# v6.net
KiCad netlist of a schematic drawn in EAGLE
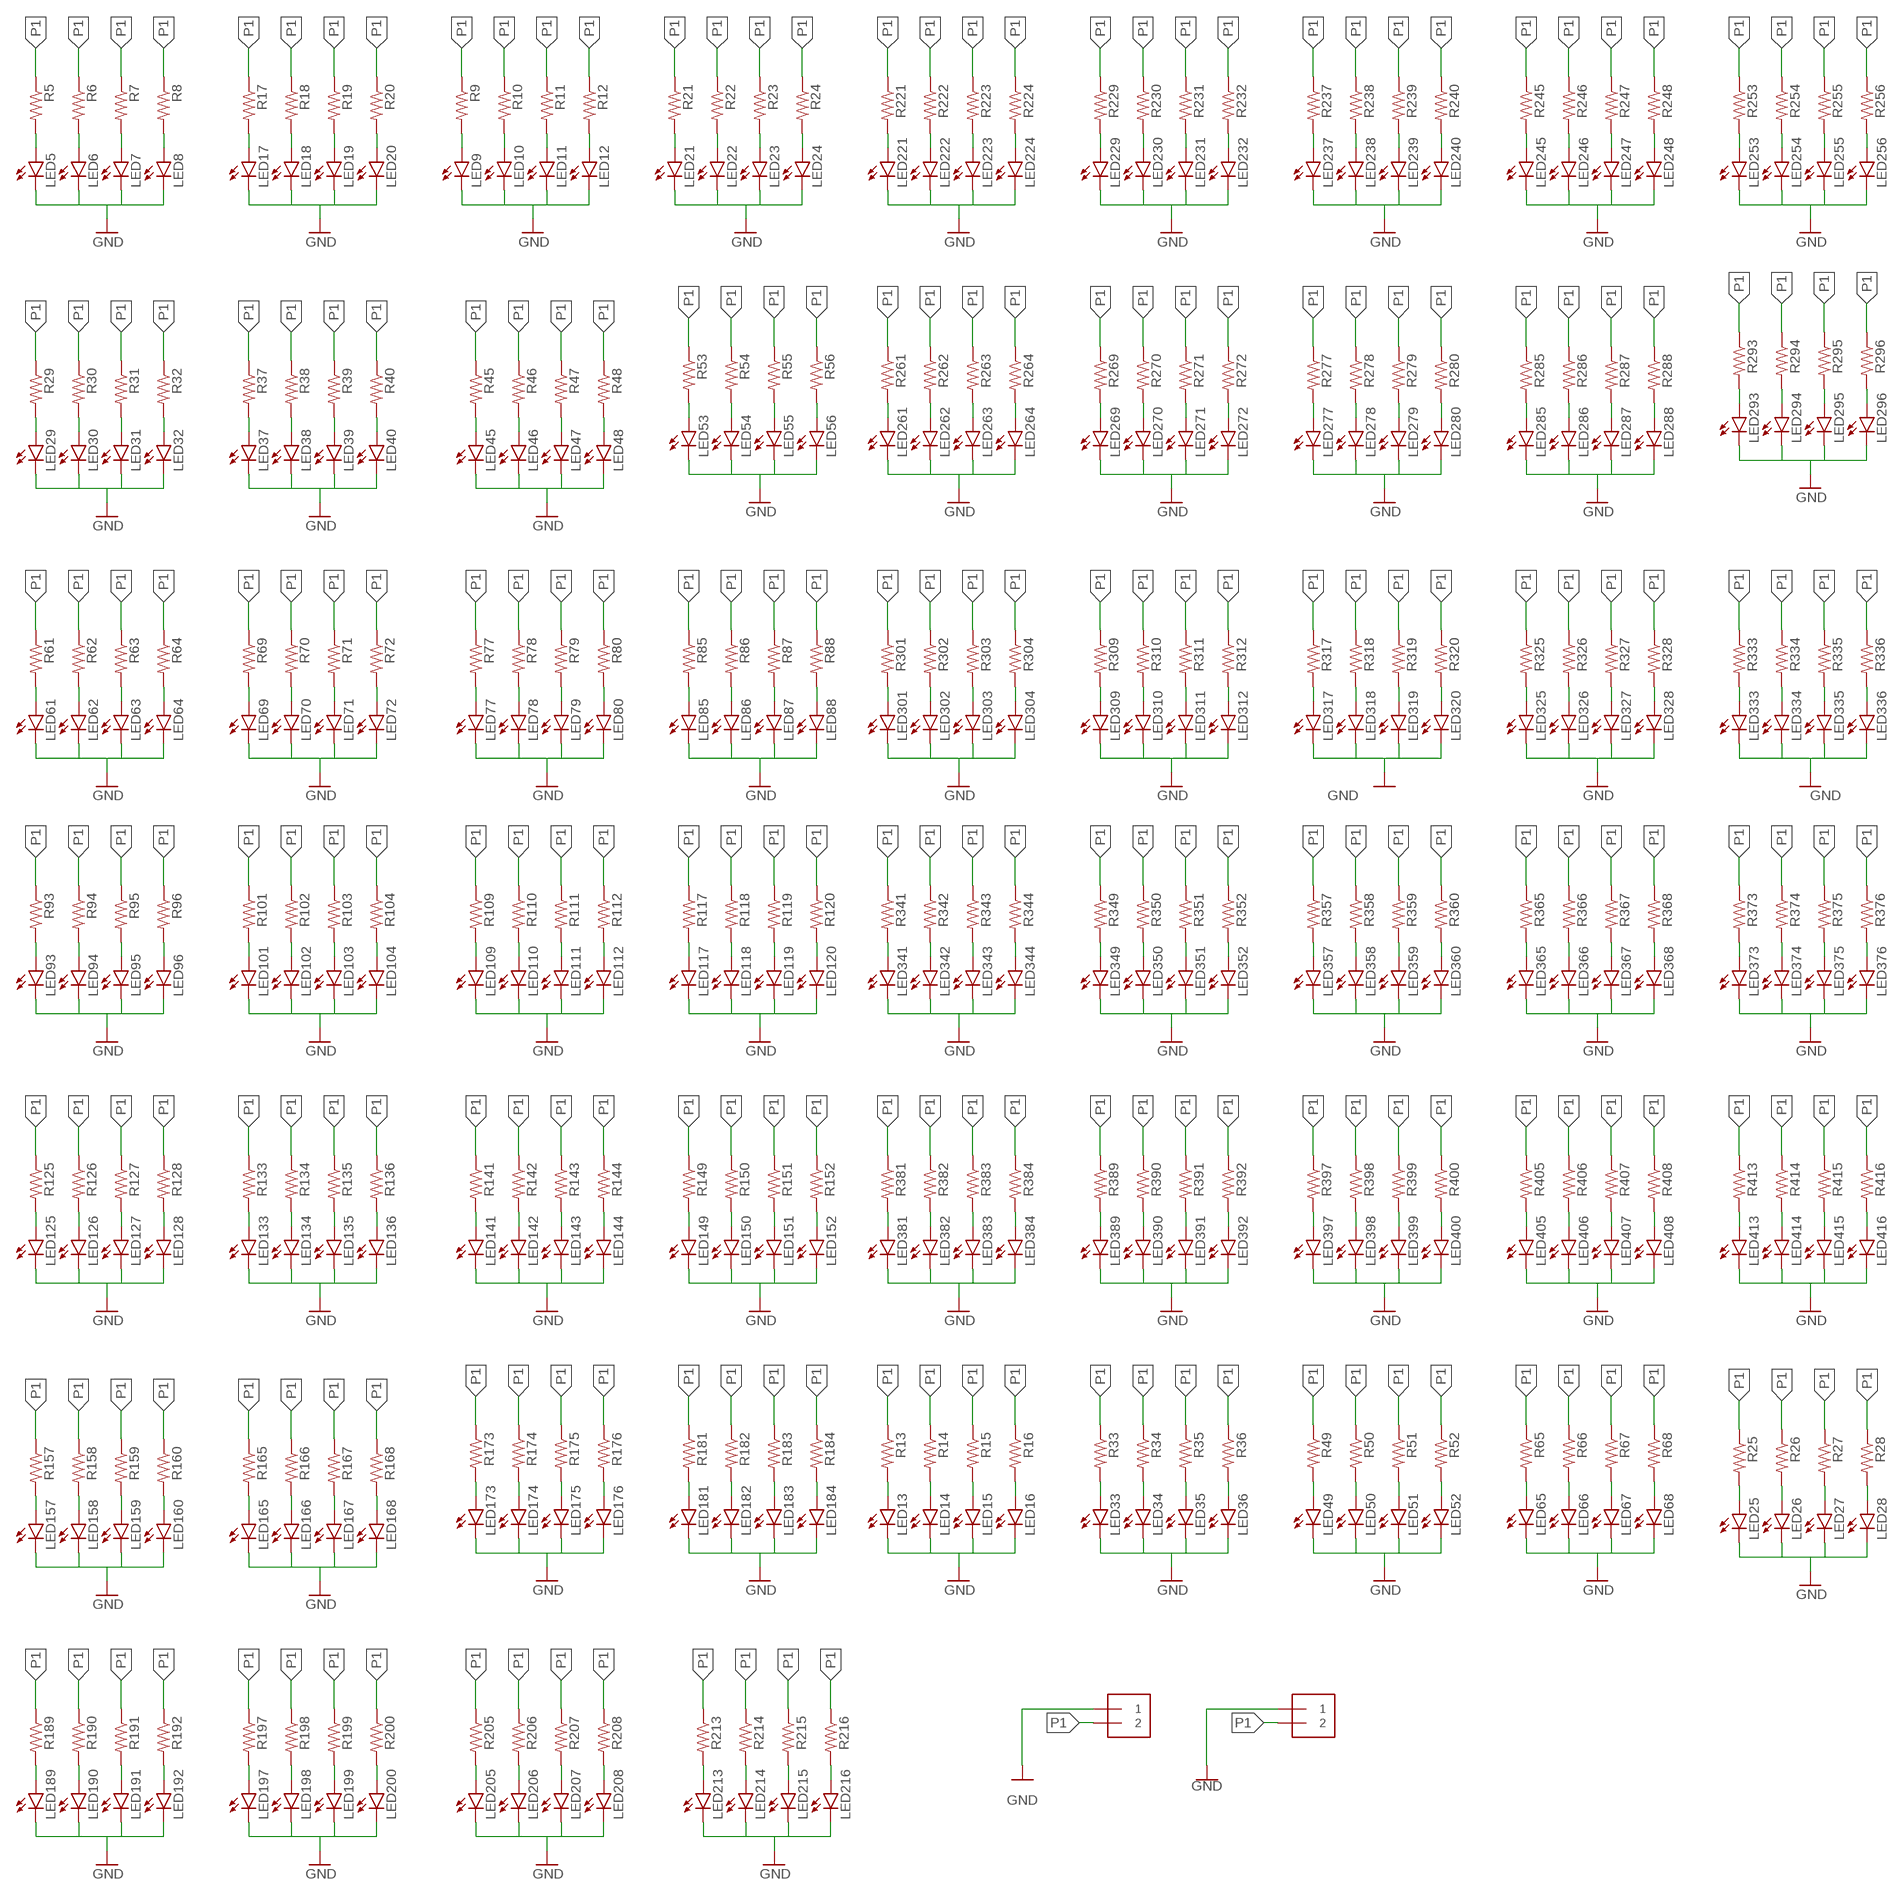
[diagram p0: schematic, sheet 1]

(export (version "E")
  (design (tool "Eeschema 10.0.6"))
  (components
    (comp (ref "LED5")
      (value "LEDCHIP-LED0603")
      (footprint "eagle-import:CHIP-LED0603")
      (libsource (lib "eagle-import") (part "LEDCHIP-LED0603"))
    )
    (comp (ref "LED6")
      (value "LEDCHIP-LED0603")
      (footprint "eagle-import:CHIP-LED0603")
      (libsource (lib "eagle-import") (part "LEDCHIP-LED0603"))
    )
    (comp (ref "LED7")
      (value "LEDCHIP-LED0603")
      (footprint "eagle-import:CHIP-LED0603")
      (libsource (lib "eagle-import") (part "LEDCHIP-LED0603"))
    )
    (comp (ref "LED8")
      (value "LEDCHIP-LED0603")
      (footprint "eagle-import:CHIP-LED0603")
      (libsource (lib "eagle-import") (part "LEDCHIP-LED0603"))
    )
    (comp (ref "LED9")
      (value "LEDCHIP-LED0603")
      (footprint "eagle-import:CHIP-LED0603")
      (libsource (lib "eagle-import") (part "LEDCHIP-LED0603"))
    )
    (comp (ref "LED10")
      (value "LEDCHIP-LED0603")
      (footprint "eagle-import:CHIP-LED0603")
      (libsource (lib "eagle-import") (part "LEDCHIP-LED0603"))
    )
    (comp (ref "LED11")
      (value "LEDCHIP-LED0603")
      (footprint "eagle-import:CHIP-LED0603")
      (libsource (lib "eagle-import") (part "LEDCHIP-LED0603"))
    )
    (comp (ref "LED12")
      (value "LEDCHIP-LED0603")
      (footprint "eagle-import:CHIP-LED0603")
      (libsource (lib "eagle-import") (part "LEDCHIP-LED0603"))
    )
    (comp (ref "LED13")
      (value "LEDCHIP-LED0603")
      (footprint "eagle-import:CHIP-LED0603")
      (libsource (lib "eagle-import") (part "LEDCHIP-LED0603"))
    )
    (comp (ref "LED14")
      (value "LEDCHIP-LED0603")
      (footprint "eagle-import:CHIP-LED0603")
      (libsource (lib "eagle-import") (part "LEDCHIP-LED0603"))
    )
    (comp (ref "LED15")
      (value "LEDCHIP-LED0603")
      (footprint "eagle-import:CHIP-LED0603")
      (libsource (lib "eagle-import") (part "LEDCHIP-LED0603"))
    )
    (comp (ref "LED16")
      (value "LEDCHIP-LED0603")
      (footprint "eagle-import:CHIP-LED0603")
      (libsource (lib "eagle-import") (part "LEDCHIP-LED0603"))
    )
    (comp (ref "LED17")
      (value "LEDCHIP-LED0603")
      (footprint "eagle-import:CHIP-LED0603")
      (libsource (lib "eagle-import") (part "LEDCHIP-LED0603"))
    )
    (comp (ref "LED18")
      (value "LEDCHIP-LED0603")
      (footprint "eagle-import:CHIP-LED0603")
      (libsource (lib "eagle-import") (part "LEDCHIP-LED0603"))
    )
    (comp (ref "LED19")
      (value "LEDCHIP-LED0603")
      (footprint "eagle-import:CHIP-LED0603")
      (libsource (lib "eagle-import") (part "LEDCHIP-LED0603"))
    )
    (comp (ref "LED20")
      (value "LEDCHIP-LED0603")
      (footprint "eagle-import:CHIP-LED0603")
      (libsource (lib "eagle-import") (part "LEDCHIP-LED0603"))
    )
    (comp (ref "LED21")
      (value "LEDCHIP-LED0603")
      (footprint "eagle-import:CHIP-LED0603")
      (libsource (lib "eagle-import") (part "LEDCHIP-LED0603"))
    )
    (comp (ref "LED22")
      (value "LEDCHIP-LED0603")
      (footprint "eagle-import:CHIP-LED0603")
      (libsource (lib "eagle-import") (part "LEDCHIP-LED0603"))
    )
    (comp (ref "LED23")
      (value "LEDCHIP-LED0603")
      (footprint "eagle-import:CHIP-LED0603")
      (libsource (lib "eagle-import") (part "LEDCHIP-LED0603"))
    )
    (comp (ref "LED24")
      (value "LEDCHIP-LED0603")
      (footprint "eagle-import:CHIP-LED0603")
      (libsource (lib "eagle-import") (part "LEDCHIP-LED0603"))
    )
    (comp (ref "LED25")
      (value "LEDCHIP-LED0603")
      (footprint "eagle-import:CHIP-LED0603")
      (libsource (lib "eagle-import") (part "LEDCHIP-LED0603"))
    )
    (comp (ref "LED26")
      (value "LEDCHIP-LED0603")
      (footprint "eagle-import:CHIP-LED0603")
      (libsource (lib "eagle-import") (part "LEDCHIP-LED0603"))
    )
    (comp (ref "LED27")
      (value "LEDCHIP-LED0603")
      (footprint "eagle-import:CHIP-LED0603")
      (libsource (lib "eagle-import") (part "LEDCHIP-LED0603"))
    )
    (comp (ref "LED28")
      (value "LEDCHIP-LED0603")
      (footprint "eagle-import:CHIP-LED0603")
      (libsource (lib "eagle-import") (part "LEDCHIP-LED0603"))
    )
    (comp (ref "LED29")
      (value "LEDCHIP-LED0603")
      (footprint "eagle-import:CHIP-LED0603")
      (libsource (lib "eagle-import") (part "LEDCHIP-LED0603"))
    )
    (comp (ref "LED30")
      (value "LEDCHIP-LED0603")
      (footprint "eagle-import:CHIP-LED0603")
      (libsource (lib "eagle-import") (part "LEDCHIP-LED0603"))
    )
    (comp (ref "LED31")
      (value "LEDCHIP-LED0603")
      (footprint "eagle-import:CHIP-LED0603")
      (libsource (lib "eagle-import") (part "LEDCHIP-LED0603"))
    )
    (comp (ref "LED32")
      (value "LEDCHIP-LED0603")
      (footprint "eagle-import:CHIP-LED0603")
      (libsource (lib "eagle-import") (part "LEDCHIP-LED0603"))
    )
    (comp (ref "LED33")
      (value "LEDCHIP-LED0603")
      (footprint "eagle-import:CHIP-LED0603")
      (libsource (lib "eagle-import") (part "LEDCHIP-LED0603"))
    )
    (comp (ref "LED34")
      (value "LEDCHIP-LED0603")
      (footprint "eagle-import:CHIP-LED0603")
      (libsource (lib "eagle-import") (part "LEDCHIP-LED0603"))
    )
    (comp (ref "LED35")
      (value "LEDCHIP-LED0603")
      (footprint "eagle-import:CHIP-LED0603")
      (libsource (lib "eagle-import") (part "LEDCHIP-LED0603"))
    )
    (comp (ref "LED36")
      (value "LEDCHIP-LED0603")
      (footprint "eagle-import:CHIP-LED0603")
      (libsource (lib "eagle-import") (part "LEDCHIP-LED0603"))
    )
    (comp (ref "LED37")
      (value "LEDCHIP-LED0603")
      (footprint "eagle-import:CHIP-LED0603")
      (libsource (lib "eagle-import") (part "LEDCHIP-LED0603"))
    )
    (comp (ref "LED38")
      (value "LEDCHIP-LED0603")
      (footprint "eagle-import:CHIP-LED0603")
      (libsource (lib "eagle-import") (part "LEDCHIP-LED0603"))
    )
    (comp (ref "LED39")
      (value "LEDCHIP-LED0603")
      (footprint "eagle-import:CHIP-LED0603")
      (libsource (lib "eagle-import") (part "LEDCHIP-LED0603"))
    )
    (comp (ref "LED40")
      (value "LEDCHIP-LED0603")
      (footprint "eagle-import:CHIP-LED0603")
      (libsource (lib "eagle-import") (part "LEDCHIP-LED0603"))
    )
    (comp (ref "LED45")
      (value "LEDCHIP-LED0603")
      (footprint "eagle-import:CHIP-LED0603")
      (libsource (lib "eagle-import") (part "LEDCHIP-LED0603"))
    )
    (comp (ref "LED46")
      (value "LEDCHIP-LED0603")
      (footprint "eagle-import:CHIP-LED0603")
      (libsource (lib "eagle-import") (part "LEDCHIP-LED0603"))
    )
    (comp (ref "LED47")
      (value "LEDCHIP-LED0603")
      (footprint "eagle-import:CHIP-LED0603")
      (libsource (lib "eagle-import") (part "LEDCHIP-LED0603"))
    )
    (comp (ref "LED48")
      (value "LEDCHIP-LED0603")
      (footprint "eagle-import:CHIP-LED0603")
      (libsource (lib "eagle-import") (part "LEDCHIP-LED0603"))
    )
    (comp (ref "LED49")
      (value "LEDCHIP-LED0603")
      (footprint "eagle-import:CHIP-LED0603")
      (libsource (lib "eagle-import") (part "LEDCHIP-LED0603"))
    )
    (comp (ref "LED50")
      (value "LEDCHIP-LED0603")
      (footprint "eagle-import:CHIP-LED0603")
      (libsource (lib "eagle-import") (part "LEDCHIP-LED0603"))
    )
    (comp (ref "LED51")
      (value "LEDCHIP-LED0603")
      (footprint "eagle-import:CHIP-LED0603")
      (libsource (lib "eagle-import") (part "LEDCHIP-LED0603"))
    )
    (comp (ref "LED52")
      (value "LEDCHIP-LED0603")
      (footprint "eagle-import:CHIP-LED0603")
      (libsource (lib "eagle-import") (part "LEDCHIP-LED0603"))
    )
    (comp (ref "LED53")
      (value "LEDCHIP-LED0603")
      (footprint "eagle-import:CHIP-LED0603")
      (libsource (lib "eagle-import") (part "LEDCHIP-LED0603"))
    )
    (comp (ref "LED54")
      (value "LEDCHIP-LED0603")
      (footprint "eagle-import:CHIP-LED0603")
      (libsource (lib "eagle-import") (part "LEDCHIP-LED0603"))
    )
    (comp (ref "LED55")
      (value "LEDCHIP-LED0603")
      (footprint "eagle-import:CHIP-LED0603")
      (libsource (lib "eagle-import") (part "LEDCHIP-LED0603"))
    )
    (comp (ref "LED56")
      (value "LEDCHIP-LED0603")
      (footprint "eagle-import:CHIP-LED0603")
      (libsource (lib "eagle-import") (part "LEDCHIP-LED0603"))
    )
    (comp (ref "LED61")
      (value "LEDCHIP-LED0603")
      (footprint "eagle-import:CHIP-LED0603")
      (libsource (lib "eagle-import") (part "LEDCHIP-LED0603"))
    )
    (comp (ref "LED62")
      (value "LEDCHIP-LED0603")
      (footprint "eagle-import:CHIP-LED0603")
      (libsource (lib "eagle-import") (part "LEDCHIP-LED0603"))
    )
    (comp (ref "LED63")
      (value "LEDCHIP-LED0603")
      (footprint "eagle-import:CHIP-LED0603")
      (libsource (lib "eagle-import") (part "LEDCHIP-LED0603"))
    )
    (comp (ref "LED64")
      (value "LEDCHIP-LED0603")
      (footprint "eagle-import:CHIP-LED0603")
      (libsource (lib "eagle-import") (part "LEDCHIP-LED0603"))
    )
    (comp (ref "LED65")
      (value "LEDCHIP-LED0603")
      (footprint "eagle-import:CHIP-LED0603")
      (libsource (lib "eagle-import") (part "LEDCHIP-LED0603"))
    )
    (comp (ref "LED66")
      (value "LEDCHIP-LED0603")
      (footprint "eagle-import:CHIP-LED0603")
      (libsource (lib "eagle-import") (part "LEDCHIP-LED0603"))
    )
    (comp (ref "LED67")
      (value "LEDCHIP-LED0603")
      (footprint "eagle-import:CHIP-LED0603")
      (libsource (lib "eagle-import") (part "LEDCHIP-LED0603"))
    )
    (comp (ref "LED68")
      (value "LEDCHIP-LED0603")
      (footprint "eagle-import:CHIP-LED0603")
      (libsource (lib "eagle-import") (part "LEDCHIP-LED0603"))
    )
    (comp (ref "LED69")
      (value "LEDCHIP-LED0603")
      (footprint "eagle-import:CHIP-LED0603")
      (libsource (lib "eagle-import") (part "LEDCHIP-LED0603"))
    )
    (comp (ref "LED70")
      (value "LEDCHIP-LED0603")
      (footprint "eagle-import:CHIP-LED0603")
      (libsource (lib "eagle-import") (part "LEDCHIP-LED0603"))
    )
    (comp (ref "LED71")
      (value "LEDCHIP-LED0603")
      (footprint "eagle-import:CHIP-LED0603")
      (libsource (lib "eagle-import") (part "LEDCHIP-LED0603"))
    )
    (comp (ref "LED72")
      (value "LEDCHIP-LED0603")
      (footprint "eagle-import:CHIP-LED0603")
      (libsource (lib "eagle-import") (part "LEDCHIP-LED0603"))
    )
    (comp (ref "LED77")
      (value "LEDCHIP-LED0603")
      (footprint "eagle-import:CHIP-LED0603")
      (libsource (lib "eagle-import") (part "LEDCHIP-LED0603"))
    )
    (comp (ref "LED78")
      (value "LEDCHIP-LED0603")
      (footprint "eagle-import:CHIP-LED0603")
      (libsource (lib "eagle-import") (part "LEDCHIP-LED0603"))
    )
    (comp (ref "LED79")
      (value "LEDCHIP-LED0603")
      (footprint "eagle-import:CHIP-LED0603")
      (libsource (lib "eagle-import") (part "LEDCHIP-LED0603"))
    )
    (comp (ref "LED80")
      (value "LEDCHIP-LED0603")
      (footprint "eagle-import:CHIP-LED0603")
      (libsource (lib "eagle-import") (part "LEDCHIP-LED0603"))
    )
    (comp (ref "LED85")
      (value "LEDCHIP-LED0603")
      (footprint "eagle-import:CHIP-LED0603")
      (libsource (lib "eagle-import") (part "LEDCHIP-LED0603"))
    )
    (comp (ref "LED86")
      (value "LEDCHIP-LED0603")
      (footprint "eagle-import:CHIP-LED0603")
      (libsource (lib "eagle-import") (part "LEDCHIP-LED0603"))
    )
    (comp (ref "LED87")
      (value "LEDCHIP-LED0603")
      (footprint "eagle-import:CHIP-LED0603")
      (libsource (lib "eagle-import") (part "LEDCHIP-LED0603"))
    )
    (comp (ref "LED88")
      (value "LEDCHIP-LED0603")
      (footprint "eagle-import:CHIP-LED0603")
      (libsource (lib "eagle-import") (part "LEDCHIP-LED0603"))
    )
    (comp (ref "LED93")
      (value "LEDCHIP-LED0603")
      (footprint "eagle-import:CHIP-LED0603")
      (libsource (lib "eagle-import") (part "LEDCHIP-LED0603"))
    )
    (comp (ref "LED94")
      (value "LEDCHIP-LED0603")
      (footprint "eagle-import:CHIP-LED0603")
      (libsource (lib "eagle-import") (part "LEDCHIP-LED0603"))
    )
    (comp (ref "LED95")
      (value "LEDCHIP-LED0603")
      (footprint "eagle-import:CHIP-LED0603")
      (libsource (lib "eagle-import") (part "LEDCHIP-LED0603"))
    )
    (comp (ref "LED96")
      (value "LEDCHIP-LED0603")
      (footprint "eagle-import:CHIP-LED0603")
      (libsource (lib "eagle-import") (part "LEDCHIP-LED0603"))
    )
    (comp (ref "LED101")
      (value "LEDCHIP-LED0603")
      (footprint "eagle-import:CHIP-LED0603")
      (libsource (lib "eagle-import") (part "LEDCHIP-LED0603"))
    )
    (comp (ref "LED102")
      (value "LEDCHIP-LED0603")
      (footprint "eagle-import:CHIP-LED0603")
      (libsource (lib "eagle-import") (part "LEDCHIP-LED0603"))
    )
    (comp (ref "LED103")
      (value "LEDCHIP-LED0603")
      (footprint "eagle-import:CHIP-LED0603")
      (libsource (lib "eagle-import") (part "LEDCHIP-LED0603"))
    )
    (comp (ref "LED104")
      (value "LEDCHIP-LED0603")
      (footprint "eagle-import:CHIP-LED0603")
      (libsource (lib "eagle-import") (part "LEDCHIP-LED0603"))
    )
    (comp (ref "LED109")
      (value "LEDCHIP-LED0603")
      (footprint "eagle-import:CHIP-LED0603")
      (libsource (lib "eagle-import") (part "LEDCHIP-LED0603"))
    )
    (comp (ref "LED110")
      (value "LEDCHIP-LED0603")
      (footprint "eagle-import:CHIP-LED0603")
      (libsource (lib "eagle-import") (part "LEDCHIP-LED0603"))
    )
    (comp (ref "LED111")
      (value "LEDCHIP-LED0603")
      (footprint "eagle-import:CHIP-LED0603")
      (libsource (lib "eagle-import") (part "LEDCHIP-LED0603"))
    )
    (comp (ref "LED112")
      (value "LEDCHIP-LED0603")
      (footprint "eagle-import:CHIP-LED0603")
      (libsource (lib "eagle-import") (part "LEDCHIP-LED0603"))
    )
    (comp (ref "LED117")
      (value "LEDCHIP-LED0603")
      (footprint "eagle-import:CHIP-LED0603")
      (libsource (lib "eagle-import") (part "LEDCHIP-LED0603"))
    )
    (comp (ref "LED118")
      (value "LEDCHIP-LED0603")
      (footprint "eagle-import:CHIP-LED0603")
      (libsource (lib "eagle-import") (part "LEDCHIP-LED0603"))
    )
    (comp (ref "LED119")
      (value "LEDCHIP-LED0603")
      (footprint "eagle-import:CHIP-LED0603")
      (libsource (lib "eagle-import") (part "LEDCHIP-LED0603"))
    )
    (comp (ref "LED120")
      (value "LEDCHIP-LED0603")
      (footprint "eagle-import:CHIP-LED0603")
      (libsource (lib "eagle-import") (part "LEDCHIP-LED0603"))
    )
    (comp (ref "LED125")
      (value "LEDCHIP-LED0603")
      (footprint "eagle-import:CHIP-LED0603")
      (libsource (lib "eagle-import") (part "LEDCHIP-LED0603"))
    )
    (comp (ref "LED126")
      (value "LEDCHIP-LED0603")
      (footprint "eagle-import:CHIP-LED0603")
      (libsource (lib "eagle-import") (part "LEDCHIP-LED0603"))
    )
    (comp (ref "LED127")
      (value "LEDCHIP-LED0603")
      (footprint "eagle-import:CHIP-LED0603")
      (libsource (lib "eagle-import") (part "LEDCHIP-LED0603"))
    )
    (comp (ref "LED128")
      (value "LEDCHIP-LED0603")
      (footprint "eagle-import:CHIP-LED0603")
      (libsource (lib "eagle-import") (part "LEDCHIP-LED0603"))
    )
    (comp (ref "LED133")
      (value "LEDCHIP-LED0603")
      (footprint "eagle-import:CHIP-LED0603")
      (libsource (lib "eagle-import") (part "LEDCHIP-LED0603"))
    )
    (comp (ref "LED134")
      (value "LEDCHIP-LED0603")
      (footprint "eagle-import:CHIP-LED0603")
      (libsource (lib "eagle-import") (part "LEDCHIP-LED0603"))
    )
    (comp (ref "LED135")
      (value "LEDCHIP-LED0603")
      (footprint "eagle-import:CHIP-LED0603")
      (libsource (lib "eagle-import") (part "LEDCHIP-LED0603"))
    )
    (comp (ref "LED136")
      (value "LEDCHIP-LED0603")
      (footprint "eagle-import:CHIP-LED0603")
      (libsource (lib "eagle-import") (part "LEDCHIP-LED0603"))
    )
    (comp (ref "LED141")
      (value "LEDCHIP-LED0603")
      (footprint "eagle-import:CHIP-LED0603")
      (libsource (lib "eagle-import") (part "LEDCHIP-LED0603"))
    )
    (comp (ref "LED142")
      (value "LEDCHIP-LED0603")
      (footprint "eagle-import:CHIP-LED0603")
      (libsource (lib "eagle-import") (part "LEDCHIP-LED0603"))
    )
    (comp (ref "LED143")
      (value "LEDCHIP-LED0603")
      (footprint "eagle-import:CHIP-LED0603")
      (libsource (lib "eagle-import") (part "LEDCHIP-LED0603"))
    )
    (comp (ref "LED144")
      (value "LEDCHIP-LED0603")
      (footprint "eagle-import:CHIP-LED0603")
      (libsource (lib "eagle-import") (part "LEDCHIP-LED0603"))
    )
    (comp (ref "LED149")
      (value "LEDCHIP-LED0603")
      (footprint "eagle-import:CHIP-LED0603")
      (libsource (lib "eagle-import") (part "LEDCHIP-LED0603"))
    )
    (comp (ref "LED150")
      (value "LEDCHIP-LED0603")
      (footprint "eagle-import:CHIP-LED0603")
      (libsource (lib "eagle-import") (part "LEDCHIP-LED0603"))
    )
    (comp (ref "LED151")
      (value "LEDCHIP-LED0603")
      (footprint "eagle-import:CHIP-LED0603")
      (libsource (lib "eagle-import") (part "LEDCHIP-LED0603"))
    )
    (comp (ref "LED152")
      (value "LEDCHIP-LED0603")
      (footprint "eagle-import:CHIP-LED0603")
      (libsource (lib "eagle-import") (part "LEDCHIP-LED0603"))
    )
    (comp (ref "LED157")
      (value "LEDCHIP-LED0603")
      (footprint "eagle-import:CHIP-LED0603")
      (libsource (lib "eagle-import") (part "LEDCHIP-LED0603"))
    )
    (comp (ref "LED158")
      (value "LEDCHIP-LED0603")
      (footprint "eagle-import:CHIP-LED0603")
      (libsource (lib "eagle-import") (part "LEDCHIP-LED0603"))
    )
    (comp (ref "LED159")
      (value "LEDCHIP-LED0603")
      (footprint "eagle-import:CHIP-LED0603")
      (libsource (lib "eagle-import") (part "LEDCHIP-LED0603"))
    )
    (comp (ref "LED160")
      (value "LEDCHIP-LED0603")
      (footprint "eagle-import:CHIP-LED0603")
      (libsource (lib "eagle-import") (part "LEDCHIP-LED0603"))
    )
    (comp (ref "LED165")
      (value "LEDCHIP-LED0603")
      (footprint "eagle-import:CHIP-LED0603")
      (libsource (lib "eagle-import") (part "LEDCHIP-LED0603"))
    )
    (comp (ref "LED166")
      (value "LEDCHIP-LED0603")
      (footprint "eagle-import:CHIP-LED0603")
      (libsource (lib "eagle-import") (part "LEDCHIP-LED0603"))
    )
    (comp (ref "LED167")
      (value "LEDCHIP-LED0603")
      (footprint "eagle-import:CHIP-LED0603")
      (libsource (lib "eagle-import") (part "LEDCHIP-LED0603"))
    )
    (comp (ref "LED168")
      (value "LEDCHIP-LED0603")
      (footprint "eagle-import:CHIP-LED0603")
      (libsource (lib "eagle-import") (part "LEDCHIP-LED0603"))
    )
    (comp (ref "LED173")
      (value "LEDCHIP-LED0603")
      (footprint "eagle-import:CHIP-LED0603")
      (libsource (lib "eagle-import") (part "LEDCHIP-LED0603"))
    )
    (comp (ref "LED174")
      (value "LEDCHIP-LED0603")
      (footprint "eagle-import:CHIP-LED0603")
      (libsource (lib "eagle-import") (part "LEDCHIP-LED0603"))
    )
    (comp (ref "LED175")
      (value "LEDCHIP-LED0603")
      (footprint "eagle-import:CHIP-LED0603")
      (libsource (lib "eagle-import") (part "LEDCHIP-LED0603"))
    )
    (comp (ref "LED176")
      (value "LEDCHIP-LED0603")
      (footprint "eagle-import:CHIP-LED0603")
      (libsource (lib "eagle-import") (part "LEDCHIP-LED0603"))
    )
    (comp (ref "LED181")
      (value "LEDCHIP-LED0603")
      (footprint "eagle-import:CHIP-LED0603")
      (libsource (lib "eagle-import") (part "LEDCHIP-LED0603"))
    )
    (comp (ref "LED182")
      (value "LEDCHIP-LED0603")
      (footprint "eagle-import:CHIP-LED0603")
      (libsource (lib "eagle-import") (part "LEDCHIP-LED0603"))
    )
    (comp (ref "LED183")
      (value "LEDCHIP-LED0603")
      (footprint "eagle-import:CHIP-LED0603")
      (libsource (lib "eagle-import") (part "LEDCHIP-LED0603"))
    )
    (comp (ref "LED184")
      (value "LEDCHIP-LED0603")
      (footprint "eagle-import:CHIP-LED0603")
      (libsource (lib "eagle-import") (part "LEDCHIP-LED0603"))
    )
    (comp (ref "LED189")
      (value "LEDCHIP-LED0603")
      (footprint "eagle-import:CHIP-LED0603")
      (libsource (lib "eagle-import") (part "LEDCHIP-LED0603"))
    )
    (comp (ref "LED190")
      (value "LEDCHIP-LED0603")
      (footprint "eagle-import:CHIP-LED0603")
      (libsource (lib "eagle-import") (part "LEDCHIP-LED0603"))
    )
    (comp (ref "LED191")
      (value "LEDCHIP-LED0603")
      (footprint "eagle-import:CHIP-LED0603")
      (libsource (lib "eagle-import") (part "LEDCHIP-LED0603"))
    )
    (comp (ref "LED192")
      (value "LEDCHIP-LED0603")
      (footprint "eagle-import:CHIP-LED0603")
      (libsource (lib "eagle-import") (part "LEDCHIP-LED0603"))
    )
    (comp (ref "LED197")
      (value "LEDCHIP-LED0603")
      (footprint "eagle-import:CHIP-LED0603")
      (libsource (lib "eagle-import") (part "LEDCHIP-LED0603"))
    )
    (comp (ref "LED198")
      (value "LEDCHIP-LED0603")
      (footprint "eagle-import:CHIP-LED0603")
      (libsource (lib "eagle-import") (part "LEDCHIP-LED0603"))
    )
    (comp (ref "LED199")
      (value "LEDCHIP-LED0603")
      (footprint "eagle-import:CHIP-LED0603")
      (libsource (lib "eagle-import") (part "LEDCHIP-LED0603"))
    )
    (comp (ref "LED200")
      (value "LEDCHIP-LED0603")
      (footprint "eagle-import:CHIP-LED0603")
      (libsource (lib "eagle-import") (part "LEDCHIP-LED0603"))
    )
    (comp (ref "LED205")
      (value "LEDCHIP-LED0603")
      (footprint "eagle-import:CHIP-LED0603")
      (libsource (lib "eagle-import") (part "LEDCHIP-LED0603"))
    )
    (comp (ref "LED206")
      (value "LEDCHIP-LED0603")
      (footprint "eagle-import:CHIP-LED0603")
      (libsource (lib "eagle-import") (part "LEDCHIP-LED0603"))
    )
    (comp (ref "LED207")
      (value "LEDCHIP-LED0603")
      (footprint "eagle-import:CHIP-LED0603")
      (libsource (lib "eagle-import") (part "LEDCHIP-LED0603"))
    )
    (comp (ref "LED208")
      (value "LEDCHIP-LED0603")
      (footprint "eagle-import:CHIP-LED0603")
      (libsource (lib "eagle-import") (part "LEDCHIP-LED0603"))
    )
    (comp (ref "LED213")
      (value "LEDCHIP-LED0603")
      (footprint "eagle-import:CHIP-LED0603")
      (libsource (lib "eagle-import") (part "LEDCHIP-LED0603"))
    )
    (comp (ref "LED214")
      (value "LEDCHIP-LED0603")
      (footprint "eagle-import:CHIP-LED0603")
      (libsource (lib "eagle-import") (part "LEDCHIP-LED0603"))
    )
    (comp (ref "LED215")
      (value "LEDCHIP-LED0603")
      (footprint "eagle-import:CHIP-LED0603")
      (libsource (lib "eagle-import") (part "LEDCHIP-LED0603"))
    )
    (comp (ref "LED216")
      (value "LEDCHIP-LED0603")
      (footprint "eagle-import:CHIP-LED0603")
      (libsource (lib "eagle-import") (part "LEDCHIP-LED0603"))
    )
    (comp (ref "LED221")
      (value "LEDCHIP-LED0603")
      (footprint "eagle-import:CHIP-LED0603")
      (libsource (lib "eagle-import") (part "LEDCHIP-LED0603"))
    )
    (comp (ref "LED222")
      (value "LEDCHIP-LED0603")
      (footprint "eagle-import:CHIP-LED0603")
      (libsource (lib "eagle-import") (part "LEDCHIP-LED0603"))
    )
    (comp (ref "LED223")
      (value "LEDCHIP-LED0603")
      (footprint "eagle-import:CHIP-LED0603")
      (libsource (lib "eagle-import") (part "LEDCHIP-LED0603"))
    )
    (comp (ref "LED224")
      (value "LEDCHIP-LED0603")
      (footprint "eagle-import:CHIP-LED0603")
      (libsource (lib "eagle-import") (part "LEDCHIP-LED0603"))
    )
    (comp (ref "LED229")
      (value "LEDCHIP-LED0603")
      (footprint "eagle-import:CHIP-LED0603")
      (libsource (lib "eagle-import") (part "LEDCHIP-LED0603"))
    )
    (comp (ref "LED230")
      (value "LEDCHIP-LED0603")
      (footprint "eagle-import:CHIP-LED0603")
      (libsource (lib "eagle-import") (part "LEDCHIP-LED0603"))
    )
    (comp (ref "LED231")
      (value "LEDCHIP-LED0603")
      (footprint "eagle-import:CHIP-LED0603")
      (libsource (lib "eagle-import") (part "LEDCHIP-LED0603"))
    )
    (comp (ref "LED232")
      (value "LEDCHIP-LED0603")
      (footprint "eagle-import:CHIP-LED0603")
      (libsource (lib "eagle-import") (part "LEDCHIP-LED0603"))
    )
    (comp (ref "LED237")
      (value "LEDCHIP-LED0603")
      (footprint "eagle-import:CHIP-LED0603")
      (libsource (lib "eagle-import") (part "LEDCHIP-LED0603"))
    )
    (comp (ref "LED238")
      (value "LEDCHIP-LED0603")
      (footprint "eagle-import:CHIP-LED0603")
      (libsource (lib "eagle-import") (part "LEDCHIP-LED0603"))
    )
    (comp (ref "LED239")
      (value "LEDCHIP-LED0603")
      (footprint "eagle-import:CHIP-LED0603")
      (libsource (lib "eagle-import") (part "LEDCHIP-LED0603"))
    )
    (comp (ref "LED240")
      (value "LEDCHIP-LED0603")
      (footprint "eagle-import:CHIP-LED0603")
      (libsource (lib "eagle-import") (part "LEDCHIP-LED0603"))
    )
    (comp (ref "LED245")
      (value "LEDCHIP-LED0603")
      (footprint "eagle-import:CHIP-LED0603")
      (libsource (lib "eagle-import") (part "LEDCHIP-LED0603"))
    )
    (comp (ref "LED246")
      (value "LEDCHIP-LED0603")
      (footprint "eagle-import:CHIP-LED0603")
      (libsource (lib "eagle-import") (part "LEDCHIP-LED0603"))
    )
    (comp (ref "LED247")
      (value "LEDCHIP-LED0603")
      (footprint "eagle-import:CHIP-LED0603")
      (libsource (lib "eagle-import") (part "LEDCHIP-LED0603"))
    )
    (comp (ref "LED248")
      (value "LEDCHIP-LED0603")
      (footprint "eagle-import:CHIP-LED0603")
      (libsource (lib "eagle-import") (part "LEDCHIP-LED0603"))
    )
    (comp (ref "LED253")
      (value "LEDCHIP-LED0603")
      (footprint "eagle-import:CHIP-LED0603")
      (libsource (lib "eagle-import") (part "LEDCHIP-LED0603"))
    )
    (comp (ref "LED254")
      (value "LEDCHIP-LED0603")
      (footprint "eagle-import:CHIP-LED0603")
      (libsource (lib "eagle-import") (part "LEDCHIP-LED0603"))
    )
    (comp (ref "LED255")
      (value "LEDCHIP-LED0603")
      (footprint "eagle-import:CHIP-LED0603")
      (libsource (lib "eagle-import") (part "LEDCHIP-LED0603"))
    )
    (comp (ref "LED256")
      (value "LEDCHIP-LED0603")
      (footprint "eagle-import:CHIP-LED0603")
      (libsource (lib "eagle-import") (part "LEDCHIP-LED0603"))
    )
    (comp (ref "LED261")
      (value "LEDCHIP-LED0603")
      (footprint "eagle-import:CHIP-LED0603")
      (libsource (lib "eagle-import") (part "LEDCHIP-LED0603"))
    )
    (comp (ref "LED262")
      (value "LEDCHIP-LED0603")
      (footprint "eagle-import:CHIP-LED0603")
      (libsource (lib "eagle-import") (part "LEDCHIP-LED0603"))
    )
    (comp (ref "LED263")
      (value "LEDCHIP-LED0603")
      (footprint "eagle-import:CHIP-LED0603")
      (libsource (lib "eagle-import") (part "LEDCHIP-LED0603"))
    )
    (comp (ref "LED264")
      (value "LEDCHIP-LED0603")
      (footprint "eagle-import:CHIP-LED0603")
      (libsource (lib "eagle-import") (part "LEDCHIP-LED0603"))
    )
    (comp (ref "LED269")
      (value "LEDCHIP-LED0603")
      (footprint "eagle-import:CHIP-LED0603")
      (libsource (lib "eagle-import") (part "LEDCHIP-LED0603"))
    )
    (comp (ref "LED270")
      (value "LEDCHIP-LED0603")
      (footprint "eagle-import:CHIP-LED0603")
      (libsource (lib "eagle-import") (part "LEDCHIP-LED0603"))
    )
    (comp (ref "LED271")
      (value "LEDCHIP-LED0603")
      (footprint "eagle-import:CHIP-LED0603")
      (libsource (lib "eagle-import") (part "LEDCHIP-LED0603"))
    )
    (comp (ref "LED272")
      (value "LEDCHIP-LED0603")
      (footprint "eagle-import:CHIP-LED0603")
      (libsource (lib "eagle-import") (part "LEDCHIP-LED0603"))
    )
    (comp (ref "LED277")
      (value "LEDCHIP-LED0603")
      (footprint "eagle-import:CHIP-LED0603")
      (libsource (lib "eagle-import") (part "LEDCHIP-LED0603"))
    )
    (comp (ref "LED278")
      (value "LEDCHIP-LED0603")
      (footprint "eagle-import:CHIP-LED0603")
      (libsource (lib "eagle-import") (part "LEDCHIP-LED0603"))
    )
    (comp (ref "LED279")
      (value "LEDCHIP-LED0603")
      (footprint "eagle-import:CHIP-LED0603")
      (libsource (lib "eagle-import") (part "LEDCHIP-LED0603"))
    )
    (comp (ref "LED280")
      (value "LEDCHIP-LED0603")
      (footprint "eagle-import:CHIP-LED0603")
      (libsource (lib "eagle-import") (part "LEDCHIP-LED0603"))
    )
    (comp (ref "LED285")
      (value "LEDCHIP-LED0603")
      (footprint "eagle-import:CHIP-LED0603")
      (libsource (lib "eagle-import") (part "LEDCHIP-LED0603"))
    )
    (comp (ref "LED286")
      (value "LEDCHIP-LED0603")
      (footprint "eagle-import:CHIP-LED0603")
      (libsource (lib "eagle-import") (part "LEDCHIP-LED0603"))
    )
    (comp (ref "LED287")
      (value "LEDCHIP-LED0603")
      (footprint "eagle-import:CHIP-LED0603")
      (libsource (lib "eagle-import") (part "LEDCHIP-LED0603"))
    )
    (comp (ref "LED288")
      (value "LEDCHIP-LED0603")
      (footprint "eagle-import:CHIP-LED0603")
      (libsource (lib "eagle-import") (part "LEDCHIP-LED0603"))
    )
    (comp (ref "LED293")
      (value "LEDCHIP-LED0603")
      (footprint "eagle-import:CHIP-LED0603")
      (libsource (lib "eagle-import") (part "LEDCHIP-LED0603"))
    )
    (comp (ref "LED294")
      (value "LEDCHIP-LED0603")
      (footprint "eagle-import:CHIP-LED0603")
      (libsource (lib "eagle-import") (part "LEDCHIP-LED0603"))
    )
    (comp (ref "LED295")
      (value "LEDCHIP-LED0603")
      (footprint "eagle-import:CHIP-LED0603")
      (libsource (lib "eagle-import") (part "LEDCHIP-LED0603"))
    )
    (comp (ref "LED296")
      (value "LEDCHIP-LED0603")
      (footprint "eagle-import:CHIP-LED0603")
      (libsource (lib "eagle-import") (part "LEDCHIP-LED0603"))
    )
    (comp (ref "LED301")
      (value "LEDCHIP-LED0603")
      (footprint "eagle-import:CHIP-LED0603")
      (libsource (lib "eagle-import") (part "LEDCHIP-LED0603"))
    )
    (comp (ref "LED302")
      (value "LEDCHIP-LED0603")
      (footprint "eagle-import:CHIP-LED0603")
      (libsource (lib "eagle-import") (part "LEDCHIP-LED0603"))
    )
    (comp (ref "LED303")
      (value "LEDCHIP-LED0603")
      (footprint "eagle-import:CHIP-LED0603")
      (libsource (lib "eagle-import") (part "LEDCHIP-LED0603"))
    )
    (comp (ref "LED304")
      (value "LEDCHIP-LED0603")
      (footprint "eagle-import:CHIP-LED0603")
      (libsource (lib "eagle-import") (part "LEDCHIP-LED0603"))
    )
    (comp (ref "LED309")
      (value "LEDCHIP-LED0603")
      (footprint "eagle-import:CHIP-LED0603")
      (libsource (lib "eagle-import") (part "LEDCHIP-LED0603"))
    )
    (comp (ref "LED310")
      (value "LEDCHIP-LED0603")
      (footprint "eagle-import:CHIP-LED0603")
      (libsource (lib "eagle-import") (part "LEDCHIP-LED0603"))
    )
    (comp (ref "LED311")
      (value "LEDCHIP-LED0603")
      (footprint "eagle-import:CHIP-LED0603")
      (libsource (lib "eagle-import") (part "LEDCHIP-LED0603"))
    )
    (comp (ref "LED312")
      (value "LEDCHIP-LED0603")
      (footprint "eagle-import:CHIP-LED0603")
      (libsource (lib "eagle-import") (part "LEDCHIP-LED0603"))
    )
    (comp (ref "LED317")
      (value "LEDCHIP-LED0603")
      (footprint "eagle-import:CHIP-LED0603")
      (libsource (lib "eagle-import") (part "LEDCHIP-LED0603"))
    )
    (comp (ref "LED318")
      (value "LEDCHIP-LED0603")
      (footprint "eagle-import:CHIP-LED0603")
      (libsource (lib "eagle-import") (part "LEDCHIP-LED0603"))
    )
    (comp (ref "LED319")
      (value "LEDCHIP-LED0603")
      (footprint "eagle-import:CHIP-LED0603")
      (libsource (lib "eagle-import") (part "LEDCHIP-LED0603"))
    )
    (comp (ref "LED320")
      (value "LEDCHIP-LED0603")
      (footprint "eagle-import:CHIP-LED0603")
      (libsource (lib "eagle-import") (part "LEDCHIP-LED0603"))
    )
    (comp (ref "LED325")
      (value "LEDCHIP-LED0603")
      (footprint "eagle-import:CHIP-LED0603")
      (libsource (lib "eagle-import") (part "LEDCHIP-LED0603"))
    )
    (comp (ref "LED326")
      (value "LEDCHIP-LED0603")
      (footprint "eagle-import:CHIP-LED0603")
      (libsource (lib "eagle-import") (part "LEDCHIP-LED0603"))
    )
    (comp (ref "LED327")
      (value "LEDCHIP-LED0603")
      (footprint "eagle-import:CHIP-LED0603")
      (libsource (lib "eagle-import") (part "LEDCHIP-LED0603"))
    )
    (comp (ref "LED328")
      (value "LEDCHIP-LED0603")
      (footprint "eagle-import:CHIP-LED0603")
      (libsource (lib "eagle-import") (part "LEDCHIP-LED0603"))
    )
    (comp (ref "LED333")
      (value "LEDCHIP-LED0603")
      (footprint "eagle-import:CHIP-LED0603")
      (libsource (lib "eagle-import") (part "LEDCHIP-LED0603"))
    )
    (comp (ref "LED334")
      (value "LEDCHIP-LED0603")
      (footprint "eagle-import:CHIP-LED0603")
      (libsource (lib "eagle-import") (part "LEDCHIP-LED0603"))
    )
    (comp (ref "LED335")
      (value "LEDCHIP-LED0603")
      (footprint "eagle-import:CHIP-LED0603")
      (libsource (lib "eagle-import") (part "LEDCHIP-LED0603"))
    )
    (comp (ref "LED336")
      (value "LEDCHIP-LED0603")
      (footprint "eagle-import:CHIP-LED0603")
      (libsource (lib "eagle-import") (part "LEDCHIP-LED0603"))
    )
    (comp (ref "LED341")
      (value "LEDCHIP-LED0603")
      (footprint "eagle-import:CHIP-LED0603")
      (libsource (lib "eagle-import") (part "LEDCHIP-LED0603"))
    )
    (comp (ref "LED342")
      (value "LEDCHIP-LED0603")
      (footprint "eagle-import:CHIP-LED0603")
      (libsource (lib "eagle-import") (part "LEDCHIP-LED0603"))
    )
    (comp (ref "LED343")
      (value "LEDCHIP-LED0603")
      (footprint "eagle-import:CHIP-LED0603")
      (libsource (lib "eagle-import") (part "LEDCHIP-LED0603"))
    )
    (comp (ref "LED344")
      (value "LEDCHIP-LED0603")
      (footprint "eagle-import:CHIP-LED0603")
      (libsource (lib "eagle-import") (part "LEDCHIP-LED0603"))
    )
    (comp (ref "LED349")
      (value "LEDCHIP-LED0603")
      (footprint "eagle-import:CHIP-LED0603")
      (libsource (lib "eagle-import") (part "LEDCHIP-LED0603"))
    )
    (comp (ref "LED350")
      (value "LEDCHIP-LED0603")
      (footprint "eagle-import:CHIP-LED0603")
      (libsource (lib "eagle-import") (part "LEDCHIP-LED0603"))
    )
    (comp (ref "LED351")
      (value "LEDCHIP-LED0603")
      (footprint "eagle-import:CHIP-LED0603")
      (libsource (lib "eagle-import") (part "LEDCHIP-LED0603"))
    )
    (comp (ref "LED352")
      (value "LEDCHIP-LED0603")
      (footprint "eagle-import:CHIP-LED0603")
      (libsource (lib "eagle-import") (part "LEDCHIP-LED0603"))
    )
    (comp (ref "LED357")
      (value "LEDCHIP-LED0603")
      (footprint "eagle-import:CHIP-LED0603")
      (libsource (lib "eagle-import") (part "LEDCHIP-LED0603"))
    )
    (comp (ref "LED358")
      (value "LEDCHIP-LED0603")
      (footprint "eagle-import:CHIP-LED0603")
      (libsource (lib "eagle-import") (part "LEDCHIP-LED0603"))
    )
    (comp (ref "LED359")
      (value "LEDCHIP-LED0603")
      (footprint "eagle-import:CHIP-LED0603")
      (libsource (lib "eagle-import") (part "LEDCHIP-LED0603"))
    )
    (comp (ref "LED360")
      (value "LEDCHIP-LED0603")
      (footprint "eagle-import:CHIP-LED0603")
      (libsource (lib "eagle-import") (part "LEDCHIP-LED0603"))
    )
    (comp (ref "LED365")
      (value "LEDCHIP-LED0603")
      (footprint "eagle-import:CHIP-LED0603")
      (libsource (lib "eagle-import") (part "LEDCHIP-LED0603"))
    )
    (comp (ref "LED366")
      (value "LEDCHIP-LED0603")
      (footprint "eagle-import:CHIP-LED0603")
      (libsource (lib "eagle-import") (part "LEDCHIP-LED0603"))
    )
    (comp (ref "LED367")
      (value "LEDCHIP-LED0603")
      (footprint "eagle-import:CHIP-LED0603")
      (libsource (lib "eagle-import") (part "LEDCHIP-LED0603"))
    )
    (comp (ref "LED368")
      (value "LEDCHIP-LED0603")
      (footprint "eagle-import:CHIP-LED0603")
      (libsource (lib "eagle-import") (part "LEDCHIP-LED0603"))
    )
    (comp (ref "LED373")
      (value "LEDCHIP-LED0603")
      (footprint "eagle-import:CHIP-LED0603")
      (libsource (lib "eagle-import") (part "LEDCHIP-LED0603"))
    )
    (comp (ref "LED374")
      (value "LEDCHIP-LED0603")
      (footprint "eagle-import:CHIP-LED0603")
      (libsource (lib "eagle-import") (part "LEDCHIP-LED0603"))
    )
    (comp (ref "LED375")
      (value "LEDCHIP-LED0603")
      (footprint "eagle-import:CHIP-LED0603")
      (libsource (lib "eagle-import") (part "LEDCHIP-LED0603"))
    )
    (comp (ref "LED376")
      (value "LEDCHIP-LED0603")
      (footprint "eagle-import:CHIP-LED0603")
      (libsource (lib "eagle-import") (part "LEDCHIP-LED0603"))
    )
    (comp (ref "LED381")
      (value "LEDCHIP-LED0603")
      (footprint "eagle-import:CHIP-LED0603")
      (libsource (lib "eagle-import") (part "LEDCHIP-LED0603"))
    )
    (comp (ref "LED382")
      (value "LEDCHIP-LED0603")
      (footprint "eagle-import:CHIP-LED0603")
      (libsource (lib "eagle-import") (part "LEDCHIP-LED0603"))
    )
    (comp (ref "LED383")
      (value "LEDCHIP-LED0603")
      (footprint "eagle-import:CHIP-LED0603")
      (libsource (lib "eagle-import") (part "LEDCHIP-LED0603"))
    )
    (comp (ref "LED384")
      (value "LEDCHIP-LED0603")
      (footprint "eagle-import:CHIP-LED0603")
      (libsource (lib "eagle-import") (part "LEDCHIP-LED0603"))
    )
    (comp (ref "LED389")
      (value "LEDCHIP-LED0603")
      (footprint "eagle-import:CHIP-LED0603")
      (libsource (lib "eagle-import") (part "LEDCHIP-LED0603"))
    )
    (comp (ref "LED390")
      (value "LEDCHIP-LED0603")
      (footprint "eagle-import:CHIP-LED0603")
      (libsource (lib "eagle-import") (part "LEDCHIP-LED0603"))
    )
    (comp (ref "LED391")
      (value "LEDCHIP-LED0603")
      (footprint "eagle-import:CHIP-LED0603")
      (libsource (lib "eagle-import") (part "LEDCHIP-LED0603"))
    )
    (comp (ref "LED392")
      (value "LEDCHIP-LED0603")
      (footprint "eagle-import:CHIP-LED0603")
      (libsource (lib "eagle-import") (part "LEDCHIP-LED0603"))
    )
    (comp (ref "LED397")
      (value "LEDCHIP-LED0603")
      (footprint "eagle-import:CHIP-LED0603")
      (libsource (lib "eagle-import") (part "LEDCHIP-LED0603"))
    )
    (comp (ref "LED398")
      (value "LEDCHIP-LED0603")
      (footprint "eagle-import:CHIP-LED0603")
      (libsource (lib "eagle-import") (part "LEDCHIP-LED0603"))
    )
    (comp (ref "LED399")
      (value "LEDCHIP-LED0603")
      (footprint "eagle-import:CHIP-LED0603")
      (libsource (lib "eagle-import") (part "LEDCHIP-LED0603"))
    )
    (comp (ref "LED400")
      (value "LEDCHIP-LED0603")
      (footprint "eagle-import:CHIP-LED0603")
      (libsource (lib "eagle-import") (part "LEDCHIP-LED0603"))
    )
    (comp (ref "LED405")
      (value "LEDCHIP-LED0603")
      (footprint "eagle-import:CHIP-LED0603")
      (libsource (lib "eagle-import") (part "LEDCHIP-LED0603"))
    )
    (comp (ref "LED406")
      (value "LEDCHIP-LED0603")
      (footprint "eagle-import:CHIP-LED0603")
      (libsource (lib "eagle-import") (part "LEDCHIP-LED0603"))
    )
    (comp (ref "LED407")
      (value "LEDCHIP-LED0603")
      (footprint "eagle-import:CHIP-LED0603")
      (libsource (lib "eagle-import") (part "LEDCHIP-LED0603"))
    )
    (comp (ref "LED408")
      (value "LEDCHIP-LED0603")
      (footprint "eagle-import:CHIP-LED0603")
      (libsource (lib "eagle-import") (part "LEDCHIP-LED0603"))
    )
    (comp (ref "LED413")
      (value "LEDCHIP-LED0603")
      (footprint "eagle-import:CHIP-LED0603")
      (libsource (lib "eagle-import") (part "LEDCHIP-LED0603"))
    )
    (comp (ref "LED414")
      (value "LEDCHIP-LED0603")
      (footprint "eagle-import:CHIP-LED0603")
      (libsource (lib "eagle-import") (part "LEDCHIP-LED0603"))
    )
    (comp (ref "LED415")
      (value "LEDCHIP-LED0603")
      (footprint "eagle-import:CHIP-LED0603")
      (libsource (lib "eagle-import") (part "LEDCHIP-LED0603"))
    )
    (comp (ref "LED416")
      (value "LEDCHIP-LED0603")
      (footprint "eagle-import:CHIP-LED0603")
      (libsource (lib "eagle-import") (part "LEDCHIP-LED0603"))
    )
    (comp (ref "R5")
      (value "R-US_R0603")
      (footprint "eagle-import:R0603")
      (libsource (lib "eagle-import") (part "R-US_R0603"))
    )
    (comp (ref "R6")
      (value "R-US_R0603")
      (footprint "eagle-import:R0603")
      (libsource (lib "eagle-import") (part "R-US_R0603"))
    )
    (comp (ref "R7")
      (value "R-US_R0603")
      (footprint "eagle-import:R0603")
      (libsource (lib "eagle-import") (part "R-US_R0603"))
    )
    (comp (ref "R8")
      (value "R-US_R0603")
      (footprint "eagle-import:R0603")
      (libsource (lib "eagle-import") (part "R-US_R0603"))
    )
    (comp (ref "R9")
      (value "R-US_R0603")
      (footprint "eagle-import:R0603")
      (libsource (lib "eagle-import") (part "R-US_R0603"))
    )
    (comp (ref "R10")
      (value "R-US_R0603")
      (footprint "eagle-import:R0603")
      (libsource (lib "eagle-import") (part "R-US_R0603"))
    )
    (comp (ref "R11")
      (value "R-US_R0603")
      (footprint "eagle-import:R0603")
      (libsource (lib "eagle-import") (part "R-US_R0603"))
    )
    (comp (ref "R12")
      (value "R-US_R0603")
      (footprint "eagle-import:R0603")
      (libsource (lib "eagle-import") (part "R-US_R0603"))
    )
    (comp (ref "R13")
      (value "R-US_R0603")
      (footprint "eagle-import:R0603")
      (libsource (lib "eagle-import") (part "R-US_R0603"))
    )
    (comp (ref "R14")
      (value "R-US_R0603")
      (footprint "eagle-import:R0603")
      (libsource (lib "eagle-import") (part "R-US_R0603"))
    )
    (comp (ref "R15")
      (value "R-US_R0603")
      (footprint "eagle-import:R0603")
      (libsource (lib "eagle-import") (part "R-US_R0603"))
    )
    (comp (ref "R16")
      (value "R-US_R0603")
      (footprint "eagle-import:R0603")
      (libsource (lib "eagle-import") (part "R-US_R0603"))
    )
    (comp (ref "R17")
      (value "R-US_R0603")
      (footprint "eagle-import:R0603")
      (libsource (lib "eagle-import") (part "R-US_R0603"))
    )
    (comp (ref "R18")
      (value "R-US_R0603")
      (footprint "eagle-import:R0603")
      (libsource (lib "eagle-import") (part "R-US_R0603"))
    )
    (comp (ref "R19")
      (value "R-US_R0603")
      (footprint "eagle-import:R0603")
      (libsource (lib "eagle-import") (part "R-US_R0603"))
    )
    (comp (ref "R20")
      (value "R-US_R0603")
      (footprint "eagle-import:R0603")
      (libsource (lib "eagle-import") (part "R-US_R0603"))
    )
    (comp (ref "R21")
      (value "R-US_R0603")
      (footprint "eagle-import:R0603")
      (libsource (lib "eagle-import") (part "R-US_R0603"))
    )
    (comp (ref "R22")
      (value "R-US_R0603")
      (footprint "eagle-import:R0603")
      (libsource (lib "eagle-import") (part "R-US_R0603"))
    )
    (comp (ref "R23")
      (value "R-US_R0603")
      (footprint "eagle-import:R0603")
      (libsource (lib "eagle-import") (part "R-US_R0603"))
    )
    (comp (ref "R24")
      (value "R-US_R0603")
      (footprint "eagle-import:R0603")
      (libsource (lib "eagle-import") (part "R-US_R0603"))
    )
    (comp (ref "R25")
      (value "R-US_R0603")
      (footprint "eagle-import:R0603")
      (libsource (lib "eagle-import") (part "R-US_R0603"))
    )
    (comp (ref "R26")
      (value "R-US_R0603")
      (footprint "eagle-import:R0603")
      (libsource (lib "eagle-import") (part "R-US_R0603"))
    )
    (comp (ref "R27")
      (value "R-US_R0603")
      (footprint "eagle-import:R0603")
      (libsource (lib "eagle-import") (part "R-US_R0603"))
    )
    (comp (ref "R28")
      (value "R-US_R0603")
      (footprint "eagle-import:R0603")
      (libsource (lib "eagle-import") (part "R-US_R0603"))
    )
    (comp (ref "R29")
      (value "R-US_R0603")
      (footprint "eagle-import:R0603")
      (libsource (lib "eagle-import") (part "R-US_R0603"))
    )
    (comp (ref "R30")
      (value "R-US_R0603")
      (footprint "eagle-import:R0603")
      (libsource (lib "eagle-import") (part "R-US_R0603"))
    )
    (comp (ref "R31")
      (value "R-US_R0603")
      (footprint "eagle-import:R0603")
      (libsource (lib "eagle-import") (part "R-US_R0603"))
    )
    (comp (ref "R32")
      (value "R-US_R0603")
      (footprint "eagle-import:R0603")
      (libsource (lib "eagle-import") (part "R-US_R0603"))
    )
    (comp (ref "R33")
      (value "R-US_R0603")
      (footprint "eagle-import:R0603")
      (libsource (lib "eagle-import") (part "R-US_R0603"))
    )
    (comp (ref "R34")
      (value "R-US_R0603")
      (footprint "eagle-import:R0603")
      (libsource (lib "eagle-import") (part "R-US_R0603"))
    )
    (comp (ref "R35")
      (value "R-US_R0603")
      (footprint "eagle-import:R0603")
      (libsource (lib "eagle-import") (part "R-US_R0603"))
    )
    (comp (ref "R36")
      (value "R-US_R0603")
      (footprint "eagle-import:R0603")
      (libsource (lib "eagle-import") (part "R-US_R0603"))
    )
    (comp (ref "R37")
      (value "R-US_R0603")
      (footprint "eagle-import:R0603")
      (libsource (lib "eagle-import") (part "R-US_R0603"))
    )
    (comp (ref "R38")
      (value "R-US_R0603")
      (footprint "eagle-import:R0603")
      (libsource (lib "eagle-import") (part "R-US_R0603"))
    )
    (comp (ref "R39")
      (value "R-US_R0603")
      (footprint "eagle-import:R0603")
      (libsource (lib "eagle-import") (part "R-US_R0603"))
    )
    (comp (ref "R40")
      (value "R-US_R0603")
      (footprint "eagle-import:R0603")
      (libsource (lib "eagle-import") (part "R-US_R0603"))
    )
    (comp (ref "R45")
      (value "R-US_R0603")
      (footprint "eagle-import:R0603")
      (libsource (lib "eagle-import") (part "R-US_R0603"))
    )
    (comp (ref "R46")
      (value "R-US_R0603")
      (footprint "eagle-import:R0603")
      (libsource (lib "eagle-import") (part "R-US_R0603"))
    )
    (comp (ref "R47")
      (value "R-US_R0603")
      (footprint "eagle-import:R0603")
      (libsource (lib "eagle-import") (part "R-US_R0603"))
    )
    (comp (ref "R48")
      (value "R-US_R0603")
      (footprint "eagle-import:R0603")
      (libsource (lib "eagle-import") (part "R-US_R0603"))
    )
    (comp (ref "R49")
      (value "R-US_R0603")
      (footprint "eagle-import:R0603")
      (libsource (lib "eagle-import") (part "R-US_R0603"))
    )
    (comp (ref "R50")
      (value "R-US_R0603")
      (footprint "eagle-import:R0603")
      (libsource (lib "eagle-import") (part "R-US_R0603"))
    )
    (comp (ref "R51")
      (value "R-US_R0603")
      (footprint "eagle-import:R0603")
      (libsource (lib "eagle-import") (part "R-US_R0603"))
    )
    (comp (ref "R52")
      (value "R-US_R0603")
      (footprint "eagle-import:R0603")
      (libsource (lib "eagle-import") (part "R-US_R0603"))
    )
    (comp (ref "R53")
      (value "R-US_R0603")
      (footprint "eagle-import:R0603")
      (libsource (lib "eagle-import") (part "R-US_R0603"))
    )
    (comp (ref "R54")
      (value "R-US_R0603")
      (footprint "eagle-import:R0603")
      (libsource (lib "eagle-import") (part "R-US_R0603"))
    )
    (comp (ref "R55")
      (value "R-US_R0603")
      (footprint "eagle-import:R0603")
      (libsource (lib "eagle-import") (part "R-US_R0603"))
    )
    (comp (ref "R56")
      (value "R-US_R0603")
      (footprint "eagle-import:R0603")
      (libsource (lib "eagle-import") (part "R-US_R0603"))
    )
    (comp (ref "R61")
      (value "R-US_R0603")
      (footprint "eagle-import:R0603")
      (libsource (lib "eagle-import") (part "R-US_R0603"))
    )
    (comp (ref "R62")
      (value "R-US_R0603")
      (footprint "eagle-import:R0603")
      (libsource (lib "eagle-import") (part "R-US_R0603"))
    )
    (comp (ref "R63")
      (value "R-US_R0603")
      (footprint "eagle-import:R0603")
      (libsource (lib "eagle-import") (part "R-US_R0603"))
    )
    (comp (ref "R64")
      (value "R-US_R0603")
      (footprint "eagle-import:R0603")
      (libsource (lib "eagle-import") (part "R-US_R0603"))
    )
    (comp (ref "R65")
      (value "R-US_R0603")
      (footprint "eagle-import:R0603")
      (libsource (lib "eagle-import") (part "R-US_R0603"))
    )
    (comp (ref "R66")
      (value "R-US_R0603")
      (footprint "eagle-import:R0603")
      (libsource (lib "eagle-import") (part "R-US_R0603"))
    )
    (comp (ref "R67")
      (value "R-US_R0603")
      (footprint "eagle-import:R0603")
      (libsource (lib "eagle-import") (part "R-US_R0603"))
    )
    (comp (ref "R68")
      (value "R-US_R0603")
      (footprint "eagle-import:R0603")
      (libsource (lib "eagle-import") (part "R-US_R0603"))
    )
    (comp (ref "R69")
      (value "R-US_R0603")
      (footprint "eagle-import:R0603")
      (libsource (lib "eagle-import") (part "R-US_R0603"))
    )
    (comp (ref "R70")
      (value "R-US_R0603")
      (footprint "eagle-import:R0603")
      (libsource (lib "eagle-import") (part "R-US_R0603"))
    )
    (comp (ref "R71")
      (value "R-US_R0603")
      (footprint "eagle-import:R0603")
      (libsource (lib "eagle-import") (part "R-US_R0603"))
    )
    (comp (ref "R72")
      (value "R-US_R0603")
      (footprint "eagle-import:R0603")
      (libsource (lib "eagle-import") (part "R-US_R0603"))
    )
    (comp (ref "R77")
      (value "R-US_R0603")
      (footprint "eagle-import:R0603")
      (libsource (lib "eagle-import") (part "R-US_R0603"))
    )
    (comp (ref "R78")
      (value "R-US_R0603")
      (footprint "eagle-import:R0603")
      (libsource (lib "eagle-import") (part "R-US_R0603"))
    )
    (comp (ref "R79")
      (value "R-US_R0603")
      (footprint "eagle-import:R0603")
      (libsource (lib "eagle-import") (part "R-US_R0603"))
    )
    (comp (ref "R80")
      (value "R-US_R0603")
      (footprint "eagle-import:R0603")
      (libsource (lib "eagle-import") (part "R-US_R0603"))
    )
    (comp (ref "R85")
      (value "R-US_R0603")
      (footprint "eagle-import:R0603")
      (libsource (lib "eagle-import") (part "R-US_R0603"))
    )
    (comp (ref "R86")
      (value "R-US_R0603")
      (footprint "eagle-import:R0603")
      (libsource (lib "eagle-import") (part "R-US_R0603"))
    )
    (comp (ref "R87")
      (value "R-US_R0603")
      (footprint "eagle-import:R0603")
      (libsource (lib "eagle-import") (part "R-US_R0603"))
    )
    (comp (ref "R88")
      (value "R-US_R0603")
      (footprint "eagle-import:R0603")
      (libsource (lib "eagle-import") (part "R-US_R0603"))
    )
    (comp (ref "R93")
      (value "R-US_R0603")
      (footprint "eagle-import:R0603")
      (libsource (lib "eagle-import") (part "R-US_R0603"))
    )
    (comp (ref "R94")
      (value "R-US_R0603")
      (footprint "eagle-import:R0603")
      (libsource (lib "eagle-import") (part "R-US_R0603"))
    )
    (comp (ref "R95")
      (value "R-US_R0603")
      (footprint "eagle-import:R0603")
      (libsource (lib "eagle-import") (part "R-US_R0603"))
    )
    (comp (ref "R96")
      (value "R-US_R0603")
      (footprint "eagle-import:R0603")
      (libsource (lib "eagle-import") (part "R-US_R0603"))
    )
    (comp (ref "R101")
      (value "R-US_R0603")
      (footprint "eagle-import:R0603")
      (libsource (lib "eagle-import") (part "R-US_R0603"))
    )
    (comp (ref "R102")
      (value "R-US_R0603")
      (footprint "eagle-import:R0603")
      (libsource (lib "eagle-import") (part "R-US_R0603"))
    )
    (comp (ref "R103")
      (value "R-US_R0603")
      (footprint "eagle-import:R0603")
      (libsource (lib "eagle-import") (part "R-US_R0603"))
    )
    (comp (ref "R104")
      (value "R-US_R0603")
      (footprint "eagle-import:R0603")
      (libsource (lib "eagle-import") (part "R-US_R0603"))
    )
    (comp (ref "R109")
      (value "R-US_R0603")
      (footprint "eagle-import:R0603")
      (libsource (lib "eagle-import") (part "R-US_R0603"))
    )
    (comp (ref "R110")
      (value "R-US_R0603")
      (footprint "eagle-import:R0603")
      (libsource (lib "eagle-import") (part "R-US_R0603"))
    )
    (comp (ref "R111")
      (value "R-US_R0603")
      (footprint "eagle-import:R0603")
      (libsource (lib "eagle-import") (part "R-US_R0603"))
    )
    (comp (ref "R112")
      (value "R-US_R0603")
      (footprint "eagle-import:R0603")
      (libsource (lib "eagle-import") (part "R-US_R0603"))
    )
    (comp (ref "R117")
      (value "R-US_R0603")
      (footprint "eagle-import:R0603")
      (libsource (lib "eagle-import") (part "R-US_R0603"))
    )
    (comp (ref "R118")
      (value "R-US_R0603")
      (footprint "eagle-import:R0603")
      (libsource (lib "eagle-import") (part "R-US_R0603"))
    )
    (comp (ref "R119")
      (value "R-US_R0603")
      (footprint "eagle-import:R0603")
      (libsource (lib "eagle-import") (part "R-US_R0603"))
    )
    (comp (ref "R120")
      (value "R-US_R0603")
      (footprint "eagle-import:R0603")
      (libsource (lib "eagle-import") (part "R-US_R0603"))
    )
    (comp (ref "R125")
      (value "R-US_R0603")
      (footprint "eagle-import:R0603")
      (libsource (lib "eagle-import") (part "R-US_R0603"))
    )
    (comp (ref "R126")
      (value "R-US_R0603")
      (footprint "eagle-import:R0603")
      (libsource (lib "eagle-import") (part "R-US_R0603"))
    )
    (comp (ref "R127")
      (value "R-US_R0603")
      (footprint "eagle-import:R0603")
      (libsource (lib "eagle-import") (part "R-US_R0603"))
    )
    (comp (ref "R128")
      (value "R-US_R0603")
      (footprint "eagle-import:R0603")
      (libsource (lib "eagle-import") (part "R-US_R0603"))
    )
    (comp (ref "R133")
      (value "R-US_R0603")
      (footprint "eagle-import:R0603")
      (libsource (lib "eagle-import") (part "R-US_R0603"))
    )
    (comp (ref "R134")
      (value "R-US_R0603")
      (footprint "eagle-import:R0603")
      (libsource (lib "eagle-import") (part "R-US_R0603"))
    )
    (comp (ref "R135")
      (value "R-US_R0603")
      (footprint "eagle-import:R0603")
      (libsource (lib "eagle-import") (part "R-US_R0603"))
    )
    (comp (ref "R136")
      (value "R-US_R0603")
      (footprint "eagle-import:R0603")
      (libsource (lib "eagle-import") (part "R-US_R0603"))
    )
    (comp (ref "R141")
      (value "R-US_R0603")
      (footprint "eagle-import:R0603")
      (libsource (lib "eagle-import") (part "R-US_R0603"))
    )
    (comp (ref "R142")
      (value "R-US_R0603")
      (footprint "eagle-import:R0603")
      (libsource (lib "eagle-import") (part "R-US_R0603"))
    )
    (comp (ref "R143")
      (value "R-US_R0603")
      (footprint "eagle-import:R0603")
      (libsource (lib "eagle-import") (part "R-US_R0603"))
    )
    (comp (ref "R144")
      (value "R-US_R0603")
      (footprint "eagle-import:R0603")
      (libsource (lib "eagle-import") (part "R-US_R0603"))
    )
    (comp (ref "R149")
      (value "R-US_R0603")
      (footprint "eagle-import:R0603")
      (libsource (lib "eagle-import") (part "R-US_R0603"))
    )
    (comp (ref "R150")
      (value "R-US_R0603")
      (footprint "eagle-import:R0603")
      (libsource (lib "eagle-import") (part "R-US_R0603"))
    )
    (comp (ref "R151")
      (value "R-US_R0603")
      (footprint "eagle-import:R0603")
      (libsource (lib "eagle-import") (part "R-US_R0603"))
    )
    (comp (ref "R152")
      (value "R-US_R0603")
      (footprint "eagle-import:R0603")
      (libsource (lib "eagle-import") (part "R-US_R0603"))
    )
    (comp (ref "R157")
      (value "R-US_R0603")
      (footprint "eagle-import:R0603")
      (libsource (lib "eagle-import") (part "R-US_R0603"))
    )
    (comp (ref "R158")
      (value "R-US_R0603")
      (footprint "eagle-import:R0603")
      (libsource (lib "eagle-import") (part "R-US_R0603"))
    )
    (comp (ref "R159")
      (value "R-US_R0603")
      (footprint "eagle-import:R0603")
      (libsource (lib "eagle-import") (part "R-US_R0603"))
    )
    (comp (ref "R160")
      (value "R-US_R0603")
      (footprint "eagle-import:R0603")
      (libsource (lib "eagle-import") (part "R-US_R0603"))
    )
    (comp (ref "R165")
      (value "R-US_R0603")
      (footprint "eagle-import:R0603")
      (libsource (lib "eagle-import") (part "R-US_R0603"))
    )
    (comp (ref "R166")
      (value "R-US_R0603")
      (footprint "eagle-import:R0603")
      (libsource (lib "eagle-import") (part "R-US_R0603"))
    )
    (comp (ref "R167")
      (value "R-US_R0603")
      (footprint "eagle-import:R0603")
      (libsource (lib "eagle-import") (part "R-US_R0603"))
    )
    (comp (ref "R168")
      (value "R-US_R0603")
      (footprint "eagle-import:R0603")
      (libsource (lib "eagle-import") (part "R-US_R0603"))
    )
    (comp (ref "R173")
      (value "R-US_R0603")
      (footprint "eagle-import:R0603")
      (libsource (lib "eagle-import") (part "R-US_R0603"))
    )
    (comp (ref "R174")
      (value "R-US_R0603")
      (footprint "eagle-import:R0603")
      (libsource (lib "eagle-import") (part "R-US_R0603"))
    )
    (comp (ref "R175")
      (value "R-US_R0603")
      (footprint "eagle-import:R0603")
      (libsource (lib "eagle-import") (part "R-US_R0603"))
    )
    (comp (ref "R176")
      (value "R-US_R0603")
      (footprint "eagle-import:R0603")
      (libsource (lib "eagle-import") (part "R-US_R0603"))
    )
    (comp (ref "R181")
      (value "R-US_R0603")
      (footprint "eagle-import:R0603")
      (libsource (lib "eagle-import") (part "R-US_R0603"))
    )
    (comp (ref "R182")
      (value "R-US_R0603")
      (footprint "eagle-import:R0603")
      (libsource (lib "eagle-import") (part "R-US_R0603"))
    )
    (comp (ref "R183")
      (value "R-US_R0603")
      (footprint "eagle-import:R0603")
      (libsource (lib "eagle-import") (part "R-US_R0603"))
    )
    (comp (ref "R184")
      (value "R-US_R0603")
      (footprint "eagle-import:R0603")
      (libsource (lib "eagle-import") (part "R-US_R0603"))
    )
    (comp (ref "R189")
      (value "R-US_R0603")
      (footprint "eagle-import:R0603")
      (libsource (lib "eagle-import") (part "R-US_R0603"))
    )
    (comp (ref "R190")
      (value "R-US_R0603")
      (footprint "eagle-import:R0603")
      (libsource (lib "eagle-import") (part "R-US_R0603"))
    )
    (comp (ref "R191")
      (value "R-US_R0603")
      (footprint "eagle-import:R0603")
      (libsource (lib "eagle-import") (part "R-US_R0603"))
    )
    (comp (ref "R192")
      (value "R-US_R0603")
      (footprint "eagle-import:R0603")
      (libsource (lib "eagle-import") (part "R-US_R0603"))
    )
    (comp (ref "R197")
      (value "R-US_R0603")
      (footprint "eagle-import:R0603")
      (libsource (lib "eagle-import") (part "R-US_R0603"))
    )
    (comp (ref "R198")
      (value "R-US_R0603")
      (footprint "eagle-import:R0603")
      (libsource (lib "eagle-import") (part "R-US_R0603"))
    )
    (comp (ref "R199")
      (value "R-US_R0603")
      (footprint "eagle-import:R0603")
      (libsource (lib "eagle-import") (part "R-US_R0603"))
    )
    (comp (ref "R200")
      (value "R-US_R0603")
      (footprint "eagle-import:R0603")
      (libsource (lib "eagle-import") (part "R-US_R0603"))
    )
    (comp (ref "R205")
      (value "R-US_R0603")
      (footprint "eagle-import:R0603")
      (libsource (lib "eagle-import") (part "R-US_R0603"))
    )
    (comp (ref "R206")
      (value "R-US_R0603")
      (footprint "eagle-import:R0603")
      (libsource (lib "eagle-import") (part "R-US_R0603"))
    )
    (comp (ref "R207")
      (value "R-US_R0603")
      (footprint "eagle-import:R0603")
      (libsource (lib "eagle-import") (part "R-US_R0603"))
    )
    (comp (ref "R208")
      (value "R-US_R0603")
      (footprint "eagle-import:R0603")
      (libsource (lib "eagle-import") (part "R-US_R0603"))
    )
    (comp (ref "R213")
      (value "R-US_R0603")
      (footprint "eagle-import:R0603")
      (libsource (lib "eagle-import") (part "R-US_R0603"))
    )
    (comp (ref "R214")
      (value "R-US_R0603")
      (footprint "eagle-import:R0603")
      (libsource (lib "eagle-import") (part "R-US_R0603"))
    )
    (comp (ref "R215")
      (value "R-US_R0603")
      (footprint "eagle-import:R0603")
      (libsource (lib "eagle-import") (part "R-US_R0603"))
    )
    (comp (ref "R216")
      (value "R-US_R0603")
      (footprint "eagle-import:R0603")
      (libsource (lib "eagle-import") (part "R-US_R0603"))
    )
    (comp (ref "R221")
      (value "R-US_R0603")
      (footprint "eagle-import:R0603")
      (libsource (lib "eagle-import") (part "R-US_R0603"))
    )
    (comp (ref "R222")
      (value "R-US_R0603")
      (footprint "eagle-import:R0603")
      (libsource (lib "eagle-import") (part "R-US_R0603"))
    )
    (comp (ref "R223")
      (value "R-US_R0603")
      (footprint "eagle-import:R0603")
      (libsource (lib "eagle-import") (part "R-US_R0603"))
    )
    (comp (ref "R224")
      (value "R-US_R0603")
      (footprint "eagle-import:R0603")
      (libsource (lib "eagle-import") (part "R-US_R0603"))
    )
    (comp (ref "R229")
      (value "R-US_R0603")
      (footprint "eagle-import:R0603")
      (libsource (lib "eagle-import") (part "R-US_R0603"))
    )
    (comp (ref "R230")
      (value "R-US_R0603")
      (footprint "eagle-import:R0603")
      (libsource (lib "eagle-import") (part "R-US_R0603"))
    )
    (comp (ref "R231")
      (value "R-US_R0603")
      (footprint "eagle-import:R0603")
      (libsource (lib "eagle-import") (part "R-US_R0603"))
    )
    (comp (ref "R232")
      (value "R-US_R0603")
      (footprint "eagle-import:R0603")
      (libsource (lib "eagle-import") (part "R-US_R0603"))
    )
    (comp (ref "R237")
      (value "R-US_R0603")
      (footprint "eagle-import:R0603")
      (libsource (lib "eagle-import") (part "R-US_R0603"))
    )
    (comp (ref "R238")
      (value "R-US_R0603")
      (footprint "eagle-import:R0603")
      (libsource (lib "eagle-import") (part "R-US_R0603"))
    )
    (comp (ref "R239")
      (value "R-US_R0603")
      (footprint "eagle-import:R0603")
      (libsource (lib "eagle-import") (part "R-US_R0603"))
    )
    (comp (ref "R240")
      (value "R-US_R0603")
      (footprint "eagle-import:R0603")
      (libsource (lib "eagle-import") (part "R-US_R0603"))
    )
    (comp (ref "R245")
      (value "R-US_R0603")
      (footprint "eagle-import:R0603")
      (libsource (lib "eagle-import") (part "R-US_R0603"))
    )
    (comp (ref "R246")
      (value "R-US_R0603")
      (footprint "eagle-import:R0603")
      (libsource (lib "eagle-import") (part "R-US_R0603"))
    )
    (comp (ref "R247")
      (value "R-US_R0603")
      (footprint "eagle-import:R0603")
      (libsource (lib "eagle-import") (part "R-US_R0603"))
    )
    (comp (ref "R248")
      (value "R-US_R0603")
      (footprint "eagle-import:R0603")
      (libsource (lib "eagle-import") (part "R-US_R0603"))
    )
    (comp (ref "R253")
      (value "R-US_R0603")
      (footprint "eagle-import:R0603")
      (libsource (lib "eagle-import") (part "R-US_R0603"))
    )
    (comp (ref "R254")
      (value "R-US_R0603")
      (footprint "eagle-import:R0603")
      (libsource (lib "eagle-import") (part "R-US_R0603"))
    )
    (comp (ref "R255")
      (value "R-US_R0603")
      (footprint "eagle-import:R0603")
      (libsource (lib "eagle-import") (part "R-US_R0603"))
    )
    (comp (ref "R256")
      (value "R-US_R0603")
      (footprint "eagle-import:R0603")
      (libsource (lib "eagle-import") (part "R-US_R0603"))
    )
    (comp (ref "R261")
      (value "R-US_R0603")
      (footprint "eagle-import:R0603")
      (libsource (lib "eagle-import") (part "R-US_R0603"))
    )
    (comp (ref "R262")
      (value "R-US_R0603")
      (footprint "eagle-import:R0603")
      (libsource (lib "eagle-import") (part "R-US_R0603"))
    )
    (comp (ref "R263")
      (value "R-US_R0603")
      (footprint "eagle-import:R0603")
      (libsource (lib "eagle-import") (part "R-US_R0603"))
    )
    (comp (ref "R264")
      (value "R-US_R0603")
      (footprint "eagle-import:R0603")
      (libsource (lib "eagle-import") (part "R-US_R0603"))
    )
    (comp (ref "R269")
      (value "R-US_R0603")
      (footprint "eagle-import:R0603")
      (libsource (lib "eagle-import") (part "R-US_R0603"))
    )
    (comp (ref "R270")
      (value "R-US_R0603")
      (footprint "eagle-import:R0603")
      (libsource (lib "eagle-import") (part "R-US_R0603"))
    )
    (comp (ref "R271")
      (value "R-US_R0603")
      (footprint "eagle-import:R0603")
      (libsource (lib "eagle-import") (part "R-US_R0603"))
    )
    (comp (ref "R272")
      (value "R-US_R0603")
      (footprint "eagle-import:R0603")
      (libsource (lib "eagle-import") (part "R-US_R0603"))
    )
    (comp (ref "R277")
      (value "R-US_R0603")
      (footprint "eagle-import:R0603")
      (libsource (lib "eagle-import") (part "R-US_R0603"))
    )
    (comp (ref "R278")
      (value "R-US_R0603")
      (footprint "eagle-import:R0603")
      (libsource (lib "eagle-import") (part "R-US_R0603"))
    )
    (comp (ref "R279")
      (value "R-US_R0603")
      (footprint "eagle-import:R0603")
      (libsource (lib "eagle-import") (part "R-US_R0603"))
    )
    (comp (ref "R280")
      (value "R-US_R0603")
      (footprint "eagle-import:R0603")
      (libsource (lib "eagle-import") (part "R-US_R0603"))
    )
    (comp (ref "R285")
      (value "R-US_R0603")
      (footprint "eagle-import:R0603")
      (libsource (lib "eagle-import") (part "R-US_R0603"))
    )
    (comp (ref "R286")
      (value "R-US_R0603")
      (footprint "eagle-import:R0603")
      (libsource (lib "eagle-import") (part "R-US_R0603"))
    )
    (comp (ref "R287")
      (value "R-US_R0603")
      (footprint "eagle-import:R0603")
      (libsource (lib "eagle-import") (part "R-US_R0603"))
    )
    (comp (ref "R288")
      (value "R-US_R0603")
      (footprint "eagle-import:R0603")
      (libsource (lib "eagle-import") (part "R-US_R0603"))
    )
    (comp (ref "R293")
      (value "R-US_R0603")
      (footprint "eagle-import:R0603")
      (libsource (lib "eagle-import") (part "R-US_R0603"))
    )
    (comp (ref "R294")
      (value "R-US_R0603")
      (footprint "eagle-import:R0603")
      (libsource (lib "eagle-import") (part "R-US_R0603"))
    )
    (comp (ref "R295")
      (value "R-US_R0603")
      (footprint "eagle-import:R0603")
      (libsource (lib "eagle-import") (part "R-US_R0603"))
    )
    (comp (ref "R296")
      (value "R-US_R0603")
      (footprint "eagle-import:R0603")
      (libsource (lib "eagle-import") (part "R-US_R0603"))
    )
    (comp (ref "R301")
      (value "R-US_R0603")
      (footprint "eagle-import:R0603")
      (libsource (lib "eagle-import") (part "R-US_R0603"))
    )
    (comp (ref "R302")
      (value "R-US_R0603")
      (footprint "eagle-import:R0603")
      (libsource (lib "eagle-import") (part "R-US_R0603"))
    )
    (comp (ref "R303")
      (value "R-US_R0603")
      (footprint "eagle-import:R0603")
      (libsource (lib "eagle-import") (part "R-US_R0603"))
    )
    (comp (ref "R304")
      (value "R-US_R0603")
      (footprint "eagle-import:R0603")
      (libsource (lib "eagle-import") (part "R-US_R0603"))
    )
    (comp (ref "R309")
      (value "R-US_R0603")
      (footprint "eagle-import:R0603")
      (libsource (lib "eagle-import") (part "R-US_R0603"))
    )
    (comp (ref "R310")
      (value "R-US_R0603")
      (footprint "eagle-import:R0603")
      (libsource (lib "eagle-import") (part "R-US_R0603"))
    )
    (comp (ref "R311")
      (value "R-US_R0603")
      (footprint "eagle-import:R0603")
      (libsource (lib "eagle-import") (part "R-US_R0603"))
    )
    (comp (ref "R312")
      (value "R-US_R0603")
      (footprint "eagle-import:R0603")
      (libsource (lib "eagle-import") (part "R-US_R0603"))
    )
    (comp (ref "R317")
      (value "R-US_R0603")
      (footprint "eagle-import:R0603")
      (libsource (lib "eagle-import") (part "R-US_R0603"))
    )
    (comp (ref "R318")
      (value "R-US_R0603")
      (footprint "eagle-import:R0603")
      (libsource (lib "eagle-import") (part "R-US_R0603"))
    )
    (comp (ref "R319")
      (value "R-US_R0603")
      (footprint "eagle-import:R0603")
      (libsource (lib "eagle-import") (part "R-US_R0603"))
    )
    (comp (ref "R320")
      (value "R-US_R0603")
      (footprint "eagle-import:R0603")
      (libsource (lib "eagle-import") (part "R-US_R0603"))
    )
    (comp (ref "R325")
      (value "R-US_R0603")
      (footprint "eagle-import:R0603")
      (libsource (lib "eagle-import") (part "R-US_R0603"))
    )
    (comp (ref "R326")
      (value "R-US_R0603")
      (footprint "eagle-import:R0603")
      (libsource (lib "eagle-import") (part "R-US_R0603"))
    )
    (comp (ref "R327")
      (value "R-US_R0603")
      (footprint "eagle-import:R0603")
      (libsource (lib "eagle-import") (part "R-US_R0603"))
    )
    (comp (ref "R328")
      (value "R-US_R0603")
      (footprint "eagle-import:R0603")
      (libsource (lib "eagle-import") (part "R-US_R0603"))
    )
    (comp (ref "R333")
      (value "R-US_R0603")
      (footprint "eagle-import:R0603")
      (libsource (lib "eagle-import") (part "R-US_R0603"))
    )
    (comp (ref "R334")
      (value "R-US_R0603")
      (footprint "eagle-import:R0603")
      (libsource (lib "eagle-import") (part "R-US_R0603"))
    )
    (comp (ref "R335")
      (value "R-US_R0603")
      (footprint "eagle-import:R0603")
      (libsource (lib "eagle-import") (part "R-US_R0603"))
    )
    (comp (ref "R336")
      (value "R-US_R0603")
      (footprint "eagle-import:R0603")
      (libsource (lib "eagle-import") (part "R-US_R0603"))
    )
    (comp (ref "R341")
      (value "R-US_R0603")
      (footprint "eagle-import:R0603")
      (libsource (lib "eagle-import") (part "R-US_R0603"))
    )
    (comp (ref "R342")
      (value "R-US_R0603")
      (footprint "eagle-import:R0603")
      (libsource (lib "eagle-import") (part "R-US_R0603"))
    )
    (comp (ref "R343")
      (value "R-US_R0603")
      (footprint "eagle-import:R0603")
      (libsource (lib "eagle-import") (part "R-US_R0603"))
    )
    (comp (ref "R344")
      (value "R-US_R0603")
      (footprint "eagle-import:R0603")
      (libsource (lib "eagle-import") (part "R-US_R0603"))
    )
    (comp (ref "R349")
      (value "R-US_R0603")
      (footprint "eagle-import:R0603")
      (libsource (lib "eagle-import") (part "R-US_R0603"))
    )
    (comp (ref "R350")
      (value "R-US_R0603")
      (footprint "eagle-import:R0603")
      (libsource (lib "eagle-import") (part "R-US_R0603"))
    )
    (comp (ref "R351")
      (value "R-US_R0603")
      (footprint "eagle-import:R0603")
      (libsource (lib "eagle-import") (part "R-US_R0603"))
    )
    (comp (ref "R352")
      (value "R-US_R0603")
      (footprint "eagle-import:R0603")
      (libsource (lib "eagle-import") (part "R-US_R0603"))
    )
    (comp (ref "R357")
      (value "R-US_R0603")
      (footprint "eagle-import:R0603")
      (libsource (lib "eagle-import") (part "R-US_R0603"))
    )
    (comp (ref "R358")
      (value "R-US_R0603")
      (footprint "eagle-import:R0603")
      (libsource (lib "eagle-import") (part "R-US_R0603"))
    )
    (comp (ref "R359")
      (value "R-US_R0603")
      (footprint "eagle-import:R0603")
      (libsource (lib "eagle-import") (part "R-US_R0603"))
    )
    (comp (ref "R360")
      (value "R-US_R0603")
      (footprint "eagle-import:R0603")
      (libsource (lib "eagle-import") (part "R-US_R0603"))
    )
    (comp (ref "R365")
      (value "R-US_R0603")
      (footprint "eagle-import:R0603")
      (libsource (lib "eagle-import") (part "R-US_R0603"))
    )
    (comp (ref "R366")
      (value "R-US_R0603")
      (footprint "eagle-import:R0603")
      (libsource (lib "eagle-import") (part "R-US_R0603"))
    )
    (comp (ref "R367")
      (value "R-US_R0603")
      (footprint "eagle-import:R0603")
      (libsource (lib "eagle-import") (part "R-US_R0603"))
    )
    (comp (ref "R368")
      (value "R-US_R0603")
      (footprint "eagle-import:R0603")
      (libsource (lib "eagle-import") (part "R-US_R0603"))
    )
    (comp (ref "R373")
      (value "R-US_R0603")
      (footprint "eagle-import:R0603")
      (libsource (lib "eagle-import") (part "R-US_R0603"))
    )
    (comp (ref "R374")
      (value "R-US_R0603")
      (footprint "eagle-import:R0603")
      (libsource (lib "eagle-import") (part "R-US_R0603"))
    )
    (comp (ref "R375")
      (value "R-US_R0603")
      (footprint "eagle-import:R0603")
      (libsource (lib "eagle-import") (part "R-US_R0603"))
    )
    (comp (ref "R376")
      (value "R-US_R0603")
      (footprint "eagle-import:R0603")
      (libsource (lib "eagle-import") (part "R-US_R0603"))
    )
    (comp (ref "R381")
      (value "R-US_R0603")
      (footprint "eagle-import:R0603")
      (libsource (lib "eagle-import") (part "R-US_R0603"))
    )
    (comp (ref "R382")
      (value "R-US_R0603")
      (footprint "eagle-import:R0603")
      (libsource (lib "eagle-import") (part "R-US_R0603"))
    )
    (comp (ref "R383")
      (value "R-US_R0603")
      (footprint "eagle-import:R0603")
      (libsource (lib "eagle-import") (part "R-US_R0603"))
    )
    (comp (ref "R384")
      (value "R-US_R0603")
      (footprint "eagle-import:R0603")
      (libsource (lib "eagle-import") (part "R-US_R0603"))
    )
    (comp (ref "R389")
      (value "R-US_R0603")
      (footprint "eagle-import:R0603")
      (libsource (lib "eagle-import") (part "R-US_R0603"))
    )
    (comp (ref "R390")
      (value "R-US_R0603")
      (footprint "eagle-import:R0603")
      (libsource (lib "eagle-import") (part "R-US_R0603"))
    )
    (comp (ref "R391")
      (value "R-US_R0603")
      (footprint "eagle-import:R0603")
      (libsource (lib "eagle-import") (part "R-US_R0603"))
    )
    (comp (ref "R392")
      (value "R-US_R0603")
      (footprint "eagle-import:R0603")
      (libsource (lib "eagle-import") (part "R-US_R0603"))
    )
    (comp (ref "R397")
      (value "R-US_R0603")
      (footprint "eagle-import:R0603")
      (libsource (lib "eagle-import") (part "R-US_R0603"))
    )
    (comp (ref "R398")
      (value "R-US_R0603")
      (footprint "eagle-import:R0603")
      (libsource (lib "eagle-import") (part "R-US_R0603"))
    )
    (comp (ref "R399")
      (value "R-US_R0603")
      (footprint "eagle-import:R0603")
      (libsource (lib "eagle-import") (part "R-US_R0603"))
    )
    (comp (ref "R400")
      (value "R-US_R0603")
      (footprint "eagle-import:R0603")
      (libsource (lib "eagle-import") (part "R-US_R0603"))
    )
    (comp (ref "R405")
      (value "R-US_R0603")
      (footprint "eagle-import:R0603")
      (libsource (lib "eagle-import") (part "R-US_R0603"))
    )
    (comp (ref "R406")
      (value "R-US_R0603")
      (footprint "eagle-import:R0603")
      (libsource (lib "eagle-import") (part "R-US_R0603"))
    )
    (comp (ref "R407")
      (value "R-US_R0603")
      (footprint "eagle-import:R0603")
      (libsource (lib "eagle-import") (part "R-US_R0603"))
    )
    (comp (ref "R408")
      (value "R-US_R0603")
      (footprint "eagle-import:R0603")
      (libsource (lib "eagle-import") (part "R-US_R0603"))
    )
    (comp (ref "R413")
      (value "R-US_R0603")
      (footprint "eagle-import:R0603")
      (libsource (lib "eagle-import") (part "R-US_R0603"))
    )
    (comp (ref "R414")
      (value "R-US_R0603")
      (footprint "eagle-import:R0603")
      (libsource (lib "eagle-import") (part "R-US_R0603"))
    )
    (comp (ref "R415")
      (value "R-US_R0603")
      (footprint "eagle-import:R0603")
      (libsource (lib "eagle-import") (part "R-US_R0603"))
    )
    (comp (ref "R416")
      (value "R-US_R0603")
      (footprint "eagle-import:R0603")
      (libsource (lib "eagle-import") (part "R-US_R0603"))
    )
    (comp (ref "U$1")
      (value "MOLEX_0039301022")
      (footprint "eagle-import:MINI-FIT_JR_CONN")
      (libsource (lib "eagle-import") (part "MOLEX_0039301022"))
    )
    (comp (ref "U$2")
      (value "MOLEX_0039301022")
      (footprint "eagle-import:MINI-FIT_JR_CONN")
      (libsource (lib "eagle-import") (part "MOLEX_0039301022"))
    )
  )
  (nets
    (net (code "1") (name "GND") (class "Default")
      (node (ref "LED10") (pin "C") (pinfunction "C_C") (pintype "passive"))
      (node (ref "LED101") (pin "C") (pinfunction "C_C") (pintype "passive"))
      (node (ref "LED102") (pin "C") (pinfunction "C_C") (pintype "passive"))
      (node (ref "LED103") (pin "C") (pinfunction "C_C") (pintype "passive"))
      (node (ref "LED104") (pin "C") (pinfunction "C_C") (pintype "passive"))
      (node (ref "LED109") (pin "C") (pinfunction "C_C") (pintype "passive"))
      (node (ref "LED11") (pin "C") (pinfunction "C_C") (pintype "passive"))
      (node (ref "LED110") (pin "C") (pinfunction "C_C") (pintype "passive"))
      (node (ref "LED111") (pin "C") (pinfunction "C_C") (pintype "passive"))
      (node (ref "LED112") (pin "C") (pinfunction "C_C") (pintype "passive"))
      (node (ref "LED117") (pin "C") (pinfunction "C_C") (pintype "passive"))
      (node (ref "LED118") (pin "C") (pinfunction "C_C") (pintype "passive"))
      (node (ref "LED119") (pin "C") (pinfunction "C_C") (pintype "passive"))
      (node (ref "LED12") (pin "C") (pinfunction "C_C") (pintype "passive"))
      (node (ref "LED120") (pin "C") (pinfunction "C_C") (pintype "passive"))
      (node (ref "LED125") (pin "C") (pinfunction "C_C") (pintype "passive"))
      (node (ref "LED126") (pin "C") (pinfunction "C_C") (pintype "passive"))
      (node (ref "LED127") (pin "C") (pinfunction "C_C") (pintype "passive"))
      (node (ref "LED128") (pin "C") (pinfunction "C_C") (pintype "passive"))
      (node (ref "LED13") (pin "C") (pinfunction "C_C") (pintype "passive"))
      (node (ref "LED133") (pin "C") (pinfunction "C_C") (pintype "passive"))
      (node (ref "LED134") (pin "C") (pinfunction "C_C") (pintype "passive"))
      (node (ref "LED135") (pin "C") (pinfunction "C_C") (pintype "passive"))
      (node (ref "LED136") (pin "C") (pinfunction "C_C") (pintype "passive"))
      (node (ref "LED14") (pin "C") (pinfunction "C_C") (pintype "passive"))
      (node (ref "LED141") (pin "C") (pinfunction "C_C") (pintype "passive"))
      (node (ref "LED142") (pin "C") (pinfunction "C_C") (pintype "passive"))
      (node (ref "LED143") (pin "C") (pinfunction "C_C") (pintype "passive"))
      (node (ref "LED144") (pin "C") (pinfunction "C_C") (pintype "passive"))
      (node (ref "LED149") (pin "C") (pinfunction "C_C") (pintype "passive"))
      (node (ref "LED15") (pin "C") (pinfunction "C_C") (pintype "passive"))
      (node (ref "LED150") (pin "C") (pinfunction "C_C") (pintype "passive"))
      (node (ref "LED151") (pin "C") (pinfunction "C_C") (pintype "passive"))
      (node (ref "LED152") (pin "C") (pinfunction "C_C") (pintype "passive"))
      (node (ref "LED157") (pin "C") (pinfunction "C_C") (pintype "passive"))
      (node (ref "LED158") (pin "C") (pinfunction "C_C") (pintype "passive"))
      (node (ref "LED159") (pin "C") (pinfunction "C_C") (pintype "passive"))
      (node (ref "LED16") (pin "C") (pinfunction "C_C") (pintype "passive"))
      (node (ref "LED160") (pin "C") (pinfunction "C_C") (pintype "passive"))
      (node (ref "LED165") (pin "C") (pinfunction "C_C") (pintype "passive"))
      (node (ref "LED166") (pin "C") (pinfunction "C_C") (pintype "passive"))
      (node (ref "LED167") (pin "C") (pinfunction "C_C") (pintype "passive"))
      (node (ref "LED168") (pin "C") (pinfunction "C_C") (pintype "passive"))
      (node (ref "LED17") (pin "C") (pinfunction "C_C") (pintype "passive"))
      (node (ref "LED173") (pin "C") (pinfunction "C_C") (pintype "passive"))
      (node (ref "LED174") (pin "C") (pinfunction "C_C") (pintype "passive"))
      (node (ref "LED175") (pin "C") (pinfunction "C_C") (pintype "passive"))
      (node (ref "LED176") (pin "C") (pinfunction "C_C") (pintype "passive"))
      (node (ref "LED18") (pin "C") (pinfunction "C_C") (pintype "passive"))
      (node (ref "LED181") (pin "C") (pinfunction "C_C") (pintype "passive"))
      (node (ref "LED182") (pin "C") (pinfunction "C_C") (pintype "passive"))
      (node (ref "LED183") (pin "C") (pinfunction "C_C") (pintype "passive"))
      (node (ref "LED184") (pin "C") (pinfunction "C_C") (pintype "passive"))
      (node (ref "LED189") (pin "C") (pinfunction "C_C") (pintype "passive"))
      (node (ref "LED19") (pin "C") (pinfunction "C_C") (pintype "passive"))
      (node (ref "LED190") (pin "C") (pinfunction "C_C") (pintype "passive"))
      (node (ref "LED191") (pin "C") (pinfunction "C_C") (pintype "passive"))
      (node (ref "LED192") (pin "C") (pinfunction "C_C") (pintype "passive"))
      (node (ref "LED197") (pin "C") (pinfunction "C_C") (pintype "passive"))
      (node (ref "LED198") (pin "C") (pinfunction "C_C") (pintype "passive"))
      (node (ref "LED199") (pin "C") (pinfunction "C_C") (pintype "passive"))
      (node (ref "LED20") (pin "C") (pinfunction "C_C") (pintype "passive"))
      (node (ref "LED200") (pin "C") (pinfunction "C_C") (pintype "passive"))
      (node (ref "LED205") (pin "C") (pinfunction "C_C") (pintype "passive"))
      (node (ref "LED206") (pin "C") (pinfunction "C_C") (pintype "passive"))
      (node (ref "LED207") (pin "C") (pinfunction "C_C") (pintype "passive"))
      (node (ref "LED208") (pin "C") (pinfunction "C_C") (pintype "passive"))
      (node (ref "LED21") (pin "C") (pinfunction "C_C") (pintype "passive"))
      (node (ref "LED213") (pin "C") (pinfunction "C_C") (pintype "passive"))
      (node (ref "LED214") (pin "C") (pinfunction "C_C") (pintype "passive"))
      (node (ref "LED215") (pin "C") (pinfunction "C_C") (pintype "passive"))
      (node (ref "LED216") (pin "C") (pinfunction "C_C") (pintype "passive"))
      (node (ref "LED22") (pin "C") (pinfunction "C_C") (pintype "passive"))
      (node (ref "LED221") (pin "C") (pinfunction "C_C") (pintype "passive"))
      (node (ref "LED222") (pin "C") (pinfunction "C_C") (pintype "passive"))
      (node (ref "LED223") (pin "C") (pinfunction "C_C") (pintype "passive"))
      (node (ref "LED224") (pin "C") (pinfunction "C_C") (pintype "passive"))
      (node (ref "LED229") (pin "C") (pinfunction "C_C") (pintype "passive"))
      (node (ref "LED23") (pin "C") (pinfunction "C_C") (pintype "passive"))
      (node (ref "LED230") (pin "C") (pinfunction "C_C") (pintype "passive"))
      (node (ref "LED231") (pin "C") (pinfunction "C_C") (pintype "passive"))
      (node (ref "LED232") (pin "C") (pinfunction "C_C") (pintype "passive"))
      (node (ref "LED237") (pin "C") (pinfunction "C_C") (pintype "passive"))
      (node (ref "LED238") (pin "C") (pinfunction "C_C") (pintype "passive"))
      (node (ref "LED239") (pin "C") (pinfunction "C_C") (pintype "passive"))
      (node (ref "LED24") (pin "C") (pinfunction "C_C") (pintype "passive"))
      (node (ref "LED240") (pin "C") (pinfunction "C_C") (pintype "passive"))
      (node (ref "LED245") (pin "C") (pinfunction "C_C") (pintype "passive"))
      (node (ref "LED246") (pin "C") (pinfunction "C_C") (pintype "passive"))
      (node (ref "LED247") (pin "C") (pinfunction "C_C") (pintype "passive"))
      (node (ref "LED248") (pin "C") (pinfunction "C_C") (pintype "passive"))
      (node (ref "LED25") (pin "C") (pinfunction "C_C") (pintype "passive"))
      (node (ref "LED253") (pin "C") (pinfunction "C_C") (pintype "passive"))
      (node (ref "LED254") (pin "C") (pinfunction "C_C") (pintype "passive"))
      (node (ref "LED255") (pin "C") (pinfunction "C_C") (pintype "passive"))
      (node (ref "LED256") (pin "C") (pinfunction "C_C") (pintype "passive"))
      (node (ref "LED26") (pin "C") (pinfunction "C_C") (pintype "passive"))
      (node (ref "LED261") (pin "C") (pinfunction "C_C") (pintype "passive"))
      (node (ref "LED262") (pin "C") (pinfunction "C_C") (pintype "passive"))
      (node (ref "LED263") (pin "C") (pinfunction "C_C") (pintype "passive"))
      (node (ref "LED264") (pin "C") (pinfunction "C_C") (pintype "passive"))
      (node (ref "LED269") (pin "C") (pinfunction "C_C") (pintype "passive"))
      (node (ref "LED27") (pin "C") (pinfunction "C_C") (pintype "passive"))
      (node (ref "LED270") (pin "C") (pinfunction "C_C") (pintype "passive"))
      (node (ref "LED271") (pin "C") (pinfunction "C_C") (pintype "passive"))
      (node (ref "LED272") (pin "C") (pinfunction "C_C") (pintype "passive"))
      (node (ref "LED277") (pin "C") (pinfunction "C_C") (pintype "passive"))
      (node (ref "LED278") (pin "C") (pinfunction "C_C") (pintype "passive"))
      (node (ref "LED279") (pin "C") (pinfunction "C_C") (pintype "passive"))
      (node (ref "LED28") (pin "C") (pinfunction "C_C") (pintype "passive"))
      (node (ref "LED280") (pin "C") (pinfunction "C_C") (pintype "passive"))
      (node (ref "LED285") (pin "C") (pinfunction "C_C") (pintype "passive"))
      (node (ref "LED286") (pin "C") (pinfunction "C_C") (pintype "passive"))
      (node (ref "LED287") (pin "C") (pinfunction "C_C") (pintype "passive"))
      (node (ref "LED288") (pin "C") (pinfunction "C_C") (pintype "passive"))
      (node (ref "LED29") (pin "C") (pinfunction "C_C") (pintype "passive"))
      (node (ref "LED293") (pin "C") (pinfunction "C_C") (pintype "passive"))
      (node (ref "LED294") (pin "C") (pinfunction "C_C") (pintype "passive"))
      (node (ref "LED295") (pin "C") (pinfunction "C_C") (pintype "passive"))
      (node (ref "LED296") (pin "C") (pinfunction "C_C") (pintype "passive"))
      (node (ref "LED30") (pin "C") (pinfunction "C_C") (pintype "passive"))
      (node (ref "LED301") (pin "C") (pinfunction "C_C") (pintype "passive"))
      (node (ref "LED302") (pin "C") (pinfunction "C_C") (pintype "passive"))
      (node (ref "LED303") (pin "C") (pinfunction "C_C") (pintype "passive"))
      (node (ref "LED304") (pin "C") (pinfunction "C_C") (pintype "passive"))
      (node (ref "LED309") (pin "C") (pinfunction "C_C") (pintype "passive"))
      (node (ref "LED31") (pin "C") (pinfunction "C_C") (pintype "passive"))
      (node (ref "LED310") (pin "C") (pinfunction "C_C") (pintype "passive"))
      (node (ref "LED311") (pin "C") (pinfunction "C_C") (pintype "passive"))
      (node (ref "LED312") (pin "C") (pinfunction "C_C") (pintype "passive"))
      (node (ref "LED317") (pin "C") (pinfunction "C_C") (pintype "passive"))
      (node (ref "LED318") (pin "C") (pinfunction "C_C") (pintype "passive"))
      (node (ref "LED319") (pin "C") (pinfunction "C_C") (pintype "passive"))
      (node (ref "LED32") (pin "C") (pinfunction "C_C") (pintype "passive"))
      (node (ref "LED320") (pin "C") (pinfunction "C_C") (pintype "passive"))
      (node (ref "LED325") (pin "C") (pinfunction "C_C") (pintype "passive"))
      (node (ref "LED326") (pin "C") (pinfunction "C_C") (pintype "passive"))
      (node (ref "LED327") (pin "C") (pinfunction "C_C") (pintype "passive"))
      (node (ref "LED328") (pin "C") (pinfunction "C_C") (pintype "passive"))
      (node (ref "LED33") (pin "C") (pinfunction "C_C") (pintype "passive"))
      (node (ref "LED333") (pin "C") (pinfunction "C_C") (pintype "passive"))
      (node (ref "LED334") (pin "C") (pinfunction "C_C") (pintype "passive"))
      (node (ref "LED335") (pin "C") (pinfunction "C_C") (pintype "passive"))
      (node (ref "LED336") (pin "C") (pinfunction "C_C") (pintype "passive"))
      (node (ref "LED34") (pin "C") (pinfunction "C_C") (pintype "passive"))
      (node (ref "LED341") (pin "C") (pinfunction "C_C") (pintype "passive"))
      (node (ref "LED342") (pin "C") (pinfunction "C_C") (pintype "passive"))
      (node (ref "LED343") (pin "C") (pinfunction "C_C") (pintype "passive"))
      (node (ref "LED344") (pin "C") (pinfunction "C_C") (pintype "passive"))
      (node (ref "LED349") (pin "C") (pinfunction "C_C") (pintype "passive"))
      (node (ref "LED35") (pin "C") (pinfunction "C_C") (pintype "passive"))
      (node (ref "LED350") (pin "C") (pinfunction "C_C") (pintype "passive"))
      (node (ref "LED351") (pin "C") (pinfunction "C_C") (pintype "passive"))
      (node (ref "LED352") (pin "C") (pinfunction "C_C") (pintype "passive"))
      (node (ref "LED357") (pin "C") (pinfunction "C_C") (pintype "passive"))
      (node (ref "LED358") (pin "C") (pinfunction "C_C") (pintype "passive"))
      (node (ref "LED359") (pin "C") (pinfunction "C_C") (pintype "passive"))
      (node (ref "LED36") (pin "C") (pinfunction "C_C") (pintype "passive"))
      (node (ref "LED360") (pin "C") (pinfunction "C_C") (pintype "passive"))
      (node (ref "LED365") (pin "C") (pinfunction "C_C") (pintype "passive"))
      (node (ref "LED366") (pin "C") (pinfunction "C_C") (pintype "passive"))
      (node (ref "LED367") (pin "C") (pinfunction "C_C") (pintype "passive"))
      (node (ref "LED368") (pin "C") (pinfunction "C_C") (pintype "passive"))
      (node (ref "LED37") (pin "C") (pinfunction "C_C") (pintype "passive"))
      (node (ref "LED373") (pin "C") (pinfunction "C_C") (pintype "passive"))
      (node (ref "LED374") (pin "C") (pinfunction "C_C") (pintype "passive"))
      (node (ref "LED375") (pin "C") (pinfunction "C_C") (pintype "passive"))
      (node (ref "LED376") (pin "C") (pinfunction "C_C") (pintype "passive"))
      (node (ref "LED38") (pin "C") (pinfunction "C_C") (pintype "passive"))
      (node (ref "LED381") (pin "C") (pinfunction "C_C") (pintype "passive"))
      (node (ref "LED382") (pin "C") (pinfunction "C_C") (pintype "passive"))
      (node (ref "LED383") (pin "C") (pinfunction "C_C") (pintype "passive"))
      (node (ref "LED384") (pin "C") (pinfunction "C_C") (pintype "passive"))
      (node (ref "LED389") (pin "C") (pinfunction "C_C") (pintype "passive"))
      (node (ref "LED39") (pin "C") (pinfunction "C_C") (pintype "passive"))
      (node (ref "LED390") (pin "C") (pinfunction "C_C") (pintype "passive"))
      (node (ref "LED391") (pin "C") (pinfunction "C_C") (pintype "passive"))
      (node (ref "LED392") (pin "C") (pinfunction "C_C") (pintype "passive"))
      (node (ref "LED397") (pin "C") (pinfunction "C_C") (pintype "passive"))
      (node (ref "LED398") (pin "C") (pinfunction "C_C") (pintype "passive"))
      (node (ref "LED399") (pin "C") (pinfunction "C_C") (pintype "passive"))
      (node (ref "LED40") (pin "C") (pinfunction "C_C") (pintype "passive"))
      (node (ref "LED400") (pin "C") (pinfunction "C_C") (pintype "passive"))
      (node (ref "LED405") (pin "C") (pinfunction "C_C") (pintype "passive"))
      (node (ref "LED406") (pin "C") (pinfunction "C_C") (pintype "passive"))
      (node (ref "LED407") (pin "C") (pinfunction "C_C") (pintype "passive"))
      (node (ref "LED408") (pin "C") (pinfunction "C_C") (pintype "passive"))
      (node (ref "LED413") (pin "C") (pinfunction "C_C") (pintype "passive"))
      (node (ref "LED414") (pin "C") (pinfunction "C_C") (pintype "passive"))
      (node (ref "LED415") (pin "C") (pinfunction "C_C") (pintype "passive"))
      (node (ref "LED416") (pin "C") (pinfunction "C_C") (pintype "passive"))
      (node (ref "LED45") (pin "C") (pinfunction "C_C") (pintype "passive"))
      (node (ref "LED46") (pin "C") (pinfunction "C_C") (pintype "passive"))
      (node (ref "LED47") (pin "C") (pinfunction "C_C") (pintype "passive"))
      (node (ref "LED48") (pin "C") (pinfunction "C_C") (pintype "passive"))
      (node (ref "LED49") (pin "C") (pinfunction "C_C") (pintype "passive"))
      (node (ref "LED5") (pin "C") (pinfunction "C_C") (pintype "passive"))
      (node (ref "LED50") (pin "C") (pinfunction "C_C") (pintype "passive"))
      (node (ref "LED51") (pin "C") (pinfunction "C_C") (pintype "passive"))
      (node (ref "LED52") (pin "C") (pinfunction "C_C") (pintype "passive"))
      (node (ref "LED53") (pin "C") (pinfunction "C_C") (pintype "passive"))
      (node (ref "LED54") (pin "C") (pinfunction "C_C") (pintype "passive"))
      (node (ref "LED55") (pin "C") (pinfunction "C_C") (pintype "passive"))
      (node (ref "LED56") (pin "C") (pinfunction "C_C") (pintype "passive"))
      (node (ref "LED6") (pin "C") (pinfunction "C_C") (pintype "passive"))
      (node (ref "LED61") (pin "C") (pinfunction "C_C") (pintype "passive"))
      (node (ref "LED62") (pin "C") (pinfunction "C_C") (pintype "passive"))
      (node (ref "LED63") (pin "C") (pinfunction "C_C") (pintype "passive"))
      (node (ref "LED64") (pin "C") (pinfunction "C_C") (pintype "passive"))
      (node (ref "LED65") (pin "C") (pinfunction "C_C") (pintype "passive"))
      (node (ref "LED66") (pin "C") (pinfunction "C_C") (pintype "passive"))
      (node (ref "LED67") (pin "C") (pinfunction "C_C") (pintype "passive"))
      (node (ref "LED68") (pin "C") (pinfunction "C_C") (pintype "passive"))
      (node (ref "LED69") (pin "C") (pinfunction "C_C") (pintype "passive"))
      (node (ref "LED7") (pin "C") (pinfunction "C_C") (pintype "passive"))
      (node (ref "LED70") (pin "C") (pinfunction "C_C") (pintype "passive"))
      (node (ref "LED71") (pin "C") (pinfunction "C_C") (pintype "passive"))
      (node (ref "LED72") (pin "C") (pinfunction "C_C") (pintype "passive"))
      (node (ref "LED77") (pin "C") (pinfunction "C_C") (pintype "passive"))
      (node (ref "LED78") (pin "C") (pinfunction "C_C") (pintype "passive"))
      (node (ref "LED79") (pin "C") (pinfunction "C_C") (pintype "passive"))
      (node (ref "LED8") (pin "C") (pinfunction "C_C") (pintype "passive"))
      (node (ref "LED80") (pin "C") (pinfunction "C_C") (pintype "passive"))
      (node (ref "LED85") (pin "C") (pinfunction "C_C") (pintype "passive"))
      (node (ref "LED86") (pin "C") (pinfunction "C_C") (pintype "passive"))
      (node (ref "LED87") (pin "C") (pinfunction "C_C") (pintype "passive"))
      (node (ref "LED88") (pin "C") (pinfunction "C_C") (pintype "passive"))
      (node (ref "LED9") (pin "C") (pinfunction "C_C") (pintype "passive"))
      (node (ref "LED93") (pin "C") (pinfunction "C_C") (pintype "passive"))
      (node (ref "LED94") (pin "C") (pinfunction "C_C") (pintype "passive"))
      (node (ref "LED95") (pin "C") (pinfunction "C_C") (pintype "passive"))
      (node (ref "LED96") (pin "C") (pinfunction "C_C") (pintype "passive"))
      (node (ref "U$1") (pin "P$2") (pinfunction "1_P$2") (pintype "passive"))
      (node (ref "U$2") (pin "P$2") (pinfunction "1_P$2") (pintype "passive"))
    )
    (net (code "2") (name "Net-(LED5-PadA)") (class "Default")
      (node (ref "LED5") (pin "A") (pinfunction "A_A") (pintype "passive"))
      (node (ref "R5") (pin "2") (pinfunction "2_2") (pintype "passive"))
    )
    (net (code "3") (name "Net-(LED6-PadA)") (class "Default")
      (node (ref "LED6") (pin "A") (pinfunction "A_A") (pintype "passive"))
      (node (ref "R6") (pin "2") (pinfunction "2_2") (pintype "passive"))
    )
    (net (code "4") (name "Net-(LED7-PadA)") (class "Default")
      (node (ref "LED7") (pin "A") (pinfunction "A_A") (pintype "passive"))
      (node (ref "R7") (pin "2") (pinfunction "2_2") (pintype "passive"))
    )
    (net (code "5") (name "Net-(LED8-PadA)") (class "Default")
      (node (ref "LED8") (pin "A") (pinfunction "A_A") (pintype "passive"))
      (node (ref "R8") (pin "2") (pinfunction "2_2") (pintype "passive"))
    )
    (net (code "6") (name "Net-(LED9-PadA)") (class "Default")
      (node (ref "LED9") (pin "A") (pinfunction "A_A") (pintype "passive"))
      (node (ref "R9") (pin "2") (pinfunction "2_2") (pintype "passive"))
    )
    (net (code "7") (name "Net-(LED10-PadA)") (class "Default")
      (node (ref "LED10") (pin "A") (pinfunction "A_A") (pintype "passive"))
      (node (ref "R10") (pin "2") (pinfunction "2_2") (pintype "passive"))
    )
    (net (code "8") (name "Net-(LED11-PadA)") (class "Default")
      (node (ref "LED11") (pin "A") (pinfunction "A_A") (pintype "passive"))
      (node (ref "R11") (pin "2") (pinfunction "2_2") (pintype "passive"))
    )
    (net (code "9") (name "Net-(LED12-PadA)") (class "Default")
      (node (ref "LED12") (pin "A") (pinfunction "A_A") (pintype "passive"))
      (node (ref "R12") (pin "2") (pinfunction "2_2") (pintype "passive"))
    )
    (net (code "10") (name "Net-(LED13-PadA)") (class "Default")
      (node (ref "LED13") (pin "A") (pinfunction "A_A") (pintype "passive"))
      (node (ref "R13") (pin "2") (pinfunction "2_2") (pintype "passive"))
    )
    (net (code "11") (name "Net-(LED14-PadA)") (class "Default")
      (node (ref "LED14") (pin "A") (pinfunction "A_A") (pintype "passive"))
      (node (ref "R14") (pin "2") (pinfunction "2_2") (pintype "passive"))
    )
    (net (code "12") (name "Net-(LED15-PadA)") (class "Default")
      (node (ref "LED15") (pin "A") (pinfunction "A_A") (pintype "passive"))
      (node (ref "R15") (pin "2") (pinfunction "2_2") (pintype "passive"))
    )
    (net (code "13") (name "Net-(LED16-PadA)") (class "Default")
      (node (ref "LED16") (pin "A") (pinfunction "A_A") (pintype "passive"))
      (node (ref "R16") (pin "2") (pinfunction "2_2") (pintype "passive"))
    )
    (net (code "14") (name "Net-(LED17-PadA)") (class "Default")
      (node (ref "LED17") (pin "A") (pinfunction "A_A") (pintype "passive"))
      (node (ref "R17") (pin "2") (pinfunction "2_2") (pintype "passive"))
    )
    (net (code "15") (name "Net-(LED18-PadA)") (class "Default")
      (node (ref "LED18") (pin "A") (pinfunction "A_A") (pintype "passive"))
      (node (ref "R18") (pin "2") (pinfunction "2_2") (pintype "passive"))
    )
    (net (code "16") (name "Net-(LED19-PadA)") (class "Default")
      (node (ref "LED19") (pin "A") (pinfunction "A_A") (pintype "passive"))
      (node (ref "R19") (pin "2") (pinfunction "2_2") (pintype "passive"))
    )
    (net (code "17") (name "Net-(LED20-PadA)") (class "Default")
      (node (ref "LED20") (pin "A") (pinfunction "A_A") (pintype "passive"))
      (node (ref "R20") (pin "2") (pinfunction "2_2") (pintype "passive"))
    )
    (net (code "18") (name "Net-(LED21-PadA)") (class "Default")
      (node (ref "LED21") (pin "A") (pinfunction "A_A") (pintype "passive"))
      (node (ref "R21") (pin "2") (pinfunction "2_2") (pintype "passive"))
    )
    (net (code "19") (name "Net-(LED22-PadA)") (class "Default")
      (node (ref "LED22") (pin "A") (pinfunction "A_A") (pintype "passive"))
      (node (ref "R22") (pin "2") (pinfunction "2_2") (pintype "passive"))
    )
    (net (code "20") (name "Net-(LED23-PadA)") (class "Default")
      (node (ref "LED23") (pin "A") (pinfunction "A_A") (pintype "passive"))
      (node (ref "R23") (pin "2") (pinfunction "2_2") (pintype "passive"))
    )
    (net (code "21") (name "Net-(LED24-PadA)") (class "Default")
      (node (ref "LED24") (pin "A") (pinfunction "A_A") (pintype "passive"))
      (node (ref "R24") (pin "2") (pinfunction "2_2") (pintype "passive"))
    )
    (net (code "22") (name "Net-(LED25-PadA)") (class "Default")
      (node (ref "LED25") (pin "A") (pinfunction "A_A") (pintype "passive"))
      (node (ref "R25") (pin "2") (pinfunction "2_2") (pintype "passive"))
    )
    (net (code "23") (name "Net-(LED26-PadA)") (class "Default")
      (node (ref "LED26") (pin "A") (pinfunction "A_A") (pintype "passive"))
      (node (ref "R26") (pin "2") (pinfunction "2_2") (pintype "passive"))
    )
    (net (code "24") (name "Net-(LED27-PadA)") (class "Default")
      (node (ref "LED27") (pin "A") (pinfunction "A_A") (pintype "passive"))
      (node (ref "R27") (pin "2") (pinfunction "2_2") (pintype "passive"))
    )
    (net (code "25") (name "Net-(LED28-PadA)") (class "Default")
      (node (ref "LED28") (pin "A") (pinfunction "A_A") (pintype "passive"))
      (node (ref "R28") (pin "2") (pinfunction "2_2") (pintype "passive"))
    )
    (net (code "26") (name "Net-(LED29-PadA)") (class "Default")
      (node (ref "LED29") (pin "A") (pinfunction "A_A") (pintype "passive"))
      (node (ref "R29") (pin "2") (pinfunction "2_2") (pintype "passive"))
    )
    (net (code "27") (name "Net-(LED30-PadA)") (class "Default")
      (node (ref "LED30") (pin "A") (pinfunction "A_A") (pintype "passive"))
      (node (ref "R30") (pin "2") (pinfunction "2_2") (pintype "passive"))
    )
    (net (code "28") (name "Net-(LED31-PadA)") (class "Default")
      (node (ref "LED31") (pin "A") (pinfunction "A_A") (pintype "passive"))
      (node (ref "R31") (pin "2") (pinfunction "2_2") (pintype "passive"))
    )
    (net (code "29") (name "Net-(LED32-PadA)") (class "Default")
      (node (ref "LED32") (pin "A") (pinfunction "A_A") (pintype "passive"))
      (node (ref "R32") (pin "2") (pinfunction "2_2") (pintype "passive"))
    )
    (net (code "30") (name "Net-(LED33-PadA)") (class "Default")
      (node (ref "LED33") (pin "A") (pinfunction "A_A") (pintype "passive"))
      (node (ref "R33") (pin "2") (pinfunction "2_2") (pintype "passive"))
    )
    (net (code "31") (name "Net-(LED34-PadA)") (class "Default")
      (node (ref "LED34") (pin "A") (pinfunction "A_A") (pintype "passive"))
      (node (ref "R34") (pin "2") (pinfunction "2_2") (pintype "passive"))
    )
    (net (code "32") (name "Net-(LED35-PadA)") (class "Default")
      (node (ref "LED35") (pin "A") (pinfunction "A_A") (pintype "passive"))
      (node (ref "R35") (pin "2") (pinfunction "2_2") (pintype "passive"))
    )
    (net (code "33") (name "Net-(LED36-PadA)") (class "Default")
      (node (ref "LED36") (pin "A") (pinfunction "A_A") (pintype "passive"))
      (node (ref "R36") (pin "2") (pinfunction "2_2") (pintype "passive"))
    )
    (net (code "34") (name "Net-(LED37-PadA)") (class "Default")
      (node (ref "LED37") (pin "A") (pinfunction "A_A") (pintype "passive"))
      (node (ref "R37") (pin "2") (pinfunction "2_2") (pintype "passive"))
    )
    (net (code "35") (name "Net-(LED38-PadA)") (class "Default")
      (node (ref "LED38") (pin "A") (pinfunction "A_A") (pintype "passive"))
      (node (ref "R38") (pin "2") (pinfunction "2_2") (pintype "passive"))
    )
    (net (code "36") (name "Net-(LED39-PadA)") (class "Default")
      (node (ref "LED39") (pin "A") (pinfunction "A_A") (pintype "passive"))
      (node (ref "R39") (pin "2") (pinfunction "2_2") (pintype "passive"))
    )
    (net (code "37") (name "Net-(LED40-PadA)") (class "Default")
      (node (ref "LED40") (pin "A") (pinfunction "A_A") (pintype "passive"))
      (node (ref "R40") (pin "2") (pinfunction "2_2") (pintype "passive"))
    )
    (net (code "38") (name "Net-(LED45-PadA)") (class "Default")
      (node (ref "LED45") (pin "A") (pinfunction "A_A") (pintype "passive"))
      (node (ref "R45") (pin "2") (pinfunction "2_2") (pintype "passive"))
    )
    (net (code "39") (name "Net-(LED46-PadA)") (class "Default")
      (node (ref "LED46") (pin "A") (pinfunction "A_A") (pintype "passive"))
      (node (ref "R46") (pin "2") (pinfunction "2_2") (pintype "passive"))
    )
    (net (code "40") (name "Net-(LED47-PadA)") (class "Default")
      (node (ref "LED47") (pin "A") (pinfunction "A_A") (pintype "passive"))
      (node (ref "R47") (pin "2") (pinfunction "2_2") (pintype "passive"))
    )
    (net (code "41") (name "Net-(LED48-PadA)") (class "Default")
      (node (ref "LED48") (pin "A") (pinfunction "A_A") (pintype "passive"))
      (node (ref "R48") (pin "2") (pinfunction "2_2") (pintype "passive"))
    )
    (net (code "42") (name "Net-(LED49-PadA)") (class "Default")
      (node (ref "LED49") (pin "A") (pinfunction "A_A") (pintype "passive"))
      (node (ref "R49") (pin "2") (pinfunction "2_2") (pintype "passive"))
    )
    (net (code "43") (name "Net-(LED50-PadA)") (class "Default")
      (node (ref "LED50") (pin "A") (pinfunction "A_A") (pintype "passive"))
      (node (ref "R50") (pin "2") (pinfunction "2_2") (pintype "passive"))
    )
    (net (code "44") (name "Net-(LED51-PadA)") (class "Default")
      (node (ref "LED51") (pin "A") (pinfunction "A_A") (pintype "passive"))
      (node (ref "R51") (pin "2") (pinfunction "2_2") (pintype "passive"))
    )
    (net (code "45") (name "Net-(LED52-PadA)") (class "Default")
      (node (ref "LED52") (pin "A") (pinfunction "A_A") (pintype "passive"))
      (node (ref "R52") (pin "2") (pinfunction "2_2") (pintype "passive"))
    )
    (net (code "46") (name "Net-(LED53-PadA)") (class "Default")
      (node (ref "LED53") (pin "A") (pinfunction "A_A") (pintype "passive"))
      (node (ref "R53") (pin "2") (pinfunction "2_2") (pintype "passive"))
    )
    (net (code "47") (name "Net-(LED54-PadA)") (class "Default")
      (node (ref "LED54") (pin "A") (pinfunction "A_A") (pintype "passive"))
      (node (ref "R54") (pin "2") (pinfunction "2_2") (pintype "passive"))
    )
    (net (code "48") (name "Net-(LED55-PadA)") (class "Default")
      (node (ref "LED55") (pin "A") (pinfunction "A_A") (pintype "passive"))
      (node (ref "R55") (pin "2") (pinfunction "2_2") (pintype "passive"))
    )
    (net (code "49") (name "Net-(LED56-PadA)") (class "Default")
      (node (ref "LED56") (pin "A") (pinfunction "A_A") (pintype "passive"))
      (node (ref "R56") (pin "2") (pinfunction "2_2") (pintype "passive"))
    )
    (net (code "50") (name "Net-(LED61-PadA)") (class "Default")
      (node (ref "LED61") (pin "A") (pinfunction "A_A") (pintype "passive"))
      (node (ref "R61") (pin "2") (pinfunction "2_2") (pintype "passive"))
    )
    (net (code "51") (name "Net-(LED62-PadA)") (class "Default")
      (node (ref "LED62") (pin "A") (pinfunction "A_A") (pintype "passive"))
      (node (ref "R62") (pin "2") (pinfunction "2_2") (pintype "passive"))
    )
    (net (code "52") (name "Net-(LED63-PadA)") (class "Default")
      (node (ref "LED63") (pin "A") (pinfunction "A_A") (pintype "passive"))
      (node (ref "R63") (pin "2") (pinfunction "2_2") (pintype "passive"))
    )
    (net (code "53") (name "Net-(LED64-PadA)") (class "Default")
      (node (ref "LED64") (pin "A") (pinfunction "A_A") (pintype "passive"))
      (node (ref "R64") (pin "2") (pinfunction "2_2") (pintype "passive"))
    )
    (net (code "54") (name "Net-(LED65-PadA)") (class "Default")
      (node (ref "LED65") (pin "A") (pinfunction "A_A") (pintype "passive"))
      (node (ref "R65") (pin "2") (pinfunction "2_2") (pintype "passive"))
    )
    (net (code "55") (name "Net-(LED66-PadA)") (class "Default")
      (node (ref "LED66") (pin "A") (pinfunction "A_A") (pintype "passive"))
      (node (ref "R66") (pin "2") (pinfunction "2_2") (pintype "passive"))
    )
    (net (code "56") (name "Net-(LED67-PadA)") (class "Default")
      (node (ref "LED67") (pin "A") (pinfunction "A_A") (pintype "passive"))
      (node (ref "R67") (pin "2") (pinfunction "2_2") (pintype "passive"))
    )
    (net (code "57") (name "Net-(LED68-PadA)") (class "Default")
      (node (ref "LED68") (pin "A") (pinfunction "A_A") (pintype "passive"))
      (node (ref "R68") (pin "2") (pinfunction "2_2") (pintype "passive"))
    )
    (net (code "58") (name "Net-(LED69-PadA)") (class "Default")
      (node (ref "LED69") (pin "A") (pinfunction "A_A") (pintype "passive"))
      (node (ref "R69") (pin "2") (pinfunction "2_2") (pintype "passive"))
    )
    (net (code "59") (name "Net-(LED70-PadA)") (class "Default")
      (node (ref "LED70") (pin "A") (pinfunction "A_A") (pintype "passive"))
      (node (ref "R70") (pin "2") (pinfunction "2_2") (pintype "passive"))
    )
    (net (code "60") (name "Net-(LED71-PadA)") (class "Default")
      (node (ref "LED71") (pin "A") (pinfunction "A_A") (pintype "passive"))
      (node (ref "R71") (pin "2") (pinfunction "2_2") (pintype "passive"))
    )
    (net (code "61") (name "Net-(LED72-PadA)") (class "Default")
      (node (ref "LED72") (pin "A") (pinfunction "A_A") (pintype "passive"))
      (node (ref "R72") (pin "2") (pinfunction "2_2") (pintype "passive"))
    )
    (net (code "62") (name "Net-(LED77-PadA)") (class "Default")
      (node (ref "LED77") (pin "A") (pinfunction "A_A") (pintype "passive"))
      (node (ref "R77") (pin "2") (pinfunction "2_2") (pintype "passive"))
    )
    (net (code "63") (name "Net-(LED78-PadA)") (class "Default")
      (node (ref "LED78") (pin "A") (pinfunction "A_A") (pintype "passive"))
      (node (ref "R78") (pin "2") (pinfunction "2_2") (pintype "passive"))
    )
    (net (code "64") (name "Net-(LED79-PadA)") (class "Default")
      (node (ref "LED79") (pin "A") (pinfunction "A_A") (pintype "passive"))
      (node (ref "R79") (pin "2") (pinfunction "2_2") (pintype "passive"))
    )
    (net (code "65") (name "Net-(LED80-PadA)") (class "Default")
      (node (ref "LED80") (pin "A") (pinfunction "A_A") (pintype "passive"))
      (node (ref "R80") (pin "2") (pinfunction "2_2") (pintype "passive"))
    )
    (net (code "66") (name "Net-(LED85-PadA)") (class "Default")
      (node (ref "LED85") (pin "A") (pinfunction "A_A") (pintype "passive"))
      (node (ref "R85") (pin "2") (pinfunction "2_2") (pintype "passive"))
    )
    (net (code "67") (name "Net-(LED86-PadA)") (class "Default")
      (node (ref "LED86") (pin "A") (pinfunction "A_A") (pintype "passive"))
      (node (ref "R86") (pin "2") (pinfunction "2_2") (pintype "passive"))
    )
    (net (code "68") (name "Net-(LED87-PadA)") (class "Default")
      (node (ref "LED87") (pin "A") (pinfunction "A_A") (pintype "passive"))
      (node (ref "R87") (pin "2") (pinfunction "2_2") (pintype "passive"))
    )
    (net (code "69") (name "Net-(LED88-PadA)") (class "Default")
      (node (ref "LED88") (pin "A") (pinfunction "A_A") (pintype "passive"))
      (node (ref "R88") (pin "2") (pinfunction "2_2") (pintype "passive"))
    )
    (net (code "70") (name "Net-(LED93-PadA)") (class "Default")
      (node (ref "LED93") (pin "A") (pinfunction "A_A") (pintype "passive"))
      (node (ref "R93") (pin "2") (pinfunction "2_2") (pintype "passive"))
    )
    (net (code "71") (name "Net-(LED94-PadA)") (class "Default")
      (node (ref "LED94") (pin "A") (pinfunction "A_A") (pintype "passive"))
      (node (ref "R94") (pin "2") (pinfunction "2_2") (pintype "passive"))
    )
    (net (code "72") (name "Net-(LED95-PadA)") (class "Default")
      (node (ref "LED95") (pin "A") (pinfunction "A_A") (pintype "passive"))
      (node (ref "R95") (pin "2") (pinfunction "2_2") (pintype "passive"))
    )
    (net (code "73") (name "Net-(LED96-PadA)") (class "Default")
      (node (ref "LED96") (pin "A") (pinfunction "A_A") (pintype "passive"))
      (node (ref "R96") (pin "2") (pinfunction "2_2") (pintype "passive"))
    )
    (net (code "74") (name "Net-(LED101-PadA)") (class "Default")
      (node (ref "LED101") (pin "A") (pinfunction "A_A") (pintype "passive"))
      (node (ref "R101") (pin "2") (pinfunction "2_2") (pintype "passive"))
    )
    (net (code "75") (name "Net-(LED102-PadA)") (class "Default")
      (node (ref "LED102") (pin "A") (pinfunction "A_A") (pintype "passive"))
      (node (ref "R102") (pin "2") (pinfunction "2_2") (pintype "passive"))
    )
    (net (code "76") (name "Net-(LED103-PadA)") (class "Default")
      (node (ref "LED103") (pin "A") (pinfunction "A_A") (pintype "passive"))
      (node (ref "R103") (pin "2") (pinfunction "2_2") (pintype "passive"))
    )
    (net (code "77") (name "Net-(LED104-PadA)") (class "Default")
      (node (ref "LED104") (pin "A") (pinfunction "A_A") (pintype "passive"))
      (node (ref "R104") (pin "2") (pinfunction "2_2") (pintype "passive"))
    )
    (net (code "78") (name "Net-(LED109-PadA)") (class "Default")
      (node (ref "LED109") (pin "A") (pinfunction "A_A") (pintype "passive"))
      (node (ref "R109") (pin "2") (pinfunction "2_2") (pintype "passive"))
    )
    (net (code "79") (name "Net-(LED110-PadA)") (class "Default")
      (node (ref "LED110") (pin "A") (pinfunction "A_A") (pintype "passive"))
      (node (ref "R110") (pin "2") (pinfunction "2_2") (pintype "passive"))
    )
    (net (code "80") (name "Net-(LED111-PadA)") (class "Default")
      (node (ref "LED111") (pin "A") (pinfunction "A_A") (pintype "passive"))
      (node (ref "R111") (pin "2") (pinfunction "2_2") (pintype "passive"))
    )
    (net (code "81") (name "Net-(LED112-PadA)") (class "Default")
      (node (ref "LED112") (pin "A") (pinfunction "A_A") (pintype "passive"))
      (node (ref "R112") (pin "2") (pinfunction "2_2") (pintype "passive"))
    )
    (net (code "82") (name "Net-(LED117-PadA)") (class "Default")
      (node (ref "LED117") (pin "A") (pinfunction "A_A") (pintype "passive"))
      (node (ref "R117") (pin "2") (pinfunction "2_2") (pintype "passive"))
    )
    (net (code "83") (name "Net-(LED118-PadA)") (class "Default")
      (node (ref "LED118") (pin "A") (pinfunction "A_A") (pintype "passive"))
      (node (ref "R118") (pin "2") (pinfunction "2_2") (pintype "passive"))
    )
    (net (code "84") (name "Net-(LED119-PadA)") (class "Default")
      (node (ref "LED119") (pin "A") (pinfunction "A_A") (pintype "passive"))
      (node (ref "R119") (pin "2") (pinfunction "2_2") (pintype "passive"))
    )
    (net (code "85") (name "Net-(LED120-PadA)") (class "Default")
      (node (ref "LED120") (pin "A") (pinfunction "A_A") (pintype "passive"))
      (node (ref "R120") (pin "2") (pinfunction "2_2") (pintype "passive"))
    )
    (net (code "86") (name "Net-(LED125-PadA)") (class "Default")
      (node (ref "LED125") (pin "A") (pinfunction "A_A") (pintype "passive"))
      (node (ref "R125") (pin "2") (pinfunction "2_2") (pintype "passive"))
    )
    (net (code "87") (name "Net-(LED126-PadA)") (class "Default")
      (node (ref "LED126") (pin "A") (pinfunction "A_A") (pintype "passive"))
      (node (ref "R126") (pin "2") (pinfunction "2_2") (pintype "passive"))
    )
    (net (code "88") (name "Net-(LED127-PadA)") (class "Default")
      (node (ref "LED127") (pin "A") (pinfunction "A_A") (pintype "passive"))
      (node (ref "R127") (pin "2") (pinfunction "2_2") (pintype "passive"))
    )
    (net (code "89") (name "Net-(LED128-PadA)") (class "Default")
      (node (ref "LED128") (pin "A") (pinfunction "A_A") (pintype "passive"))
      (node (ref "R128") (pin "2") (pinfunction "2_2") (pintype "passive"))
    )
    (net (code "90") (name "Net-(LED133-PadA)") (class "Default")
      (node (ref "LED133") (pin "A") (pinfunction "A_A") (pintype "passive"))
      (node (ref "R133") (pin "2") (pinfunction "2_2") (pintype "passive"))
    )
    (net (code "91") (name "Net-(LED134-PadA)") (class "Default")
      (node (ref "LED134") (pin "A") (pinfunction "A_A") (pintype "passive"))
      (node (ref "R134") (pin "2") (pinfunction "2_2") (pintype "passive"))
    )
    (net (code "92") (name "Net-(LED135-PadA)") (class "Default")
      (node (ref "LED135") (pin "A") (pinfunction "A_A") (pintype "passive"))
      (node (ref "R135") (pin "2") (pinfunction "2_2") (pintype "passive"))
    )
    (net (code "93") (name "Net-(LED136-PadA)") (class "Default")
      (node (ref "LED136") (pin "A") (pinfunction "A_A") (pintype "passive"))
      (node (ref "R136") (pin "2") (pinfunction "2_2") (pintype "passive"))
    )
    (net (code "94") (name "Net-(LED141-PadA)") (class "Default")
      (node (ref "LED141") (pin "A") (pinfunction "A_A") (pintype "passive"))
      (node (ref "R141") (pin "2") (pinfunction "2_2") (pintype "passive"))
    )
    (net (code "95") (name "Net-(LED142-PadA)") (class "Default")
      (node (ref "LED142") (pin "A") (pinfunction "A_A") (pintype "passive"))
      (node (ref "R142") (pin "2") (pinfunction "2_2") (pintype "passive"))
    )
    (net (code "96") (name "Net-(LED143-PadA)") (class "Default")
      (node (ref "LED143") (pin "A") (pinfunction "A_A") (pintype "passive"))
      (node (ref "R143") (pin "2") (pinfunction "2_2") (pintype "passive"))
    )
    (net (code "97") (name "Net-(LED144-PadA)") (class "Default")
      (node (ref "LED144") (pin "A") (pinfunction "A_A") (pintype "passive"))
      (node (ref "R144") (pin "2") (pinfunction "2_2") (pintype "passive"))
    )
    (net (code "98") (name "Net-(LED149-PadA)") (class "Default")
      (node (ref "LED149") (pin "A") (pinfunction "A_A") (pintype "passive"))
      (node (ref "R149") (pin "2") (pinfunction "2_2") (pintype "passive"))
    )
    (net (code "99") (name "Net-(LED150-PadA)") (class "Default")
      (node (ref "LED150") (pin "A") (pinfunction "A_A") (pintype "passive"))
      (node (ref "R150") (pin "2") (pinfunction "2_2") (pintype "passive"))
    )
    (net (code "100") (name "Net-(LED151-PadA)") (class "Default")
      (node (ref "LED151") (pin "A") (pinfunction "A_A") (pintype "passive"))
      (node (ref "R151") (pin "2") (pinfunction "2_2") (pintype "passive"))
    )
    (net (code "101") (name "Net-(LED152-PadA)") (class "Default")
      (node (ref "LED152") (pin "A") (pinfunction "A_A") (pintype "passive"))
      (node (ref "R152") (pin "2") (pinfunction "2_2") (pintype "passive"))
    )
    (net (code "102") (name "Net-(LED157-PadA)") (class "Default")
      (node (ref "LED157") (pin "A") (pinfunction "A_A") (pintype "passive"))
      (node (ref "R157") (pin "2") (pinfunction "2_2") (pintype "passive"))
    )
    (net (code "103") (name "Net-(LED158-PadA)") (class "Default")
      (node (ref "LED158") (pin "A") (pinfunction "A_A") (pintype "passive"))
      (node (ref "R158") (pin "2") (pinfunction "2_2") (pintype "passive"))
    )
    (net (code "104") (name "Net-(LED159-PadA)") (class "Default")
      (node (ref "LED159") (pin "A") (pinfunction "A_A") (pintype "passive"))
      (node (ref "R159") (pin "2") (pinfunction "2_2") (pintype "passive"))
    )
    (net (code "105") (name "Net-(LED160-PadA)") (class "Default")
      (node (ref "LED160") (pin "A") (pinfunction "A_A") (pintype "passive"))
      (node (ref "R160") (pin "2") (pinfunction "2_2") (pintype "passive"))
    )
    (net (code "106") (name "Net-(LED165-PadA)") (class "Default")
      (node (ref "LED165") (pin "A") (pinfunction "A_A") (pintype "passive"))
      (node (ref "R165") (pin "2") (pinfunction "2_2") (pintype "passive"))
    )
    (net (code "107") (name "Net-(LED166-PadA)") (class "Default")
      (node (ref "LED166") (pin "A") (pinfunction "A_A") (pintype "passive"))
      (node (ref "R166") (pin "2") (pinfunction "2_2") (pintype "passive"))
    )
    (net (code "108") (name "Net-(LED167-PadA)") (class "Default")
      (node (ref "LED167") (pin "A") (pinfunction "A_A") (pintype "passive"))
      (node (ref "R167") (pin "2") (pinfunction "2_2") (pintype "passive"))
    )
    (net (code "109") (name "Net-(LED168-PadA)") (class "Default")
      (node (ref "LED168") (pin "A") (pinfunction "A_A") (pintype "passive"))
      (node (ref "R168") (pin "2") (pinfunction "2_2") (pintype "passive"))
    )
    (net (code "110") (name "Net-(LED173-PadA)") (class "Default")
      (node (ref "LED173") (pin "A") (pinfunction "A_A") (pintype "passive"))
      (node (ref "R173") (pin "2") (pinfunction "2_2") (pintype "passive"))
    )
    (net (code "111") (name "Net-(LED174-PadA)") (class "Default")
      (node (ref "LED174") (pin "A") (pinfunction "A_A") (pintype "passive"))
      (node (ref "R174") (pin "2") (pinfunction "2_2") (pintype "passive"))
    )
    (net (code "112") (name "Net-(LED175-PadA)") (class "Default")
      (node (ref "LED175") (pin "A") (pinfunction "A_A") (pintype "passive"))
      (node (ref "R175") (pin "2") (pinfunction "2_2") (pintype "passive"))
    )
    (net (code "113") (name "Net-(LED176-PadA)") (class "Default")
      (node (ref "LED176") (pin "A") (pinfunction "A_A") (pintype "passive"))
      (node (ref "R176") (pin "2") (pinfunction "2_2") (pintype "passive"))
    )
    (net (code "114") (name "Net-(LED181-PadA)") (class "Default")
      (node (ref "LED181") (pin "A") (pinfunction "A_A") (pintype "passive"))
      (node (ref "R181") (pin "2") (pinfunction "2_2") (pintype "passive"))
    )
    (net (code "115") (name "Net-(LED182-PadA)") (class "Default")
      (node (ref "LED182") (pin "A") (pinfunction "A_A") (pintype "passive"))
      (node (ref "R182") (pin "2") (pinfunction "2_2") (pintype "passive"))
    )
    (net (code "116") (name "Net-(LED183-PadA)") (class "Default")
      (node (ref "LED183") (pin "A") (pinfunction "A_A") (pintype "passive"))
      (node (ref "R183") (pin "2") (pinfunction "2_2") (pintype "passive"))
    )
    (net (code "117") (name "Net-(LED184-PadA)") (class "Default")
      (node (ref "LED184") (pin "A") (pinfunction "A_A") (pintype "passive"))
      (node (ref "R184") (pin "2") (pinfunction "2_2") (pintype "passive"))
    )
    (net (code "118") (name "Net-(LED189-PadA)") (class "Default")
      (node (ref "LED189") (pin "A") (pinfunction "A_A") (pintype "passive"))
      (node (ref "R189") (pin "2") (pinfunction "2_2") (pintype "passive"))
    )
    (net (code "119") (name "Net-(LED190-PadA)") (class "Default")
      (node (ref "LED190") (pin "A") (pinfunction "A_A") (pintype "passive"))
      (node (ref "R190") (pin "2") (pinfunction "2_2") (pintype "passive"))
    )
    (net (code "120") (name "Net-(LED191-PadA)") (class "Default")
      (node (ref "LED191") (pin "A") (pinfunction "A_A") (pintype "passive"))
      (node (ref "R191") (pin "2") (pinfunction "2_2") (pintype "passive"))
    )
    (net (code "121") (name "Net-(LED192-PadA)") (class "Default")
      (node (ref "LED192") (pin "A") (pinfunction "A_A") (pintype "passive"))
      (node (ref "R192") (pin "2") (pinfunction "2_2") (pintype "passive"))
    )
    (net (code "122") (name "Net-(LED197-PadA)") (class "Default")
      (node (ref "LED197") (pin "A") (pinfunction "A_A") (pintype "passive"))
      (node (ref "R197") (pin "2") (pinfunction "2_2") (pintype "passive"))
    )
    (net (code "123") (name "Net-(LED198-PadA)") (class "Default")
      (node (ref "LED198") (pin "A") (pinfunction "A_A") (pintype "passive"))
      (node (ref "R198") (pin "2") (pinfunction "2_2") (pintype "passive"))
    )
    (net (code "124") (name "Net-(LED199-PadA)") (class "Default")
      (node (ref "LED199") (pin "A") (pinfunction "A_A") (pintype "passive"))
      (node (ref "R199") (pin "2") (pinfunction "2_2") (pintype "passive"))
    )
    (net (code "125") (name "Net-(LED200-PadA)") (class "Default")
      (node (ref "LED200") (pin "A") (pinfunction "A_A") (pintype "passive"))
      (node (ref "R200") (pin "2") (pinfunction "2_2") (pintype "passive"))
    )
    (net (code "126") (name "Net-(LED205-PadA)") (class "Default")
      (node (ref "LED205") (pin "A") (pinfunction "A_A") (pintype "passive"))
      (node (ref "R205") (pin "2") (pinfunction "2_2") (pintype "passive"))
    )
    (net (code "127") (name "Net-(LED206-PadA)") (class "Default")
      (node (ref "LED206") (pin "A") (pinfunction "A_A") (pintype "passive"))
      (node (ref "R206") (pin "2") (pinfunction "2_2") (pintype "passive"))
    )
    (net (code "128") (name "Net-(LED207-PadA)") (class "Default")
      (node (ref "LED207") (pin "A") (pinfunction "A_A") (pintype "passive"))
      (node (ref "R207") (pin "2") (pinfunction "2_2") (pintype "passive"))
    )
    (net (code "129") (name "Net-(LED208-PadA)") (class "Default")
      (node (ref "LED208") (pin "A") (pinfunction "A_A") (pintype "passive"))
      (node (ref "R208") (pin "2") (pinfunction "2_2") (pintype "passive"))
    )
    (net (code "130") (name "Net-(LED213-PadA)") (class "Default")
      (node (ref "LED213") (pin "A") (pinfunction "A_A") (pintype "passive"))
      (node (ref "R213") (pin "2") (pinfunction "2_2") (pintype "passive"))
    )
    (net (code "131") (name "Net-(LED214-PadA)") (class "Default")
      (node (ref "LED214") (pin "A") (pinfunction "A_A") (pintype "passive"))
      (node (ref "R214") (pin "2") (pinfunction "2_2") (pintype "passive"))
    )
    (net (code "132") (name "Net-(LED215-PadA)") (class "Default")
      (node (ref "LED215") (pin "A") (pinfunction "A_A") (pintype "passive"))
      (node (ref "R215") (pin "2") (pinfunction "2_2") (pintype "passive"))
    )
    (net (code "133") (name "Net-(LED216-PadA)") (class "Default")
      (node (ref "LED216") (pin "A") (pinfunction "A_A") (pintype "passive"))
      (node (ref "R216") (pin "2") (pinfunction "2_2") (pintype "passive"))
    )
    (net (code "134") (name "Net-(LED221-PadA)") (class "Default")
      (node (ref "LED221") (pin "A") (pinfunction "A_A") (pintype "passive"))
      (node (ref "R221") (pin "2") (pinfunction "2_2") (pintype "passive"))
    )
    (net (code "135") (name "Net-(LED222-PadA)") (class "Default")
      (node (ref "LED222") (pin "A") (pinfunction "A_A") (pintype "passive"))
      (node (ref "R222") (pin "2") (pinfunction "2_2") (pintype "passive"))
    )
    (net (code "136") (name "Net-(LED223-PadA)") (class "Default")
      (node (ref "LED223") (pin "A") (pinfunction "A_A") (pintype "passive"))
      (node (ref "R223") (pin "2") (pinfunction "2_2") (pintype "passive"))
    )
    (net (code "137") (name "Net-(LED224-PadA)") (class "Default")
      (node (ref "LED224") (pin "A") (pinfunction "A_A") (pintype "passive"))
      (node (ref "R224") (pin "2") (pinfunction "2_2") (pintype "passive"))
    )
    (net (code "138") (name "Net-(LED229-PadA)") (class "Default")
      (node (ref "LED229") (pin "A") (pinfunction "A_A") (pintype "passive"))
      (node (ref "R229") (pin "2") (pinfunction "2_2") (pintype "passive"))
    )
    (net (code "139") (name "Net-(LED230-PadA)") (class "Default")
      (node (ref "LED230") (pin "A") (pinfunction "A_A") (pintype "passive"))
      (node (ref "R230") (pin "2") (pinfunction "2_2") (pintype "passive"))
    )
    (net (code "140") (name "Net-(LED231-PadA)") (class "Default")
      (node (ref "LED231") (pin "A") (pinfunction "A_A") (pintype "passive"))
      (node (ref "R231") (pin "2") (pinfunction "2_2") (pintype "passive"))
    )
    (net (code "141") (name "Net-(LED232-PadA)") (class "Default")
      (node (ref "LED232") (pin "A") (pinfunction "A_A") (pintype "passive"))
      (node (ref "R232") (pin "2") (pinfunction "2_2") (pintype "passive"))
    )
    (net (code "142") (name "Net-(LED237-PadA)") (class "Default")
      (node (ref "LED237") (pin "A") (pinfunction "A_A") (pintype "passive"))
      (node (ref "R237") (pin "2") (pinfunction "2_2") (pintype "passive"))
    )
    (net (code "143") (name "Net-(LED238-PadA)") (class "Default")
      (node (ref "LED238") (pin "A") (pinfunction "A_A") (pintype "passive"))
      (node (ref "R238") (pin "2") (pinfunction "2_2") (pintype "passive"))
    )
    (net (code "144") (name "Net-(LED239-PadA)") (class "Default")
      (node (ref "LED239") (pin "A") (pinfunction "A_A") (pintype "passive"))
      (node (ref "R239") (pin "2") (pinfunction "2_2") (pintype "passive"))
    )
    (net (code "145") (name "Net-(LED240-PadA)") (class "Default")
      (node (ref "LED240") (pin "A") (pinfunction "A_A") (pintype "passive"))
      (node (ref "R240") (pin "2") (pinfunction "2_2") (pintype "passive"))
    )
    (net (code "146") (name "Net-(LED245-PadA)") (class "Default")
      (node (ref "LED245") (pin "A") (pinfunction "A_A") (pintype "passive"))
      (node (ref "R245") (pin "2") (pinfunction "2_2") (pintype "passive"))
    )
    (net (code "147") (name "Net-(LED246-PadA)") (class "Default")
      (node (ref "LED246") (pin "A") (pinfunction "A_A") (pintype "passive"))
      (node (ref "R246") (pin "2") (pinfunction "2_2") (pintype "passive"))
    )
    (net (code "148") (name "Net-(LED247-PadA)") (class "Default")
      (node (ref "LED247") (pin "A") (pinfunction "A_A") (pintype "passive"))
      (node (ref "R247") (pin "2") (pinfunction "2_2") (pintype "passive"))
    )
    (net (code "149") (name "Net-(LED248-PadA)") (class "Default")
      (node (ref "LED248") (pin "A") (pinfunction "A_A") (pintype "passive"))
      (node (ref "R248") (pin "2") (pinfunction "2_2") (pintype "passive"))
    )
    (net (code "150") (name "Net-(LED253-PadA)") (class "Default")
      (node (ref "LED253") (pin "A") (pinfunction "A_A") (pintype "passive"))
      (node (ref "R253") (pin "2") (pinfunction "2_2") (pintype "passive"))
    )
    (net (code "151") (name "Net-(LED254-PadA)") (class "Default")
      (node (ref "LED254") (pin "A") (pinfunction "A_A") (pintype "passive"))
      (node (ref "R254") (pin "2") (pinfunction "2_2") (pintype "passive"))
    )
    (net (code "152") (name "Net-(LED255-PadA)") (class "Default")
      (node (ref "LED255") (pin "A") (pinfunction "A_A") (pintype "passive"))
      (node (ref "R255") (pin "2") (pinfunction "2_2") (pintype "passive"))
    )
    (net (code "153") (name "Net-(LED256-PadA)") (class "Default")
      (node (ref "LED256") (pin "A") (pinfunction "A_A") (pintype "passive"))
      (node (ref "R256") (pin "2") (pinfunction "2_2") (pintype "passive"))
    )
    (net (code "154") (name "Net-(LED261-PadA)") (class "Default")
      (node (ref "LED261") (pin "A") (pinfunction "A_A") (pintype "passive"))
      (node (ref "R261") (pin "2") (pinfunction "2_2") (pintype "passive"))
    )
    (net (code "155") (name "Net-(LED262-PadA)") (class "Default")
      (node (ref "LED262") (pin "A") (pinfunction "A_A") (pintype "passive"))
      (node (ref "R262") (pin "2") (pinfunction "2_2") (pintype "passive"))
    )
    (net (code "156") (name "Net-(LED263-PadA)") (class "Default")
      (node (ref "LED263") (pin "A") (pinfunction "A_A") (pintype "passive"))
      (node (ref "R263") (pin "2") (pinfunction "2_2") (pintype "passive"))
    )
    (net (code "157") (name "Net-(LED264-PadA)") (class "Default")
      (node (ref "LED264") (pin "A") (pinfunction "A_A") (pintype "passive"))
      (node (ref "R264") (pin "2") (pinfunction "2_2") (pintype "passive"))
    )
    (net (code "158") (name "Net-(LED269-PadA)") (class "Default")
      (node (ref "LED269") (pin "A") (pinfunction "A_A") (pintype "passive"))
      (node (ref "R269") (pin "2") (pinfunction "2_2") (pintype "passive"))
    )
    (net (code "159") (name "Net-(LED270-PadA)") (class "Default")
      (node (ref "LED270") (pin "A") (pinfunction "A_A") (pintype "passive"))
      (node (ref "R270") (pin "2") (pinfunction "2_2") (pintype "passive"))
    )
    (net (code "160") (name "Net-(LED271-PadA)") (class "Default")
      (node (ref "LED271") (pin "A") (pinfunction "A_A") (pintype "passive"))
      (node (ref "R271") (pin "2") (pinfunction "2_2") (pintype "passive"))
    )
    (net (code "161") (name "Net-(LED272-PadA)") (class "Default")
      (node (ref "LED272") (pin "A") (pinfunction "A_A") (pintype "passive"))
      (node (ref "R272") (pin "2") (pinfunction "2_2") (pintype "passive"))
    )
    (net (code "162") (name "Net-(LED277-PadA)") (class "Default")
      (node (ref "LED277") (pin "A") (pinfunction "A_A") (pintype "passive"))
      (node (ref "R277") (pin "2") (pinfunction "2_2") (pintype "passive"))
    )
    (net (code "163") (name "Net-(LED278-PadA)") (class "Default")
      (node (ref "LED278") (pin "A") (pinfunction "A_A") (pintype "passive"))
      (node (ref "R278") (pin "2") (pinfunction "2_2") (pintype "passive"))
    )
    (net (code "164") (name "Net-(LED279-PadA)") (class "Default")
      (node (ref "LED279") (pin "A") (pinfunction "A_A") (pintype "passive"))
      (node (ref "R279") (pin "2") (pinfunction "2_2") (pintype "passive"))
    )
    (net (code "165") (name "Net-(LED280-PadA)") (class "Default")
      (node (ref "LED280") (pin "A") (pinfunction "A_A") (pintype "passive"))
      (node (ref "R280") (pin "2") (pinfunction "2_2") (pintype "passive"))
    )
    (net (code "166") (name "Net-(LED285-PadA)") (class "Default")
      (node (ref "LED285") (pin "A") (pinfunction "A_A") (pintype "passive"))
      (node (ref "R285") (pin "2") (pinfunction "2_2") (pintype "passive"))
    )
    (net (code "167") (name "Net-(LED286-PadA)") (class "Default")
      (node (ref "LED286") (pin "A") (pinfunction "A_A") (pintype "passive"))
      (node (ref "R286") (pin "2") (pinfunction "2_2") (pintype "passive"))
    )
    (net (code "168") (name "Net-(LED287-PadA)") (class "Default")
      (node (ref "LED287") (pin "A") (pinfunction "A_A") (pintype "passive"))
      (node (ref "R287") (pin "2") (pinfunction "2_2") (pintype "passive"))
    )
    (net (code "169") (name "Net-(LED288-PadA)") (class "Default")
      (node (ref "LED288") (pin "A") (pinfunction "A_A") (pintype "passive"))
      (node (ref "R288") (pin "2") (pinfunction "2_2") (pintype "passive"))
    )
    (net (code "170") (name "Net-(LED293-PadA)") (class "Default")
      (node (ref "LED293") (pin "A") (pinfunction "A_A") (pintype "passive"))
      (node (ref "R293") (pin "2") (pinfunction "2_2") (pintype "passive"))
    )
    (net (code "171") (name "Net-(LED294-PadA)") (class "Default")
      (node (ref "LED294") (pin "A") (pinfunction "A_A") (pintype "passive"))
      (node (ref "R294") (pin "2") (pinfunction "2_2") (pintype "passive"))
    )
    (net (code "172") (name "Net-(LED295-PadA)") (class "Default")
      (node (ref "LED295") (pin "A") (pinfunction "A_A") (pintype "passive"))
      (node (ref "R295") (pin "2") (pinfunction "2_2") (pintype "passive"))
    )
    (net (code "173") (name "Net-(LED296-PadA)") (class "Default")
      (node (ref "LED296") (pin "A") (pinfunction "A_A") (pintype "passive"))
      (node (ref "R296") (pin "2") (pinfunction "2_2") (pintype "passive"))
    )
    (net (code "174") (name "Net-(LED301-PadA)") (class "Default")
      (node (ref "LED301") (pin "A") (pinfunction "A_A") (pintype "passive"))
      (node (ref "R301") (pin "2") (pinfunction "2_2") (pintype "passive"))
    )
    (net (code "175") (name "Net-(LED302-PadA)") (class "Default")
      (node (ref "LED302") (pin "A") (pinfunction "A_A") (pintype "passive"))
      (node (ref "R302") (pin "2") (pinfunction "2_2") (pintype "passive"))
    )
    (net (code "176") (name "Net-(LED303-PadA)") (class "Default")
      (node (ref "LED303") (pin "A") (pinfunction "A_A") (pintype "passive"))
      (node (ref "R303") (pin "2") (pinfunction "2_2") (pintype "passive"))
    )
    (net (code "177") (name "Net-(LED304-PadA)") (class "Default")
      (node (ref "LED304") (pin "A") (pinfunction "A_A") (pintype "passive"))
      (node (ref "R304") (pin "2") (pinfunction "2_2") (pintype "passive"))
    )
    (net (code "178") (name "Net-(LED309-PadA)") (class "Default")
      (node (ref "LED309") (pin "A") (pinfunction "A_A") (pintype "passive"))
      (node (ref "R309") (pin "2") (pinfunction "2_2") (pintype "passive"))
    )
    (net (code "179") (name "Net-(LED310-PadA)") (class "Default")
      (node (ref "LED310") (pin "A") (pinfunction "A_A") (pintype "passive"))
      (node (ref "R310") (pin "2") (pinfunction "2_2") (pintype "passive"))
    )
    (net (code "180") (name "Net-(LED311-PadA)") (class "Default")
      (node (ref "LED311") (pin "A") (pinfunction "A_A") (pintype "passive"))
      (node (ref "R311") (pin "2") (pinfunction "2_2") (pintype "passive"))
    )
    (net (code "181") (name "Net-(LED312-PadA)") (class "Default")
      (node (ref "LED312") (pin "A") (pinfunction "A_A") (pintype "passive"))
      (node (ref "R312") (pin "2") (pinfunction "2_2") (pintype "passive"))
    )
    (net (code "182") (name "Net-(LED317-PadA)") (class "Default")
      (node (ref "LED317") (pin "A") (pinfunction "A_A") (pintype "passive"))
      (node (ref "R317") (pin "2") (pinfunction "2_2") (pintype "passive"))
    )
    (net (code "183") (name "Net-(LED318-PadA)") (class "Default")
      (node (ref "LED318") (pin "A") (pinfunction "A_A") (pintype "passive"))
      (node (ref "R318") (pin "2") (pinfunction "2_2") (pintype "passive"))
    )
    (net (code "184") (name "Net-(LED319-PadA)") (class "Default")
      (node (ref "LED319") (pin "A") (pinfunction "A_A") (pintype "passive"))
      (node (ref "R319") (pin "2") (pinfunction "2_2") (pintype "passive"))
    )
    (net (code "185") (name "Net-(LED320-PadA)") (class "Default")
      (node (ref "LED320") (pin "A") (pinfunction "A_A") (pintype "passive"))
      (node (ref "R320") (pin "2") (pinfunction "2_2") (pintype "passive"))
    )
    (net (code "186") (name "Net-(LED325-PadA)") (class "Default")
      (node (ref "LED325") (pin "A") (pinfunction "A_A") (pintype "passive"))
      (node (ref "R325") (pin "2") (pinfunction "2_2") (pintype "passive"))
    )
    (net (code "187") (name "Net-(LED326-PadA)") (class "Default")
      (node (ref "LED326") (pin "A") (pinfunction "A_A") (pintype "passive"))
      (node (ref "R326") (pin "2") (pinfunction "2_2") (pintype "passive"))
    )
    (net (code "188") (name "Net-(LED327-PadA)") (class "Default")
      (node (ref "LED327") (pin "A") (pinfunction "A_A") (pintype "passive"))
      (node (ref "R327") (pin "2") (pinfunction "2_2") (pintype "passive"))
    )
    (net (code "189") (name "Net-(LED328-PadA)") (class "Default")
      (node (ref "LED328") (pin "A") (pinfunction "A_A") (pintype "passive"))
      (node (ref "R328") (pin "2") (pinfunction "2_2") (pintype "passive"))
    )
    (net (code "190") (name "Net-(LED333-PadA)") (class "Default")
      (node (ref "LED333") (pin "A") (pinfunction "A_A") (pintype "passive"))
      (node (ref "R333") (pin "2") (pinfunction "2_2") (pintype "passive"))
    )
    (net (code "191") (name "Net-(LED334-PadA)") (class "Default")
      (node (ref "LED334") (pin "A") (pinfunction "A_A") (pintype "passive"))
      (node (ref "R334") (pin "2") (pinfunction "2_2") (pintype "passive"))
    )
    (net (code "192") (name "Net-(LED335-PadA)") (class "Default")
      (node (ref "LED335") (pin "A") (pinfunction "A_A") (pintype "passive"))
      (node (ref "R335") (pin "2") (pinfunction "2_2") (pintype "passive"))
    )
    (net (code "193") (name "Net-(LED336-PadA)") (class "Default")
      (node (ref "LED336") (pin "A") (pinfunction "A_A") (pintype "passive"))
      (node (ref "R336") (pin "2") (pinfunction "2_2") (pintype "passive"))
    )
    (net (code "194") (name "Net-(LED341-PadA)") (class "Default")
      (node (ref "LED341") (pin "A") (pinfunction "A_A") (pintype "passive"))
      (node (ref "R341") (pin "2") (pinfunction "2_2") (pintype "passive"))
    )
    (net (code "195") (name "Net-(LED342-PadA)") (class "Default")
      (node (ref "LED342") (pin "A") (pinfunction "A_A") (pintype "passive"))
      (node (ref "R342") (pin "2") (pinfunction "2_2") (pintype "passive"))
    )
    (net (code "196") (name "Net-(LED343-PadA)") (class "Default")
      (node (ref "LED343") (pin "A") (pinfunction "A_A") (pintype "passive"))
      (node (ref "R343") (pin "2") (pinfunction "2_2") (pintype "passive"))
    )
    (net (code "197") (name "Net-(LED344-PadA)") (class "Default")
      (node (ref "LED344") (pin "A") (pinfunction "A_A") (pintype "passive"))
      (node (ref "R344") (pin "2") (pinfunction "2_2") (pintype "passive"))
    )
    (net (code "198") (name "Net-(LED349-PadA)") (class "Default")
      (node (ref "LED349") (pin "A") (pinfunction "A_A") (pintype "passive"))
      (node (ref "R349") (pin "2") (pinfunction "2_2") (pintype "passive"))
    )
    (net (code "199") (name "Net-(LED350-PadA)") (class "Default")
      (node (ref "LED350") (pin "A") (pinfunction "A_A") (pintype "passive"))
      (node (ref "R350") (pin "2") (pinfunction "2_2") (pintype "passive"))
    )
    (net (code "200") (name "Net-(LED351-PadA)") (class "Default")
      (node (ref "LED351") (pin "A") (pinfunction "A_A") (pintype "passive"))
      (node (ref "R351") (pin "2") (pinfunction "2_2") (pintype "passive"))
    )
    (net (code "201") (name "Net-(LED352-PadA)") (class "Default")
      (node (ref "LED352") (pin "A") (pinfunction "A_A") (pintype "passive"))
      (node (ref "R352") (pin "2") (pinfunction "2_2") (pintype "passive"))
    )
    (net (code "202") (name "Net-(LED357-PadA)") (class "Default")
      (node (ref "LED357") (pin "A") (pinfunction "A_A") (pintype "passive"))
      (node (ref "R357") (pin "2") (pinfunction "2_2") (pintype "passive"))
    )
    (net (code "203") (name "Net-(LED358-PadA)") (class "Default")
      (node (ref "LED358") (pin "A") (pinfunction "A_A") (pintype "passive"))
      (node (ref "R358") (pin "2") (pinfunction "2_2") (pintype "passive"))
    )
    (net (code "204") (name "Net-(LED359-PadA)") (class "Default")
      (node (ref "LED359") (pin "A") (pinfunction "A_A") (pintype "passive"))
      (node (ref "R359") (pin "2") (pinfunction "2_2") (pintype "passive"))
    )
    (net (code "205") (name "Net-(LED360-PadA)") (class "Default")
      (node (ref "LED360") (pin "A") (pinfunction "A_A") (pintype "passive"))
      (node (ref "R360") (pin "2") (pinfunction "2_2") (pintype "passive"))
    )
    (net (code "206") (name "Net-(LED365-PadA)") (class "Default")
      (node (ref "LED365") (pin "A") (pinfunction "A_A") (pintype "passive"))
      (node (ref "R365") (pin "2") (pinfunction "2_2") (pintype "passive"))
    )
    (net (code "207") (name "Net-(LED366-PadA)") (class "Default")
      (node (ref "LED366") (pin "A") (pinfunction "A_A") (pintype "passive"))
      (node (ref "R366") (pin "2") (pinfunction "2_2") (pintype "passive"))
    )
    (net (code "208") (name "Net-(LED367-PadA)") (class "Default")
      (node (ref "LED367") (pin "A") (pinfunction "A_A") (pintype "passive"))
      (node (ref "R367") (pin "2") (pinfunction "2_2") (pintype "passive"))
    )
    (net (code "209") (name "Net-(LED368-PadA)") (class "Default")
      (node (ref "LED368") (pin "A") (pinfunction "A_A") (pintype "passive"))
      (node (ref "R368") (pin "2") (pinfunction "2_2") (pintype "passive"))
    )
    (net (code "210") (name "Net-(LED373-PadA)") (class "Default")
      (node (ref "LED373") (pin "A") (pinfunction "A_A") (pintype "passive"))
      (node (ref "R373") (pin "2") (pinfunction "2_2") (pintype "passive"))
    )
    (net (code "211") (name "Net-(LED374-PadA)") (class "Default")
      (node (ref "LED374") (pin "A") (pinfunction "A_A") (pintype "passive"))
      (node (ref "R374") (pin "2") (pinfunction "2_2") (pintype "passive"))
    )
    (net (code "212") (name "Net-(LED375-PadA)") (class "Default")
      (node (ref "LED375") (pin "A") (pinfunction "A_A") (pintype "passive"))
      (node (ref "R375") (pin "2") (pinfunction "2_2") (pintype "passive"))
    )
    (net (code "213") (name "Net-(LED376-PadA)") (class "Default")
      (node (ref "LED376") (pin "A") (pinfunction "A_A") (pintype "passive"))
      (node (ref "R376") (pin "2") (pinfunction "2_2") (pintype "passive"))
    )
    (net (code "214") (name "Net-(LED381-PadA)") (class "Default")
      (node (ref "LED381") (pin "A") (pinfunction "A_A") (pintype "passive"))
      (node (ref "R381") (pin "2") (pinfunction "2_2") (pintype "passive"))
    )
    (net (code "215") (name "Net-(LED382-PadA)") (class "Default")
      (node (ref "LED382") (pin "A") (pinfunction "A_A") (pintype "passive"))
      (node (ref "R382") (pin "2") (pinfunction "2_2") (pintype "passive"))
    )
    (net (code "216") (name "Net-(LED383-PadA)") (class "Default")
      (node (ref "LED383") (pin "A") (pinfunction "A_A") (pintype "passive"))
      (node (ref "R383") (pin "2") (pinfunction "2_2") (pintype "passive"))
    )
    (net (code "217") (name "Net-(LED384-PadA)") (class "Default")
      (node (ref "LED384") (pin "A") (pinfunction "A_A") (pintype "passive"))
      (node (ref "R384") (pin "2") (pinfunction "2_2") (pintype "passive"))
    )
    (net (code "218") (name "Net-(LED389-PadA)") (class "Default")
      (node (ref "LED389") (pin "A") (pinfunction "A_A") (pintype "passive"))
      (node (ref "R389") (pin "2") (pinfunction "2_2") (pintype "passive"))
    )
    (net (code "219") (name "Net-(LED390-PadA)") (class "Default")
      (node (ref "LED390") (pin "A") (pinfunction "A_A") (pintype "passive"))
      (node (ref "R390") (pin "2") (pinfunction "2_2") (pintype "passive"))
    )
    (net (code "220") (name "Net-(LED391-PadA)") (class "Default")
      (node (ref "LED391") (pin "A") (pinfunction "A_A") (pintype "passive"))
      (node (ref "R391") (pin "2") (pinfunction "2_2") (pintype "passive"))
    )
    (net (code "221") (name "Net-(LED392-PadA)") (class "Default")
      (node (ref "LED392") (pin "A") (pinfunction "A_A") (pintype "passive"))
      (node (ref "R392") (pin "2") (pinfunction "2_2") (pintype "passive"))
    )
    (net (code "222") (name "Net-(LED397-PadA)") (class "Default")
      (node (ref "LED397") (pin "A") (pinfunction "A_A") (pintype "passive"))
      (node (ref "R397") (pin "2") (pinfunction "2_2") (pintype "passive"))
    )
    (net (code "223") (name "Net-(LED398-PadA)") (class "Default")
      (node (ref "LED398") (pin "A") (pinfunction "A_A") (pintype "passive"))
      (node (ref "R398") (pin "2") (pinfunction "2_2") (pintype "passive"))
    )
    (net (code "224") (name "Net-(LED399-PadA)") (class "Default")
      (node (ref "LED399") (pin "A") (pinfunction "A_A") (pintype "passive"))
      (node (ref "R399") (pin "2") (pinfunction "2_2") (pintype "passive"))
    )
    (net (code "225") (name "Net-(LED400-PadA)") (class "Default")
      (node (ref "LED400") (pin "A") (pinfunction "A_A") (pintype "passive"))
      (node (ref "R400") (pin "2") (pinfunction "2_2") (pintype "passive"))
    )
    (net (code "226") (name "Net-(LED405-PadA)") (class "Default")
      (node (ref "LED405") (pin "A") (pinfunction "A_A") (pintype "passive"))
      (node (ref "R405") (pin "2") (pinfunction "2_2") (pintype "passive"))
    )
    (net (code "227") (name "Net-(LED406-PadA)") (class "Default")
      (node (ref "LED406") (pin "A") (pinfunction "A_A") (pintype "passive"))
      (node (ref "R406") (pin "2") (pinfunction "2_2") (pintype "passive"))
    )
    (net (code "228") (name "Net-(LED407-PadA)") (class "Default")
      (node (ref "LED407") (pin "A") (pinfunction "A_A") (pintype "passive"))
      (node (ref "R407") (pin "2") (pinfunction "2_2") (pintype "passive"))
    )
    (net (code "229") (name "Net-(LED408-PadA)") (class "Default")
      (node (ref "LED408") (pin "A") (pinfunction "A_A") (pintype "passive"))
      (node (ref "R408") (pin "2") (pinfunction "2_2") (pintype "passive"))
    )
    (net (code "230") (name "Net-(LED413-PadA)") (class "Default")
      (node (ref "LED413") (pin "A") (pinfunction "A_A") (pintype "passive"))
      (node (ref "R413") (pin "2") (pinfunction "2_2") (pintype "passive"))
    )
    (net (code "231") (name "Net-(LED414-PadA)") (class "Default")
      (node (ref "LED414") (pin "A") (pinfunction "A_A") (pintype "passive"))
      (node (ref "R414") (pin "2") (pinfunction "2_2") (pintype "passive"))
    )
    (net (code "232") (name "Net-(LED415-PadA)") (class "Default")
      (node (ref "LED415") (pin "A") (pinfunction "A_A") (pintype "passive"))
      (node (ref "R415") (pin "2") (pinfunction "2_2") (pintype "passive"))
    )
    (net (code "233") (name "Net-(LED416-PadA)") (class "Default")
      (node (ref "LED416") (pin "A") (pinfunction "A_A") (pintype "passive"))
      (node (ref "R416") (pin "2") (pinfunction "2_2") (pintype "passive"))
    )
    (net (code "234") (name "P1") (class "Default")
      (node (ref "R10") (pin "1") (pinfunction "1_1") (pintype "passive"))
      (node (ref "R101") (pin "1") (pinfunction "1_1") (pintype "passive"))
      (node (ref "R102") (pin "1") (pinfunction "1_1") (pintype "passive"))
      (node (ref "R103") (pin "1") (pinfunction "1_1") (pintype "passive"))
      (node (ref "R104") (pin "1") (pinfunction "1_1") (pintype "passive"))
      (node (ref "R109") (pin "1") (pinfunction "1_1") (pintype "passive"))
      (node (ref "R11") (pin "1") (pinfunction "1_1") (pintype "passive"))
      (node (ref "R110") (pin "1") (pinfunction "1_1") (pintype "passive"))
      (node (ref "R111") (pin "1") (pinfunction "1_1") (pintype "passive"))
      (node (ref "R112") (pin "1") (pinfunction "1_1") (pintype "passive"))
      (node (ref "R117") (pin "1") (pinfunction "1_1") (pintype "passive"))
      (node (ref "R118") (pin "1") (pinfunction "1_1") (pintype "passive"))
      (node (ref "R119") (pin "1") (pinfunction "1_1") (pintype "passive"))
      (node (ref "R12") (pin "1") (pinfunction "1_1") (pintype "passive"))
      (node (ref "R120") (pin "1") (pinfunction "1_1") (pintype "passive"))
      (node (ref "R125") (pin "1") (pinfunction "1_1") (pintype "passive"))
      (node (ref "R126") (pin "1") (pinfunction "1_1") (pintype "passive"))
      (node (ref "R127") (pin "1") (pinfunction "1_1") (pintype "passive"))
      (node (ref "R128") (pin "1") (pinfunction "1_1") (pintype "passive"))
      (node (ref "R13") (pin "1") (pinfunction "1_1") (pintype "passive"))
      (node (ref "R133") (pin "1") (pinfunction "1_1") (pintype "passive"))
      (node (ref "R134") (pin "1") (pinfunction "1_1") (pintype "passive"))
      (node (ref "R135") (pin "1") (pinfunction "1_1") (pintype "passive"))
      (node (ref "R136") (pin "1") (pinfunction "1_1") (pintype "passive"))
      (node (ref "R14") (pin "1") (pinfunction "1_1") (pintype "passive"))
      (node (ref "R141") (pin "1") (pinfunction "1_1") (pintype "passive"))
      (node (ref "R142") (pin "1") (pinfunction "1_1") (pintype "passive"))
      (node (ref "R143") (pin "1") (pinfunction "1_1") (pintype "passive"))
      (node (ref "R144") (pin "1") (pinfunction "1_1") (pintype "passive"))
      (node (ref "R149") (pin "1") (pinfunction "1_1") (pintype "passive"))
      (node (ref "R15") (pin "1") (pinfunction "1_1") (pintype "passive"))
      (node (ref "R150") (pin "1") (pinfunction "1_1") (pintype "passive"))
      (node (ref "R151") (pin "1") (pinfunction "1_1") (pintype "passive"))
      (node (ref "R152") (pin "1") (pinfunction "1_1") (pintype "passive"))
      (node (ref "R157") (pin "1") (pinfunction "1_1") (pintype "passive"))
      (node (ref "R158") (pin "1") (pinfunction "1_1") (pintype "passive"))
      (node (ref "R159") (pin "1") (pinfunction "1_1") (pintype "passive"))
      (node (ref "R16") (pin "1") (pinfunction "1_1") (pintype "passive"))
      (node (ref "R160") (pin "1") (pinfunction "1_1") (pintype "passive"))
      (node (ref "R165") (pin "1") (pinfunction "1_1") (pintype "passive"))
      (node (ref "R166") (pin "1") (pinfunction "1_1") (pintype "passive"))
      (node (ref "R167") (pin "1") (pinfunction "1_1") (pintype "passive"))
      (node (ref "R168") (pin "1") (pinfunction "1_1") (pintype "passive"))
      (node (ref "R17") (pin "1") (pinfunction "1_1") (pintype "passive"))
      (node (ref "R173") (pin "1") (pinfunction "1_1") (pintype "passive"))
      (node (ref "R174") (pin "1") (pinfunction "1_1") (pintype "passive"))
      (node (ref "R175") (pin "1") (pinfunction "1_1") (pintype "passive"))
      (node (ref "R176") (pin "1") (pinfunction "1_1") (pintype "passive"))
      (node (ref "R18") (pin "1") (pinfunction "1_1") (pintype "passive"))
      (node (ref "R181") (pin "1") (pinfunction "1_1") (pintype "passive"))
      (node (ref "R182") (pin "1") (pinfunction "1_1") (pintype "passive"))
      (node (ref "R183") (pin "1") (pinfunction "1_1") (pintype "passive"))
      (node (ref "R184") (pin "1") (pinfunction "1_1") (pintype "passive"))
      (node (ref "R189") (pin "1") (pinfunction "1_1") (pintype "passive"))
      (node (ref "R19") (pin "1") (pinfunction "1_1") (pintype "passive"))
      (node (ref "R190") (pin "1") (pinfunction "1_1") (pintype "passive"))
      (node (ref "R191") (pin "1") (pinfunction "1_1") (pintype "passive"))
      (node (ref "R192") (pin "1") (pinfunction "1_1") (pintype "passive"))
      (node (ref "R197") (pin "1") (pinfunction "1_1") (pintype "passive"))
      (node (ref "R198") (pin "1") (pinfunction "1_1") (pintype "passive"))
      (node (ref "R199") (pin "1") (pinfunction "1_1") (pintype "passive"))
      (node (ref "R20") (pin "1") (pinfunction "1_1") (pintype "passive"))
      (node (ref "R200") (pin "1") (pinfunction "1_1") (pintype "passive"))
      (node (ref "R205") (pin "1") (pinfunction "1_1") (pintype "passive"))
      (node (ref "R206") (pin "1") (pinfunction "1_1") (pintype "passive"))
      (node (ref "R207") (pin "1") (pinfunction "1_1") (pintype "passive"))
      (node (ref "R208") (pin "1") (pinfunction "1_1") (pintype "passive"))
      (node (ref "R21") (pin "1") (pinfunction "1_1") (pintype "passive"))
      (node (ref "R213") (pin "1") (pinfunction "1_1") (pintype "passive"))
      (node (ref "R214") (pin "1") (pinfunction "1_1") (pintype "passive"))
      (node (ref "R215") (pin "1") (pinfunction "1_1") (pintype "passive"))
      (node (ref "R216") (pin "1") (pinfunction "1_1") (pintype "passive"))
      (node (ref "R22") (pin "1") (pinfunction "1_1") (pintype "passive"))
      (node (ref "R221") (pin "1") (pinfunction "1_1") (pintype "passive"))
      (node (ref "R222") (pin "1") (pinfunction "1_1") (pintype "passive"))
      (node (ref "R223") (pin "1") (pinfunction "1_1") (pintype "passive"))
      (node (ref "R224") (pin "1") (pinfunction "1_1") (pintype "passive"))
      (node (ref "R229") (pin "1") (pinfunction "1_1") (pintype "passive"))
      (node (ref "R23") (pin "1") (pinfunction "1_1") (pintype "passive"))
      (node (ref "R230") (pin "1") (pinfunction "1_1") (pintype "passive"))
      (node (ref "R231") (pin "1") (pinfunction "1_1") (pintype "passive"))
      (node (ref "R232") (pin "1") (pinfunction "1_1") (pintype "passive"))
      (node (ref "R237") (pin "1") (pinfunction "1_1") (pintype "passive"))
      (node (ref "R238") (pin "1") (pinfunction "1_1") (pintype "passive"))
      (node (ref "R239") (pin "1") (pinfunction "1_1") (pintype "passive"))
      (node (ref "R24") (pin "1") (pinfunction "1_1") (pintype "passive"))
      (node (ref "R240") (pin "1") (pinfunction "1_1") (pintype "passive"))
      (node (ref "R245") (pin "1") (pinfunction "1_1") (pintype "passive"))
      (node (ref "R246") (pin "1") (pinfunction "1_1") (pintype "passive"))
      (node (ref "R247") (pin "1") (pinfunction "1_1") (pintype "passive"))
      (node (ref "R248") (pin "1") (pinfunction "1_1") (pintype "passive"))
      (node (ref "R25") (pin "1") (pinfunction "1_1") (pintype "passive"))
      (node (ref "R253") (pin "1") (pinfunction "1_1") (pintype "passive"))
      (node (ref "R254") (pin "1") (pinfunction "1_1") (pintype "passive"))
      (node (ref "R255") (pin "1") (pinfunction "1_1") (pintype "passive"))
      (node (ref "R256") (pin "1") (pinfunction "1_1") (pintype "passive"))
      (node (ref "R26") (pin "1") (pinfunction "1_1") (pintype "passive"))
      (node (ref "R261") (pin "1") (pinfunction "1_1") (pintype "passive"))
      (node (ref "R262") (pin "1") (pinfunction "1_1") (pintype "passive"))
      (node (ref "R263") (pin "1") (pinfunction "1_1") (pintype "passive"))
      (node (ref "R264") (pin "1") (pinfunction "1_1") (pintype "passive"))
      (node (ref "R269") (pin "1") (pinfunction "1_1") (pintype "passive"))
      (node (ref "R27") (pin "1") (pinfunction "1_1") (pintype "passive"))
      (node (ref "R270") (pin "1") (pinfunction "1_1") (pintype "passive"))
      (node (ref "R271") (pin "1") (pinfunction "1_1") (pintype "passive"))
      (node (ref "R272") (pin "1") (pinfunction "1_1") (pintype "passive"))
      (node (ref "R277") (pin "1") (pinfunction "1_1") (pintype "passive"))
      (node (ref "R278") (pin "1") (pinfunction "1_1") (pintype "passive"))
      (node (ref "R279") (pin "1") (pinfunction "1_1") (pintype "passive"))
      (node (ref "R28") (pin "1") (pinfunction "1_1") (pintype "passive"))
      (node (ref "R280") (pin "1") (pinfunction "1_1") (pintype "passive"))
      (node (ref "R285") (pin "1") (pinfunction "1_1") (pintype "passive"))
      (node (ref "R286") (pin "1") (pinfunction "1_1") (pintype "passive"))
      (node (ref "R287") (pin "1") (pinfunction "1_1") (pintype "passive"))
      (node (ref "R288") (pin "1") (pinfunction "1_1") (pintype "passive"))
      (node (ref "R29") (pin "1") (pinfunction "1_1") (pintype "passive"))
      (node (ref "R293") (pin "1") (pinfunction "1_1") (pintype "passive"))
      (node (ref "R294") (pin "1") (pinfunction "1_1") (pintype "passive"))
      (node (ref "R295") (pin "1") (pinfunction "1_1") (pintype "passive"))
      (node (ref "R296") (pin "1") (pinfunction "1_1") (pintype "passive"))
      (node (ref "R30") (pin "1") (pinfunction "1_1") (pintype "passive"))
      (node (ref "R301") (pin "1") (pinfunction "1_1") (pintype "passive"))
      (node (ref "R302") (pin "1") (pinfunction "1_1") (pintype "passive"))
      (node (ref "R303") (pin "1") (pinfunction "1_1") (pintype "passive"))
      (node (ref "R304") (pin "1") (pinfunction "1_1") (pintype "passive"))
      (node (ref "R309") (pin "1") (pinfunction "1_1") (pintype "passive"))
      (node (ref "R31") (pin "1") (pinfunction "1_1") (pintype "passive"))
      (node (ref "R310") (pin "1") (pinfunction "1_1") (pintype "passive"))
      (node (ref "R311") (pin "1") (pinfunction "1_1") (pintype "passive"))
      (node (ref "R312") (pin "1") (pinfunction "1_1") (pintype "passive"))
      (node (ref "R317") (pin "1") (pinfunction "1_1") (pintype "passive"))
      (node (ref "R318") (pin "1") (pinfunction "1_1") (pintype "passive"))
      (node (ref "R319") (pin "1") (pinfunction "1_1") (pintype "passive"))
      (node (ref "R32") (pin "1") (pinfunction "1_1") (pintype "passive"))
      (node (ref "R320") (pin "1") (pinfunction "1_1") (pintype "passive"))
      (node (ref "R325") (pin "1") (pinfunction "1_1") (pintype "passive"))
      (node (ref "R326") (pin "1") (pinfunction "1_1") (pintype "passive"))
      (node (ref "R327") (pin "1") (pinfunction "1_1") (pintype "passive"))
      (node (ref "R328") (pin "1") (pinfunction "1_1") (pintype "passive"))
      (node (ref "R33") (pin "1") (pinfunction "1_1") (pintype "passive"))
      (node (ref "R333") (pin "1") (pinfunction "1_1") (pintype "passive"))
      (node (ref "R334") (pin "1") (pinfunction "1_1") (pintype "passive"))
      (node (ref "R335") (pin "1") (pinfunction "1_1") (pintype "passive"))
      (node (ref "R336") (pin "1") (pinfunction "1_1") (pintype "passive"))
      (node (ref "R34") (pin "1") (pinfunction "1_1") (pintype "passive"))
      (node (ref "R341") (pin "1") (pinfunction "1_1") (pintype "passive"))
      (node (ref "R342") (pin "1") (pinfunction "1_1") (pintype "passive"))
      (node (ref "R343") (pin "1") (pinfunction "1_1") (pintype "passive"))
      (node (ref "R344") (pin "1") (pinfunction "1_1") (pintype "passive"))
      (node (ref "R349") (pin "1") (pinfunction "1_1") (pintype "passive"))
      (node (ref "R35") (pin "1") (pinfunction "1_1") (pintype "passive"))
      (node (ref "R350") (pin "1") (pinfunction "1_1") (pintype "passive"))
      (node (ref "R351") (pin "1") (pinfunction "1_1") (pintype "passive"))
      (node (ref "R352") (pin "1") (pinfunction "1_1") (pintype "passive"))
      (node (ref "R357") (pin "1") (pinfunction "1_1") (pintype "passive"))
      (node (ref "R358") (pin "1") (pinfunction "1_1") (pintype "passive"))
      (node (ref "R359") (pin "1") (pinfunction "1_1") (pintype "passive"))
      (node (ref "R36") (pin "1") (pinfunction "1_1") (pintype "passive"))
      (node (ref "R360") (pin "1") (pinfunction "1_1") (pintype "passive"))
      (node (ref "R365") (pin "1") (pinfunction "1_1") (pintype "passive"))
      (node (ref "R366") (pin "1") (pinfunction "1_1") (pintype "passive"))
      (node (ref "R367") (pin "1") (pinfunction "1_1") (pintype "passive"))
      (node (ref "R368") (pin "1") (pinfunction "1_1") (pintype "passive"))
      (node (ref "R37") (pin "1") (pinfunction "1_1") (pintype "passive"))
      (node (ref "R373") (pin "1") (pinfunction "1_1") (pintype "passive"))
      (node (ref "R374") (pin "1") (pinfunction "1_1") (pintype "passive"))
      (node (ref "R375") (pin "1") (pinfunction "1_1") (pintype "passive"))
      (node (ref "R376") (pin "1") (pinfunction "1_1") (pintype "passive"))
      (node (ref "R38") (pin "1") (pinfunction "1_1") (pintype "passive"))
      (node (ref "R381") (pin "1") (pinfunction "1_1") (pintype "passive"))
      (node (ref "R382") (pin "1") (pinfunction "1_1") (pintype "passive"))
      (node (ref "R383") (pin "1") (pinfunction "1_1") (pintype "passive"))
      (node (ref "R384") (pin "1") (pinfunction "1_1") (pintype "passive"))
      (node (ref "R389") (pin "1") (pinfunction "1_1") (pintype "passive"))
      (node (ref "R39") (pin "1") (pinfunction "1_1") (pintype "passive"))
      (node (ref "R390") (pin "1") (pinfunction "1_1") (pintype "passive"))
      (node (ref "R391") (pin "1") (pinfunction "1_1") (pintype "passive"))
      (node (ref "R392") (pin "1") (pinfunction "1_1") (pintype "passive"))
      (node (ref "R397") (pin "1") (pinfunction "1_1") (pintype "passive"))
      (node (ref "R398") (pin "1") (pinfunction "1_1") (pintype "passive"))
      (node (ref "R399") (pin "1") (pinfunction "1_1") (pintype "passive"))
      (node (ref "R40") (pin "1") (pinfunction "1_1") (pintype "passive"))
      (node (ref "R400") (pin "1") (pinfunction "1_1") (pintype "passive"))
      (node (ref "R405") (pin "1") (pinfunction "1_1") (pintype "passive"))
      (node (ref "R406") (pin "1") (pinfunction "1_1") (pintype "passive"))
      (node (ref "R407") (pin "1") (pinfunction "1_1") (pintype "passive"))
      (node (ref "R408") (pin "1") (pinfunction "1_1") (pintype "passive"))
      (node (ref "R413") (pin "1") (pinfunction "1_1") (pintype "passive"))
      (node (ref "R414") (pin "1") (pinfunction "1_1") (pintype "passive"))
      (node (ref "R415") (pin "1") (pinfunction "1_1") (pintype "passive"))
      (node (ref "R416") (pin "1") (pinfunction "1_1") (pintype "passive"))
      (node (ref "R45") (pin "1") (pinfunction "1_1") (pintype "passive"))
      (node (ref "R46") (pin "1") (pinfunction "1_1") (pintype "passive"))
      (node (ref "R47") (pin "1") (pinfunction "1_1") (pintype "passive"))
      (node (ref "R48") (pin "1") (pinfunction "1_1") (pintype "passive"))
      (node (ref "R49") (pin "1") (pinfunction "1_1") (pintype "passive"))
      (node (ref "R5") (pin "1") (pinfunction "1_1") (pintype "passive"))
      (node (ref "R50") (pin "1") (pinfunction "1_1") (pintype "passive"))
      (node (ref "R51") (pin "1") (pinfunction "1_1") (pintype "passive"))
      (node (ref "R52") (pin "1") (pinfunction "1_1") (pintype "passive"))
      (node (ref "R53") (pin "1") (pinfunction "1_1") (pintype "passive"))
      (node (ref "R54") (pin "1") (pinfunction "1_1") (pintype "passive"))
      (node (ref "R55") (pin "1") (pinfunction "1_1") (pintype "passive"))
      (node (ref "R56") (pin "1") (pinfunction "1_1") (pintype "passive"))
      (node (ref "R6") (pin "1") (pinfunction "1_1") (pintype "passive"))
      (node (ref "R61") (pin "1") (pinfunction "1_1") (pintype "passive"))
      (node (ref "R62") (pin "1") (pinfunction "1_1") (pintype "passive"))
      (node (ref "R63") (pin "1") (pinfunction "1_1") (pintype "passive"))
      (node (ref "R64") (pin "1") (pinfunction "1_1") (pintype "passive"))
      (node (ref "R65") (pin "1") (pinfunction "1_1") (pintype "passive"))
      (node (ref "R66") (pin "1") (pinfunction "1_1") (pintype "passive"))
      (node (ref "R67") (pin "1") (pinfunction "1_1") (pintype "passive"))
      (node (ref "R68") (pin "1") (pinfunction "1_1") (pintype "passive"))
      (node (ref "R69") (pin "1") (pinfunction "1_1") (pintype "passive"))
      (node (ref "R7") (pin "1") (pinfunction "1_1") (pintype "passive"))
      (node (ref "R70") (pin "1") (pinfunction "1_1") (pintype "passive"))
      (node (ref "R71") (pin "1") (pinfunction "1_1") (pintype "passive"))
      (node (ref "R72") (pin "1") (pinfunction "1_1") (pintype "passive"))
      (node (ref "R77") (pin "1") (pinfunction "1_1") (pintype "passive"))
      (node (ref "R78") (pin "1") (pinfunction "1_1") (pintype "passive"))
      (node (ref "R79") (pin "1") (pinfunction "1_1") (pintype "passive"))
      (node (ref "R8") (pin "1") (pinfunction "1_1") (pintype "passive"))
      (node (ref "R80") (pin "1") (pinfunction "1_1") (pintype "passive"))
      (node (ref "R85") (pin "1") (pinfunction "1_1") (pintype "passive"))
      (node (ref "R86") (pin "1") (pinfunction "1_1") (pintype "passive"))
      (node (ref "R87") (pin "1") (pinfunction "1_1") (pintype "passive"))
      (node (ref "R88") (pin "1") (pinfunction "1_1") (pintype "passive"))
      (node (ref "R9") (pin "1") (pinfunction "1_1") (pintype "passive"))
      (node (ref "R93") (pin "1") (pinfunction "1_1") (pintype "passive"))
      (node (ref "R94") (pin "1") (pinfunction "1_1") (pintype "passive"))
      (node (ref "R95") (pin "1") (pinfunction "1_1") (pintype "passive"))
      (node (ref "R96") (pin "1") (pinfunction "1_1") (pintype "passive"))
      (node (ref "U$1") (pin "P$1") (pinfunction "2_P$1") (pintype "passive"))
      (node (ref "U$2") (pin "P$1") (pinfunction "2_P$1") (pintype "passive"))
    )
  )
)
